# MDE-DR-4.net
KiCad netlist of a schematic drawn in EAGLE
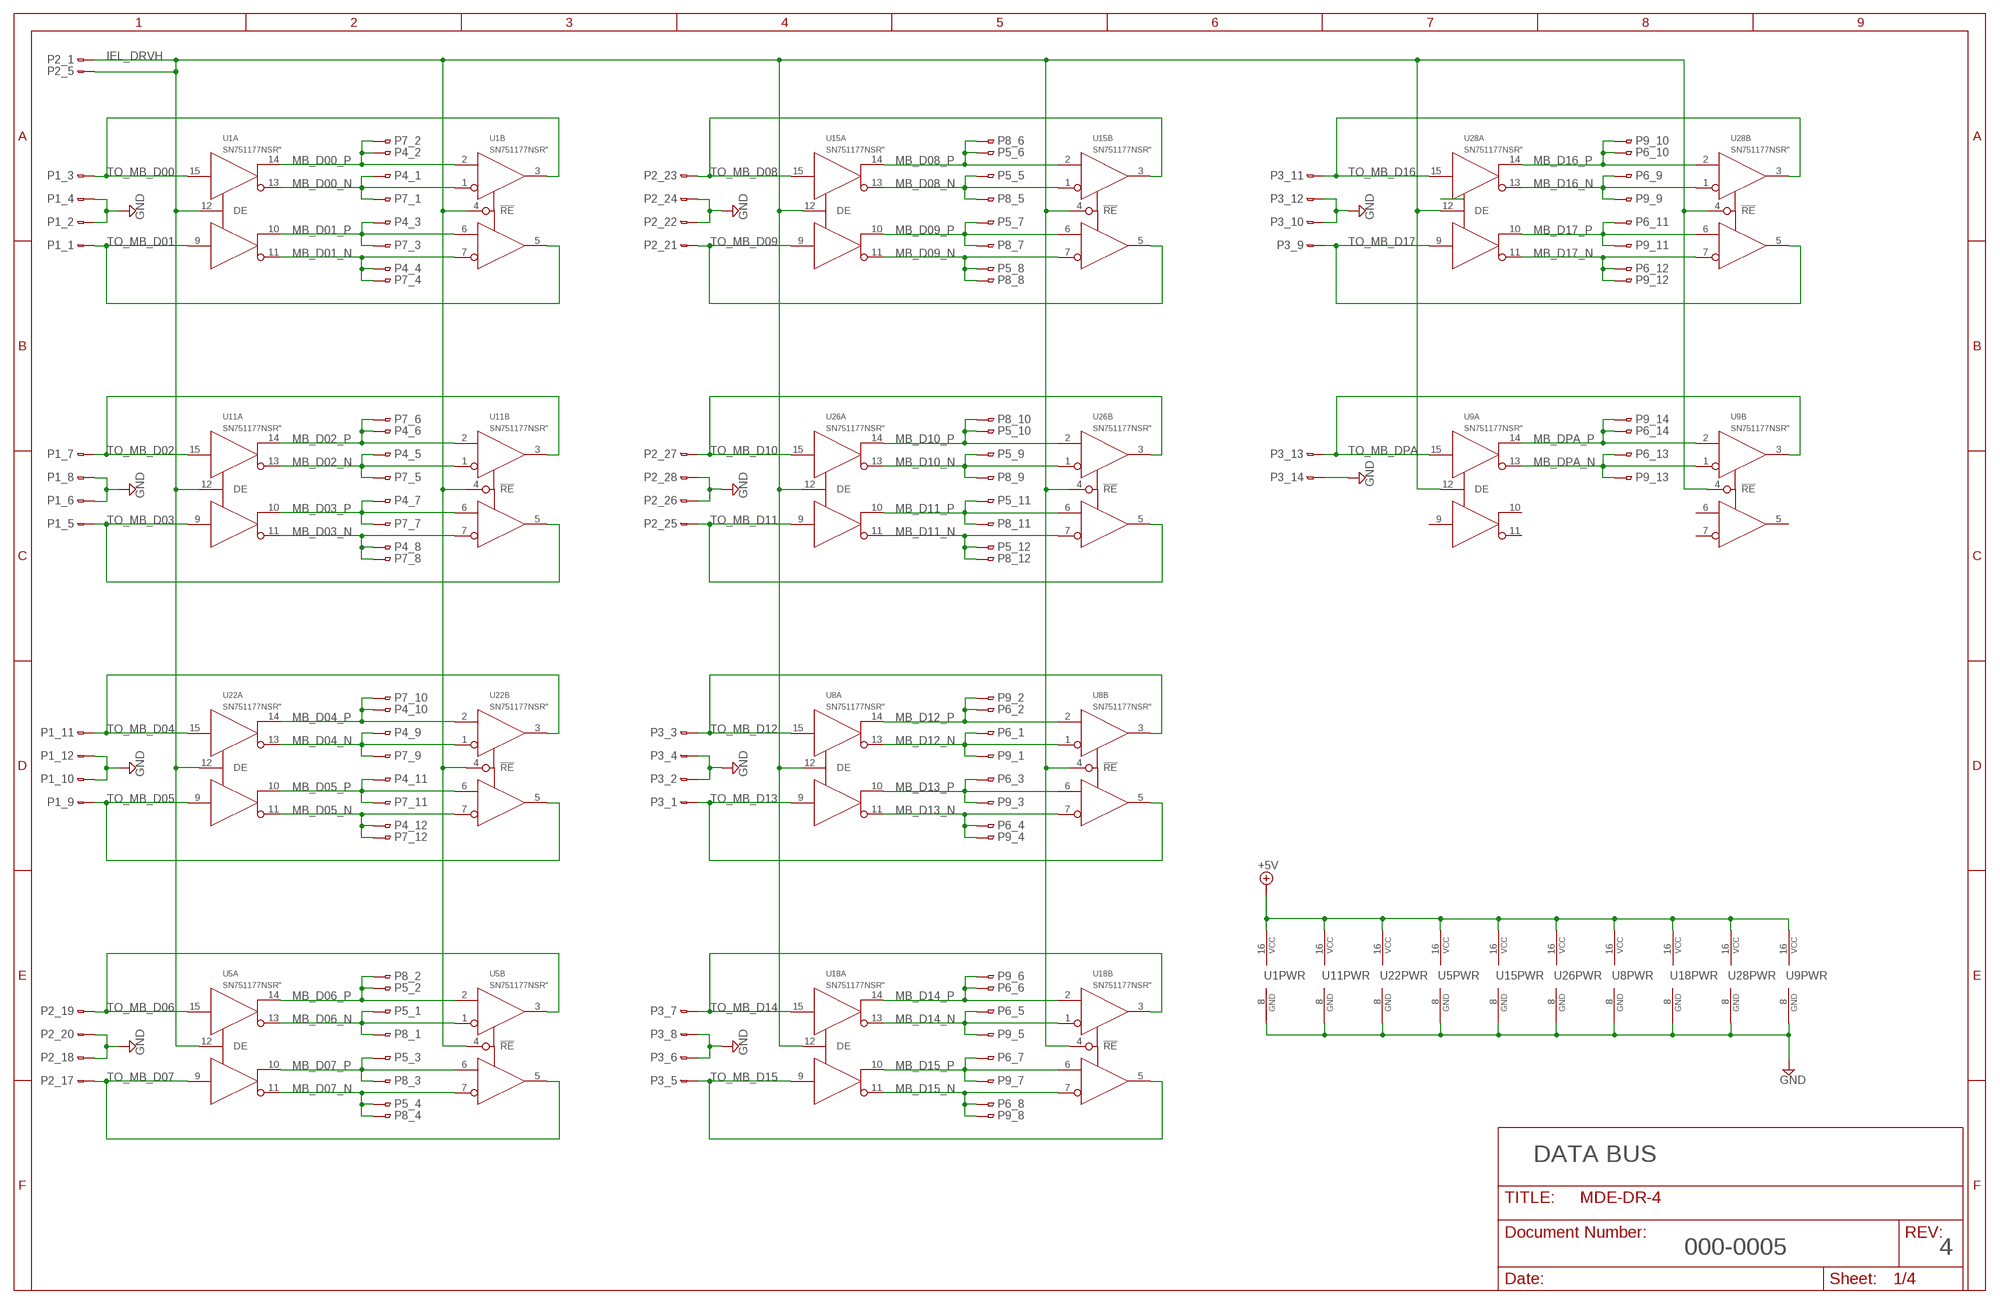
[diagram p0: schematic, sheet 1]
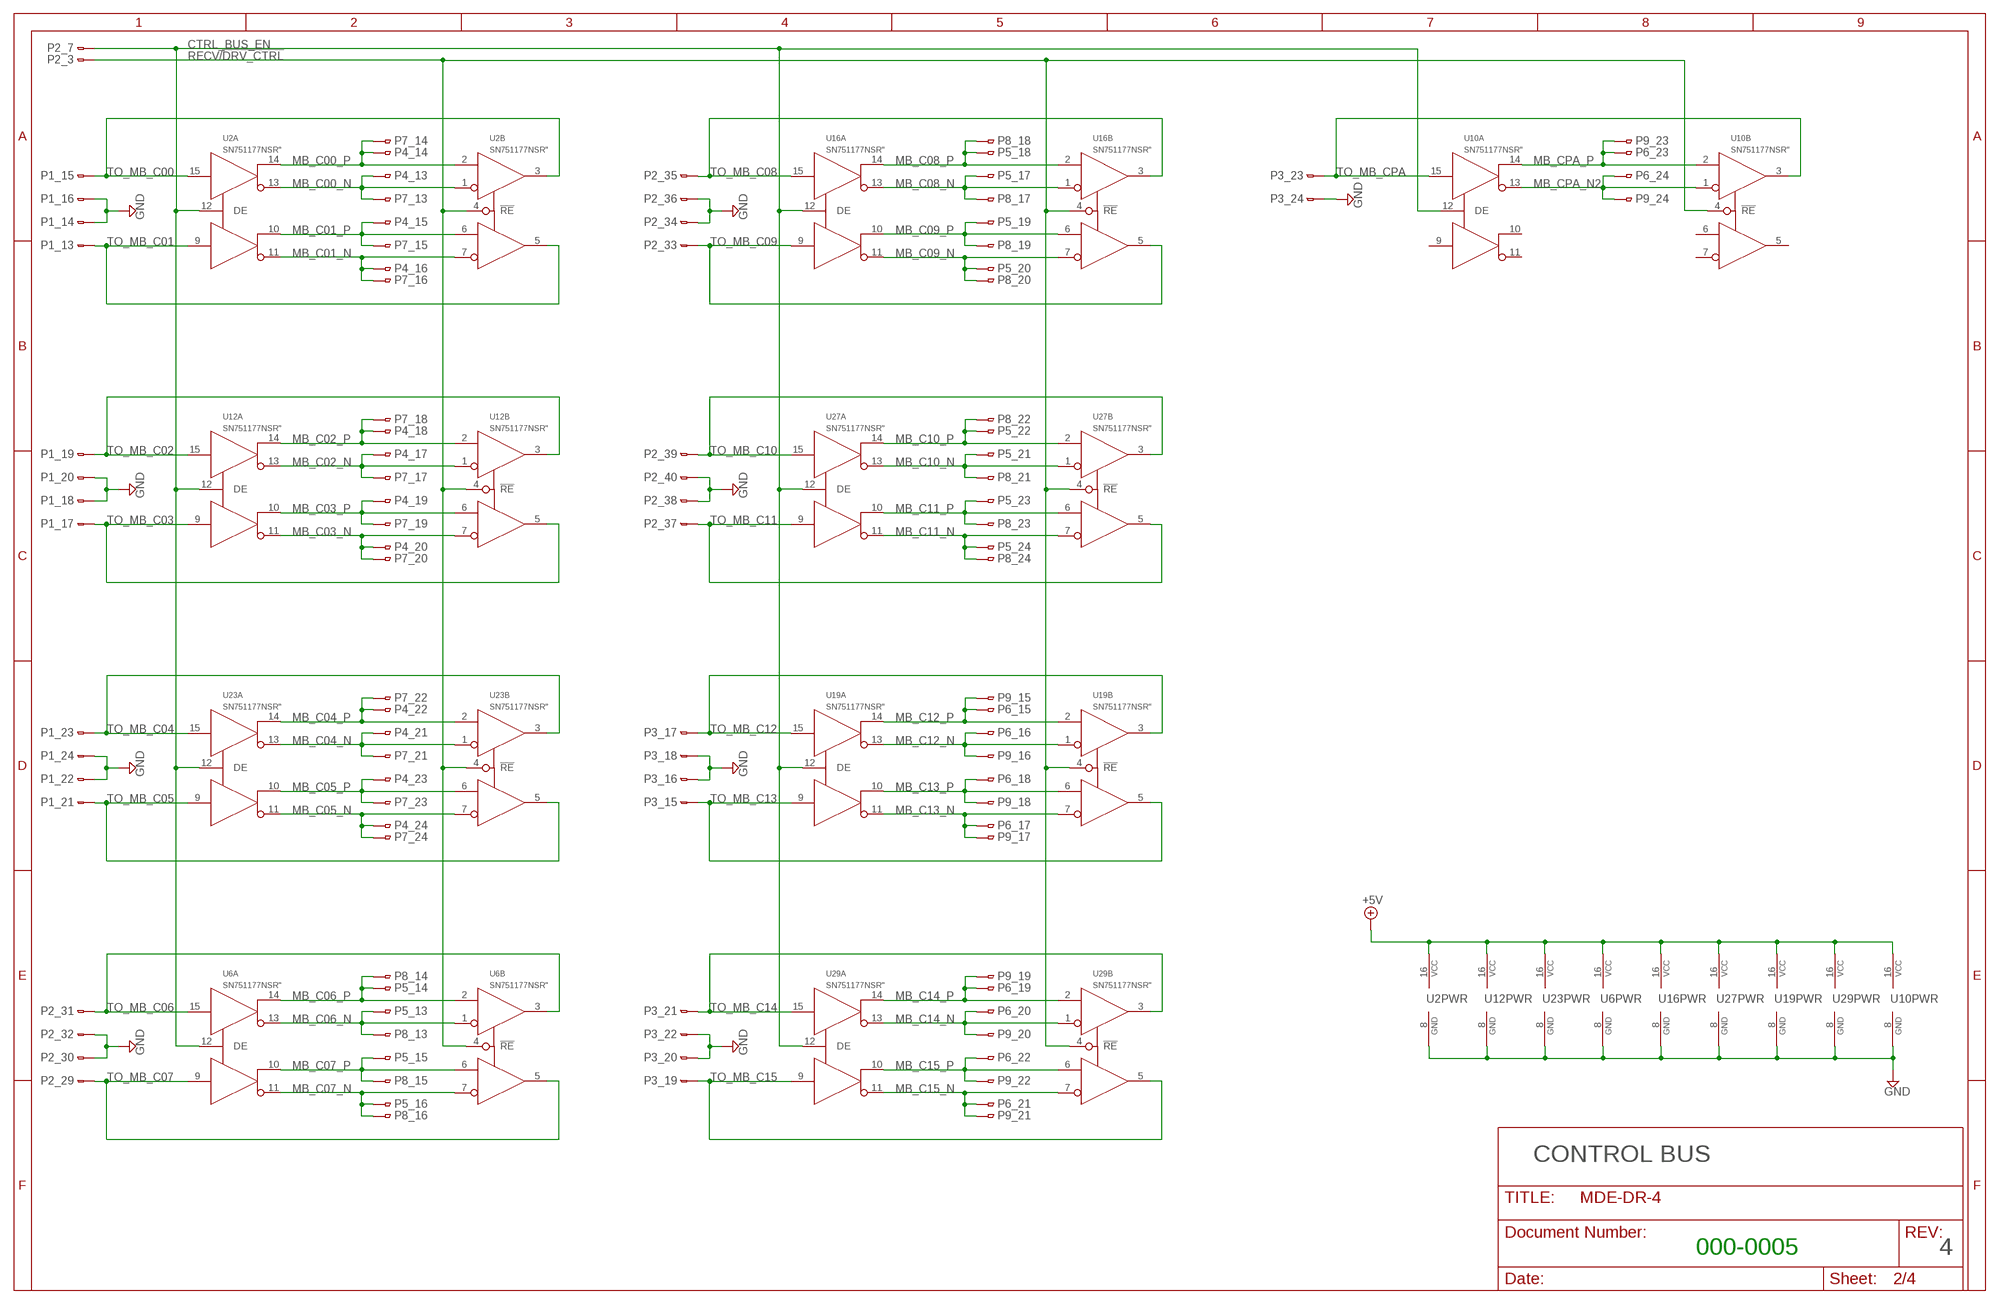
[diagram p1: schematic, sheet 2]
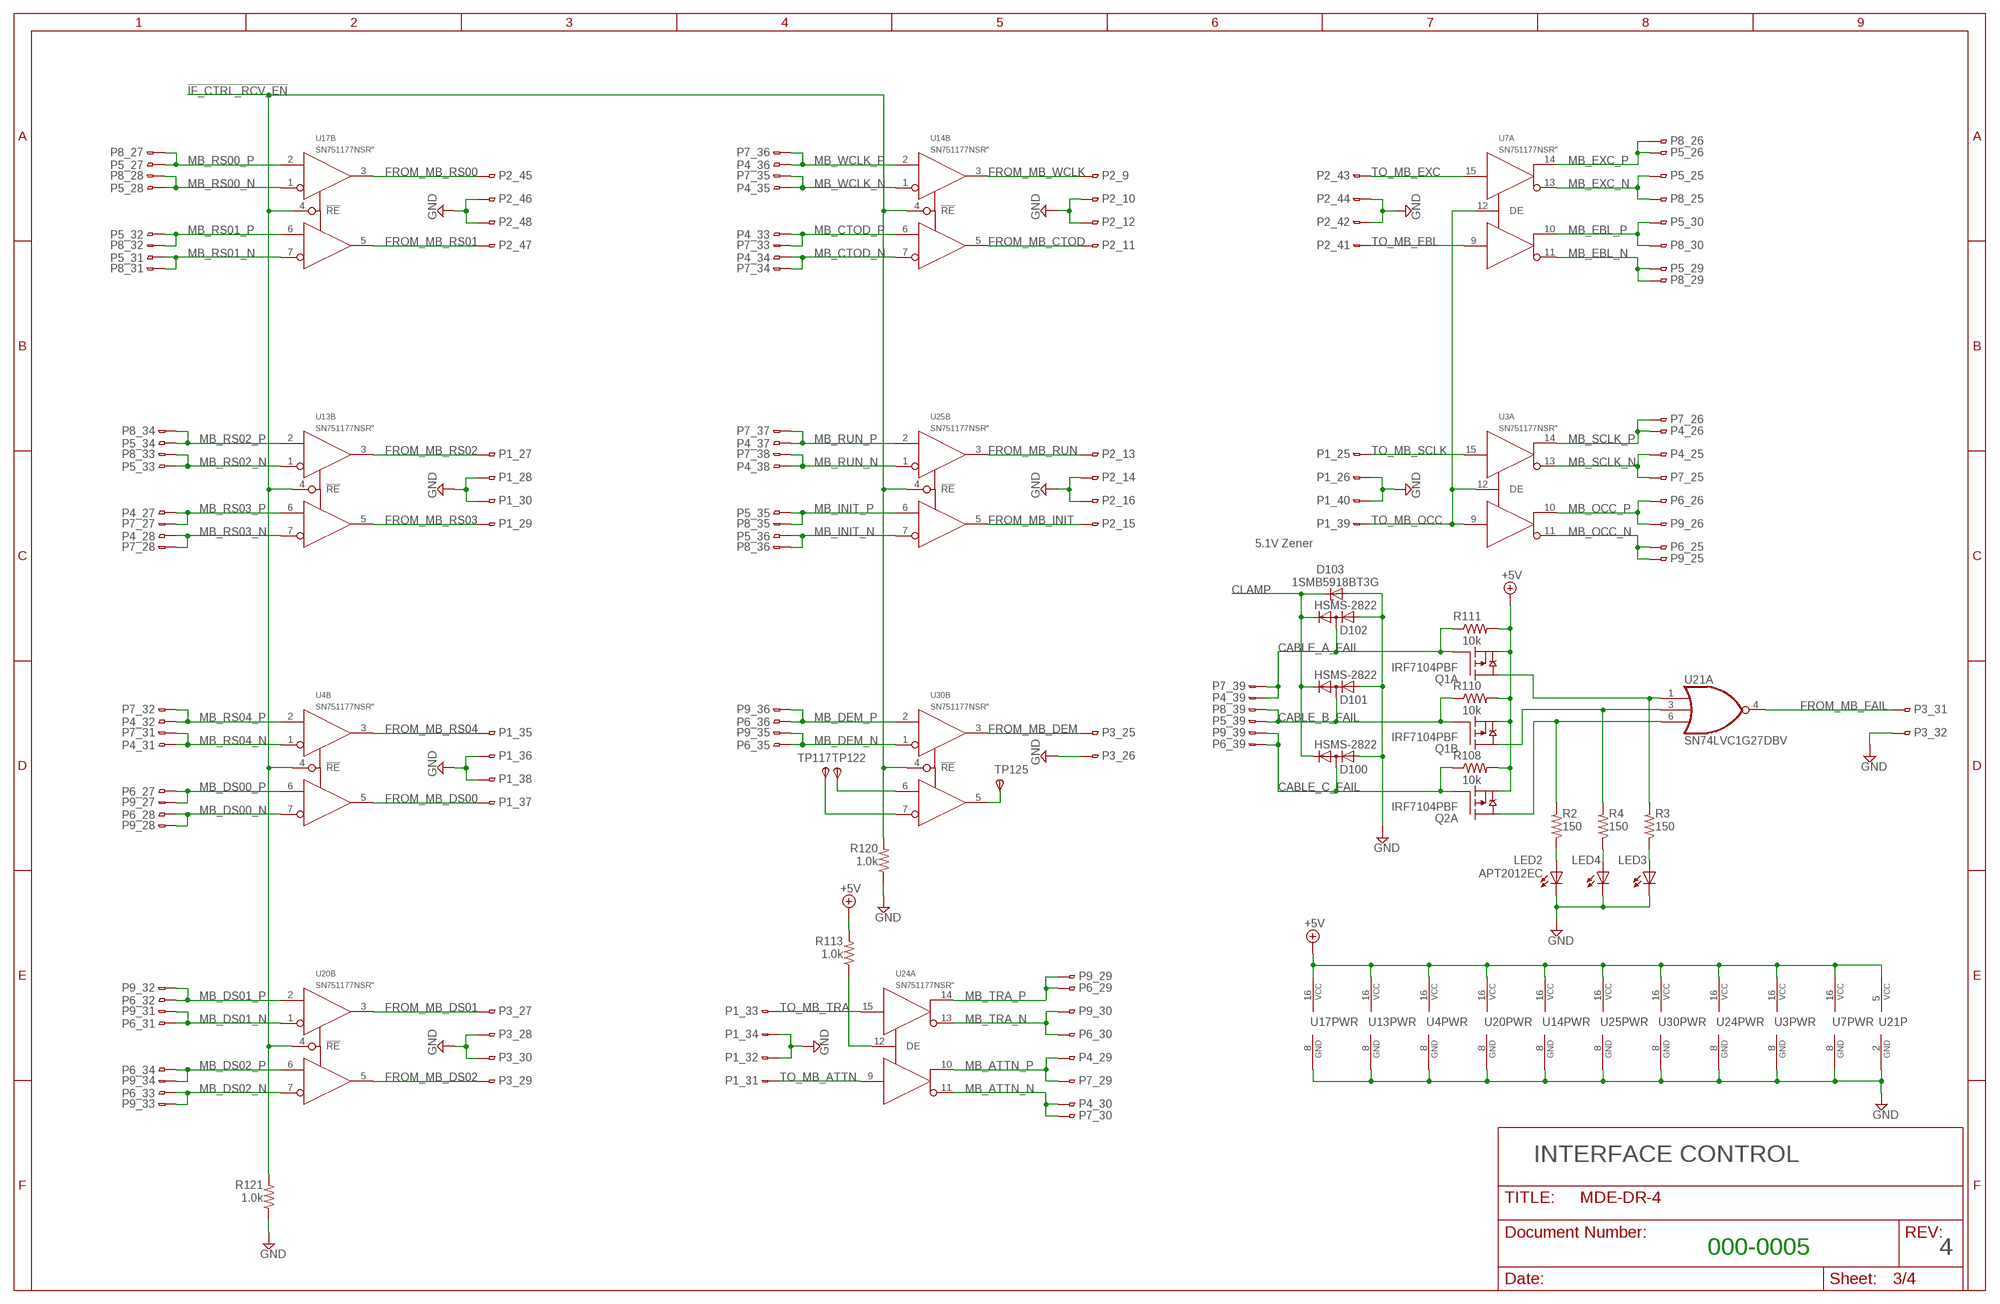
[diagram p2: schematic, sheet 3]
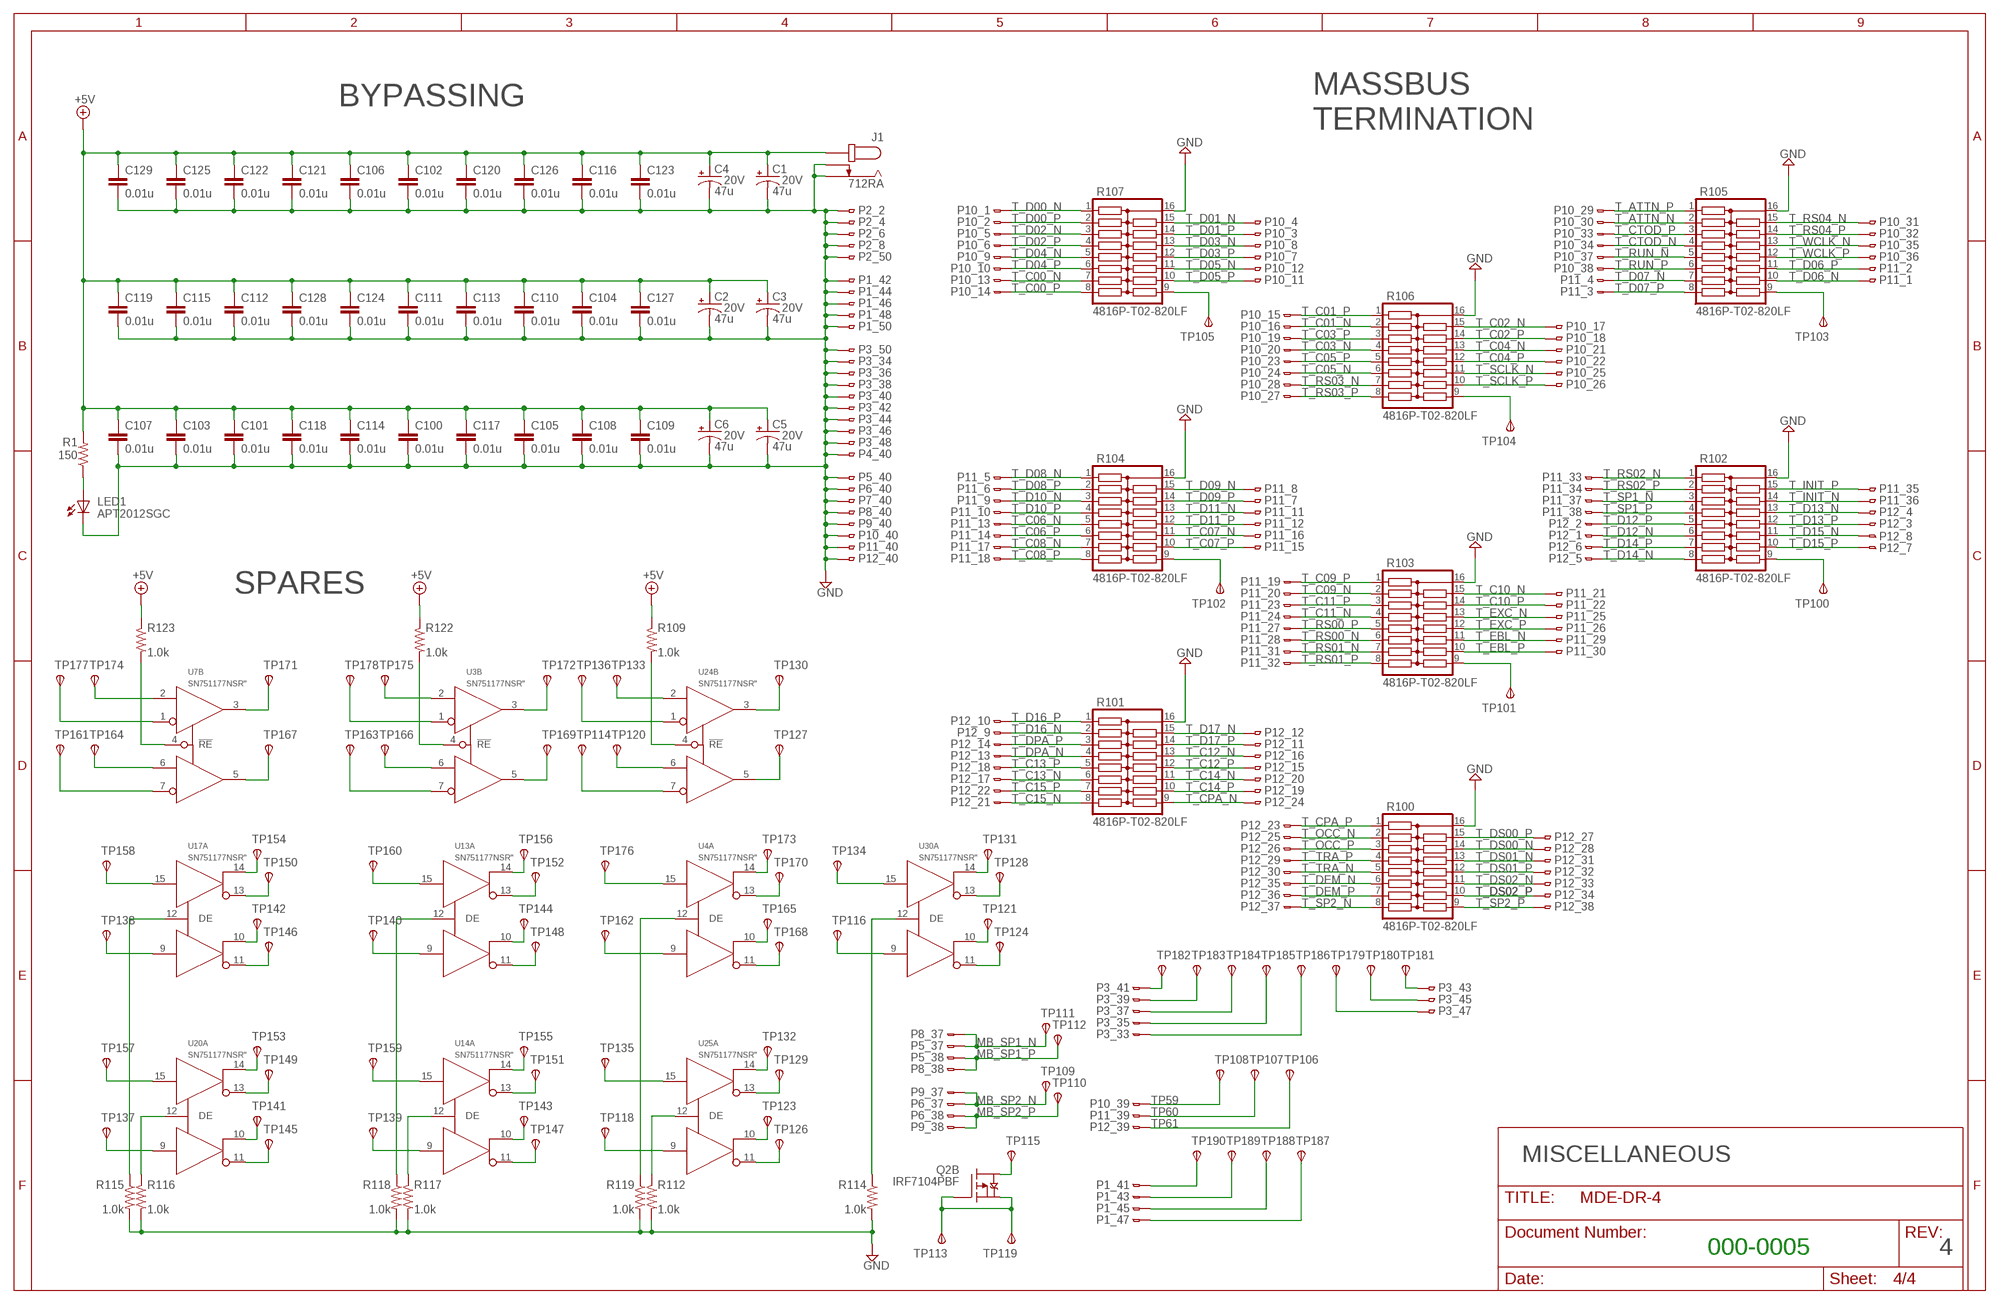
[diagram p3: schematic, sheet 4]

(export (version "E")
  (design (tool "Eeschema 10.0.6"))
  (components
    (comp (ref "D100")
      (value "HSMS-2822")
      (footprint "eagle-import:SOT23")
      (libsource (lib "eagle-import") (part "DIODE_2CACA-SOT23"))
    )
    (comp (ref "D101")
      (value "HSMS-2822")
      (footprint "eagle-import:SOT23")
      (libsource (lib "eagle-import") (part "DIODE_2CACA-SOT23"))
    )
    (comp (ref "D102")
      (value "HSMS-2822")
      (footprint "eagle-import:SOT23")
      (libsource (lib "eagle-import") (part "DIODE_2CACA-SOT23"))
    )
    (comp (ref "D103")
      (value "1SMB5918BT3G")
      (footprint "eagle-import:SMB")
      (libsource (lib "eagle-import") (part "ZENER-DIODESMB"))
    )
    (comp (ref "LED2")
      (value "APT2012EC")
      (footprint "eagle-import:SML0805")
      (libsource (lib "eagle-import") (part "LEDSML0805"))
    )
    (comp (ref "LED3")
      (value "APT2012EC")
      (footprint "eagle-import:SML0805")
      (libsource (lib "eagle-import") (part "LEDSML0805"))
    )
    (comp (ref "LED4")
      (value "APT2012EC")
      (footprint "eagle-import:SML0805")
      (libsource (lib "eagle-import") (part "LEDSML0805"))
    )
    (comp (ref "P1")
      (value "CON50L")
      (footprint "eagle-import:CON50L")
      (libsource (lib "eagle-import") (part "CON50L"))
    )
    (comp (ref "P2")
      (value "CON50L")
      (footprint "eagle-import:CON50L")
      (libsource (lib "eagle-import") (part "CON50L"))
    )
    (comp (ref "P3")
      (value "CON50L")
      (footprint "eagle-import:CON50L")
      (libsource (lib "eagle-import") (part "CON50L"))
    )
    (comp (ref "P4")
      (value "CON40L")
      (footprint "eagle-import:CON40L")
      (libsource (lib "eagle-import") (part "CON40L"))
    )
    (comp (ref "P5")
      (value "CON40L")
      (footprint "eagle-import:CON40L")
      (libsource (lib "eagle-import") (part "CON40L"))
    )
    (comp (ref "P6")
      (value "CON40L")
      (footprint "eagle-import:CON40L")
      (libsource (lib "eagle-import") (part "CON40L"))
    )
    (comp (ref "P7")
      (value "CON40L")
      (footprint "eagle-import:CON40L")
      (libsource (lib "eagle-import") (part "CON40L"))
    )
    (comp (ref "P8")
      (value "CON40L")
      (footprint "eagle-import:CON40L")
      (libsource (lib "eagle-import") (part "CON40L"))
    )
    (comp (ref "P9")
      (value "CON40L")
      (footprint "eagle-import:CON40L")
      (libsource (lib "eagle-import") (part "CON40L"))
    )
    (comp (ref "Q1")
      (value "IRF7104PBF")
      (footprint "eagle-import:SO-08")
      (libsource (lib "eagle-import") (part "IRF7104PBF"))
    )
    (comp (ref "Q2")
      (value "IRF7104PBF")
      (footprint "eagle-import:SO-08")
      (libsource (lib "eagle-import") (part "IRF7104PBF"))
    )
    (comp (ref "R2")
      (value "150")
      (footprint "eagle-import:R0805")
      (libsource (lib "eagle-import") (part "R-US_R0805"))
    )
    (comp (ref "R3")
      (value "150")
      (footprint "eagle-import:R0805")
      (libsource (lib "eagle-import") (part "R-US_R0805"))
    )
    (comp (ref "R4")
      (value "150")
      (footprint "eagle-import:R0805")
      (libsource (lib "eagle-import") (part "R-US_R0805"))
    )
    (comp (ref "R108")
      (value "10k")
      (footprint "eagle-import:R0805")
      (libsource (lib "eagle-import") (part "R-US_R0805"))
    )
    (comp (ref "R110")
      (value "10k")
      (footprint "eagle-import:R0805")
      (libsource (lib "eagle-import") (part "R-US_R0805"))
    )
    (comp (ref "R111")
      (value "10k")
      (footprint "eagle-import:R0805")
      (libsource (lib "eagle-import") (part "R-US_R0805"))
    )
    (comp (ref "R113")
      (value "1.0k")
      (footprint "eagle-import:R0805")
      (libsource (lib "eagle-import") (part "R-US_R0805"))
    )
    (comp (ref "R120")
      (value "1.0k")
      (footprint "eagle-import:R0805")
      (libsource (lib "eagle-import") (part "R-US_R0805"))
    )
    (comp (ref "R121")
      (value "1.0k")
      (footprint "eagle-import:R0805")
      (libsource (lib "eagle-import") (part "R-US_R0805"))
    )
    (comp (ref "TP117")
      (value "TPSTP12R")
      (footprint "eagle-import:TP12R")
      (libsource (lib "eagle-import") (part "TPSTP12R"))
    )
    (comp (ref "TP122")
      (value "TPSTP12R")
      (footprint "eagle-import:TP12R")
      (libsource (lib "eagle-import") (part "TPSTP12R"))
    )
    (comp (ref "TP125")
      (value "TPSTP12R")
      (footprint "eagle-import:TP12R")
      (libsource (lib "eagle-import") (part "TPSTP12R"))
    )
    (comp (ref "U3")
      (value "SN751177NSR\"")
      (footprint "eagle-import:SO16NS")
      (libsource (lib "eagle-import") (part "SN751177NSR{dblquote}"))
    )
    (comp (ref "U4")
      (value "SN751177NSR\"")
      (footprint "eagle-import:SO16NS")
      (libsource (lib "eagle-import") (part "SN751177NSR{dblquote}"))
    )
    (comp (ref "U7")
      (value "SN751177NSR\"")
      (footprint "eagle-import:SO16NS")
      (libsource (lib "eagle-import") (part "SN751177NSR{dblquote}"))
    )
    (comp (ref "U13")
      (value "SN751177NSR\"")
      (footprint "eagle-import:SO16NS")
      (libsource (lib "eagle-import") (part "SN751177NSR{dblquote}"))
    )
    (comp (ref "U14")
      (value "SN751177NSR\"")
      (footprint "eagle-import:SO16NS")
      (libsource (lib "eagle-import") (part "SN751177NSR{dblquote}"))
    )
    (comp (ref "U17")
      (value "SN751177NSR\"")
      (footprint "eagle-import:SO16NS")
      (libsource (lib "eagle-import") (part "SN751177NSR{dblquote}"))
    )
    (comp (ref "U20")
      (value "SN751177NSR\"")
      (footprint "eagle-import:SO16NS")
      (libsource (lib "eagle-import") (part "SN751177NSR{dblquote}"))
    )
    (comp (ref "U21")
      (value "SN74LVC1G27DBV")
      (footprint "eagle-import:DBV_R-PDSO-G6")
      (libsource (lib "eagle-import") (part "SN74LVC1G27DBV"))
    )
    (comp (ref "U24")
      (value "SN751177NSR\"")
      (footprint "eagle-import:SO16NS")
      (libsource (lib "eagle-import") (part "SN751177NSR{dblquote}"))
    )
    (comp (ref "U25")
      (value "SN751177NSR\"")
      (footprint "eagle-import:SO16NS")
      (libsource (lib "eagle-import") (part "SN751177NSR{dblquote}"))
    )
    (comp (ref "U30")
      (value "SN751177NSR\"")
      (footprint "eagle-import:SO16NS")
      (libsource (lib "eagle-import") (part "SN751177NSR{dblquote}"))
    )
    (comp (ref "C1")
      (value "47u")
      (footprint "eagle-import:C_6032-28R")
      (fields (field (name "VOLTAGE") "20V"))
      (libsource (lib "eagle-import") (part "CPOL-USC/6032-28R"))
    )
    (comp (ref "C2")
      (value "47u")
      (footprint "eagle-import:C_6032-28R")
      (fields (field (name "VOLTAGE") "20V"))
      (libsource (lib "eagle-import") (part "CPOL-USC/6032-28R"))
    )
    (comp (ref "C3")
      (value "47u")
      (footprint "eagle-import:C_6032-28R")
      (fields (field (name "VOLTAGE") "20V"))
      (libsource (lib "eagle-import") (part "CPOL-USC/6032-28R"))
    )
    (comp (ref "C4")
      (value "47u")
      (footprint "eagle-import:C_6032-28R")
      (fields (field (name "VOLTAGE") "20V"))
      (libsource (lib "eagle-import") (part "CPOL-USC/6032-28R"))
    )
    (comp (ref "C5")
      (value "47u")
      (footprint "eagle-import:C_6032-28R")
      (fields (field (name "VOLTAGE") "20V"))
      (libsource (lib "eagle-import") (part "CPOL-USC/6032-28R"))
    )
    (comp (ref "C6")
      (value "47u")
      (footprint "eagle-import:C_6032-28R")
      (fields (field (name "VOLTAGE") "20V"))
      (libsource (lib "eagle-import") (part "CPOL-USC/6032-28R"))
    )
    (comp (ref "C100")
      (value "0.01u")
      (footprint "eagle-import:C0805K")
      (libsource (lib "eagle-import") (part "C-EUC0805K"))
    )
    (comp (ref "C101")
      (value "0.01u")
      (footprint "eagle-import:C0805K")
      (libsource (lib "eagle-import") (part "C-EUC0805K"))
    )
    (comp (ref "C102")
      (value "0.01u")
      (footprint "eagle-import:C0805K")
      (libsource (lib "eagle-import") (part "C-EUC0805K"))
    )
    (comp (ref "C103")
      (value "0.01u")
      (footprint "eagle-import:C0805K")
      (libsource (lib "eagle-import") (part "C-EUC0805K"))
    )
    (comp (ref "C104")
      (value "0.01u")
      (footprint "eagle-import:C0805K")
      (libsource (lib "eagle-import") (part "C-EUC0805K"))
    )
    (comp (ref "C105")
      (value "0.01u")
      (footprint "eagle-import:C0805K")
      (libsource (lib "eagle-import") (part "C-EUC0805K"))
    )
    (comp (ref "C106")
      (value "0.01u")
      (footprint "eagle-import:C0805K")
      (libsource (lib "eagle-import") (part "C-EUC0805K"))
    )
    (comp (ref "C107")
      (value "0.01u")
      (footprint "eagle-import:C0805K")
      (libsource (lib "eagle-import") (part "C-EUC0805K"))
    )
    (comp (ref "C108")
      (value "0.01u")
      (footprint "eagle-import:C0805K")
      (libsource (lib "eagle-import") (part "C-EUC0805K"))
    )
    (comp (ref "C109")
      (value "0.01u")
      (footprint "eagle-import:C0805K")
      (libsource (lib "eagle-import") (part "C-EUC0805K"))
    )
    (comp (ref "C110")
      (value "0.01u")
      (footprint "eagle-import:C0805K")
      (libsource (lib "eagle-import") (part "C-EUC0805K"))
    )
    (comp (ref "C111")
      (value "0.01u")
      (footprint "eagle-import:C0805K")
      (libsource (lib "eagle-import") (part "C-EUC0805K"))
    )
    (comp (ref "C112")
      (value "0.01u")
      (footprint "eagle-import:C0805K")
      (libsource (lib "eagle-import") (part "C-EUC0805K"))
    )
    (comp (ref "C113")
      (value "0.01u")
      (footprint "eagle-import:C0805K")
      (libsource (lib "eagle-import") (part "C-EUC0805K"))
    )
    (comp (ref "C114")
      (value "0.01u")
      (footprint "eagle-import:C0805K")
      (libsource (lib "eagle-import") (part "C-EUC0805K"))
    )
    (comp (ref "C115")
      (value "0.01u")
      (footprint "eagle-import:C0805K")
      (libsource (lib "eagle-import") (part "C-EUC0805K"))
    )
    (comp (ref "C116")
      (value "0.01u")
      (footprint "eagle-import:C0805K")
      (libsource (lib "eagle-import") (part "C-EUC0805K"))
    )
    (comp (ref "C117")
      (value "0.01u")
      (footprint "eagle-import:C0805K")
      (libsource (lib "eagle-import") (part "C-EUC0805K"))
    )
    (comp (ref "C118")
      (value "0.01u")
      (footprint "eagle-import:C0805K")
      (libsource (lib "eagle-import") (part "C-EUC0805K"))
    )
    (comp (ref "C119")
      (value "0.01u")
      (footprint "eagle-import:C0805K")
      (libsource (lib "eagle-import") (part "C-EUC0805K"))
    )
    (comp (ref "C120")
      (value "0.01u")
      (footprint "eagle-import:C0805K")
      (libsource (lib "eagle-import") (part "C-EUC0805K"))
    )
    (comp (ref "C121")
      (value "0.01u")
      (footprint "eagle-import:C0805K")
      (libsource (lib "eagle-import") (part "C-EUC0805K"))
    )
    (comp (ref "C122")
      (value "0.01u")
      (footprint "eagle-import:C0805K")
      (libsource (lib "eagle-import") (part "C-EUC0805K"))
    )
    (comp (ref "C123")
      (value "0.01u")
      (footprint "eagle-import:C0805K")
      (libsource (lib "eagle-import") (part "C-EUC0805K"))
    )
    (comp (ref "C124")
      (value "0.01u")
      (footprint "eagle-import:C0805K")
      (libsource (lib "eagle-import") (part "C-EUC0805K"))
    )
    (comp (ref "C125")
      (value "0.01u")
      (footprint "eagle-import:C0805K")
      (libsource (lib "eagle-import") (part "C-EUC0805K"))
    )
    (comp (ref "C126")
      (value "0.01u")
      (footprint "eagle-import:C0805K")
      (libsource (lib "eagle-import") (part "C-EUC0805K"))
    )
    (comp (ref "C127")
      (value "0.01u")
      (footprint "eagle-import:C0805K")
      (libsource (lib "eagle-import") (part "C-EUC0805K"))
    )
    (comp (ref "C128")
      (value "0.01u")
      (footprint "eagle-import:C0805K")
      (libsource (lib "eagle-import") (part "C-EUC0805K"))
    )
    (comp (ref "C129")
      (value "0.01u")
      (footprint "eagle-import:C0805K")
      (libsource (lib "eagle-import") (part "C-EUC0805K"))
    )
    (comp (ref "J1")
      (value "712RA")
      (footprint "eagle-import:712RA")
      (libsource (lib "eagle-import") (part "JACK-PLUG1"))
    )
    (comp (ref "LED1")
      (value "APT2012SGC")
      (footprint "eagle-import:SML0805")
      (libsource (lib "eagle-import") (part "LEDSML0805"))
    )
    (comp (ref "P10")
      (value "CON40L")
      (footprint "eagle-import:CON40L")
      (libsource (lib "eagle-import") (part "CON40L"))
    )
    (comp (ref "P11")
      (value "CON40L")
      (footprint "eagle-import:CON40L")
      (libsource (lib "eagle-import") (part "CON40L"))
    )
    (comp (ref "P12")
      (value "CON40L")
      (footprint "eagle-import:CON40L")
      (libsource (lib "eagle-import") (part "CON40L"))
    )
    (comp (ref "R1")
      (value "150")
      (footprint "eagle-import:R0805")
      (libsource (lib "eagle-import") (part "R-US_R0805"))
    )
    (comp (ref "R100")
      (value "4816P-T02-820LF")
      (footprint "eagle-import:4816P")
      (fields (field (name "MF") "BOURNS, INC.") (field (name "MPN") "4816P-T02-824LF"))
      (libsource (lib "eagle-import") (part "4816P-T02"))
    )
    (comp (ref "R101")
      (value "4816P-T02-820LF")
      (footprint "eagle-import:4816P")
      (fields (field (name "MF") "BOURNS, INC.") (field (name "MPN") "4816P-T02-824LF"))
      (libsource (lib "eagle-import") (part "4816P-T02"))
    )
    (comp (ref "R102")
      (value "4816P-T02-820LF")
      (footprint "eagle-import:4816P")
      (fields (field (name "MF") "BOURNS, INC.") (field (name "MPN") "4816P-T02-824LF"))
      (libsource (lib "eagle-import") (part "4816P-T02"))
    )
    (comp (ref "R103")
      (value "4816P-T02-820LF")
      (footprint "eagle-import:4816P")
      (fields (field (name "MF") "BOURNS, INC.") (field (name "MPN") "4816P-T02-824LF"))
      (libsource (lib "eagle-import") (part "4816P-T02"))
    )
    (comp (ref "R104")
      (value "4816P-T02-820LF")
      (footprint "eagle-import:4816P")
      (fields (field (name "MF") "BOURNS, INC.") (field (name "MPN") "4816P-T02-824LF"))
      (libsource (lib "eagle-import") (part "4816P-T02"))
    )
    (comp (ref "R105")
      (value "4816P-T02-820LF")
      (footprint "eagle-import:4816P")
      (fields (field (name "MF") "BOURNS, INC.") (field (name "MPN") "4816P-T02-824LF"))
      (libsource (lib "eagle-import") (part "4816P-T02"))
    )
    (comp (ref "R106")
      (value "4816P-T02-820LF")
      (footprint "eagle-import:4816P")
      (fields (field (name "MF") "BOURNS, INC.") (field (name "MPN") "4816P-T02-824LF"))
      (libsource (lib "eagle-import") (part "4816P-T02"))
    )
    (comp (ref "R107")
      (value "4816P-T02-820LF")
      (footprint "eagle-import:4816P")
      (fields (field (name "MF") "BOURNS, INC.") (field (name "MPN") "4816P-T02-824LF"))
      (libsource (lib "eagle-import") (part "4816P-T02"))
    )
    (comp (ref "R109")
      (value "1.0k")
      (footprint "eagle-import:R0805")
      (libsource (lib "eagle-import") (part "R-US_R0805"))
    )
    (comp (ref "R112")
      (value "1.0k")
      (footprint "eagle-import:R0805")
      (libsource (lib "eagle-import") (part "R-US_R0805"))
    )
    (comp (ref "R114")
      (value "1.0k")
      (footprint "eagle-import:R0805")
      (libsource (lib "eagle-import") (part "R-US_R0805"))
    )
    (comp (ref "R115")
      (value "1.0k")
      (footprint "eagle-import:R0805")
      (libsource (lib "eagle-import") (part "R-US_R0805"))
    )
    (comp (ref "R116")
      (value "1.0k")
      (footprint "eagle-import:R0805")
      (libsource (lib "eagle-import") (part "R-US_R0805"))
    )
    (comp (ref "R117")
      (value "1.0k")
      (footprint "eagle-import:R0805")
      (libsource (lib "eagle-import") (part "R-US_R0805"))
    )
    (comp (ref "R118")
      (value "1.0k")
      (footprint "eagle-import:R0805")
      (libsource (lib "eagle-import") (part "R-US_R0805"))
    )
    (comp (ref "R119")
      (value "1.0k")
      (footprint "eagle-import:R0805")
      (libsource (lib "eagle-import") (part "R-US_R0805"))
    )
    (comp (ref "R122")
      (value "1.0k")
      (footprint "eagle-import:R0805")
      (libsource (lib "eagle-import") (part "R-US_R0805"))
    )
    (comp (ref "R123")
      (value "1.0k")
      (footprint "eagle-import:R0805")
      (libsource (lib "eagle-import") (part "R-US_R0805"))
    )
    (comp (ref "TP100")
      (value "TPSTP12R")
      (footprint "eagle-import:TP12R")
      (libsource (lib "eagle-import") (part "TPSTP12R"))
    )
    (comp (ref "TP101")
      (value "TPSTP12R")
      (footprint "eagle-import:TP12R")
      (libsource (lib "eagle-import") (part "TPSTP12R"))
    )
    (comp (ref "TP102")
      (value "TPSTP12R")
      (footprint "eagle-import:TP12R")
      (libsource (lib "eagle-import") (part "TPSTP12R"))
    )
    (comp (ref "TP103")
      (value "TPSTP12R")
      (footprint "eagle-import:TP12R")
      (libsource (lib "eagle-import") (part "TPSTP12R"))
    )
    (comp (ref "TP104")
      (value "TPSTP12R")
      (footprint "eagle-import:TP12R")
      (libsource (lib "eagle-import") (part "TPSTP12R"))
    )
    (comp (ref "TP105")
      (value "TPSTP12R")
      (footprint "eagle-import:TP12R")
      (libsource (lib "eagle-import") (part "TPSTP12R"))
    )
    (comp (ref "TP106")
      (value "TPSTP12R")
      (footprint "eagle-import:TP12R")
      (libsource (lib "eagle-import") (part "TPSTP12R"))
    )
    (comp (ref "TP107")
      (value "TPSTP12R")
      (footprint "eagle-import:TP12R")
      (libsource (lib "eagle-import") (part "TPSTP12R"))
    )
    (comp (ref "TP108")
      (value "TPSTP12R")
      (footprint "eagle-import:TP12R")
      (libsource (lib "eagle-import") (part "TPSTP12R"))
    )
    (comp (ref "TP109")
      (value "TPSTP12R")
      (footprint "eagle-import:TP12R")
      (libsource (lib "eagle-import") (part "TPSTP12R"))
    )
    (comp (ref "TP110")
      (value "TPSTP12R")
      (footprint "eagle-import:TP12R")
      (libsource (lib "eagle-import") (part "TPSTP12R"))
    )
    (comp (ref "TP111")
      (value "TPSTP12R")
      (footprint "eagle-import:TP12R")
      (libsource (lib "eagle-import") (part "TPSTP12R"))
    )
    (comp (ref "TP112")
      (value "TPSTP12R")
      (footprint "eagle-import:TP12R")
      (libsource (lib "eagle-import") (part "TPSTP12R"))
    )
    (comp (ref "TP113")
      (value "TPSTP12R")
      (footprint "eagle-import:TP12R")
      (libsource (lib "eagle-import") (part "TPSTP12R"))
    )
    (comp (ref "TP114")
      (value "TPSTP12R")
      (footprint "eagle-import:TP12R")
      (libsource (lib "eagle-import") (part "TPSTP12R"))
    )
    (comp (ref "TP115")
      (value "TPSTP12R")
      (footprint "eagle-import:TP12R")
      (libsource (lib "eagle-import") (part "TPSTP12R"))
    )
    (comp (ref "TP116")
      (value "TPSTP12R")
      (footprint "eagle-import:TP12R")
      (libsource (lib "eagle-import") (part "TPSTP12R"))
    )
    (comp (ref "TP118")
      (value "TPSTP12R")
      (footprint "eagle-import:TP12R")
      (libsource (lib "eagle-import") (part "TPSTP12R"))
    )
    (comp (ref "TP119")
      (value "TPSTP12R")
      (footprint "eagle-import:TP12R")
      (libsource (lib "eagle-import") (part "TPSTP12R"))
    )
    (comp (ref "TP120")
      (value "TPSTP12R")
      (footprint "eagle-import:TP12R")
      (libsource (lib "eagle-import") (part "TPSTP12R"))
    )
    (comp (ref "TP121")
      (value "TPSTP12R")
      (footprint "eagle-import:TP12R")
      (libsource (lib "eagle-import") (part "TPSTP12R"))
    )
    (comp (ref "TP123")
      (value "TPSTP12R")
      (footprint "eagle-import:TP12R")
      (libsource (lib "eagle-import") (part "TPSTP12R"))
    )
    (comp (ref "TP124")
      (value "TPSTP12R")
      (footprint "eagle-import:TP12R")
      (libsource (lib "eagle-import") (part "TPSTP12R"))
    )
    (comp (ref "TP126")
      (value "TPSTP12R")
      (footprint "eagle-import:TP12R")
      (libsource (lib "eagle-import") (part "TPSTP12R"))
    )
    (comp (ref "TP127")
      (value "TPSTP12R")
      (footprint "eagle-import:TP12R")
      (libsource (lib "eagle-import") (part "TPSTP12R"))
    )
    (comp (ref "TP128")
      (value "TPSTP12R")
      (footprint "eagle-import:TP12R")
      (libsource (lib "eagle-import") (part "TPSTP12R"))
    )
    (comp (ref "TP129")
      (value "TPSTP12R")
      (footprint "eagle-import:TP12R")
      (libsource (lib "eagle-import") (part "TPSTP12R"))
    )
    (comp (ref "TP130")
      (value "TPSTP12R")
      (footprint "eagle-import:TP12R")
      (libsource (lib "eagle-import") (part "TPSTP12R"))
    )
    (comp (ref "TP131")
      (value "TPSTP12R")
      (footprint "eagle-import:TP12R")
      (libsource (lib "eagle-import") (part "TPSTP12R"))
    )
    (comp (ref "TP132")
      (value "TPSTP12R")
      (footprint "eagle-import:TP12R")
      (libsource (lib "eagle-import") (part "TPSTP12R"))
    )
    (comp (ref "TP133")
      (value "TPSTP12R")
      (footprint "eagle-import:TP12R")
      (libsource (lib "eagle-import") (part "TPSTP12R"))
    )
    (comp (ref "TP134")
      (value "TPSTP12R")
      (footprint "eagle-import:TP12R")
      (libsource (lib "eagle-import") (part "TPSTP12R"))
    )
    (comp (ref "TP135")
      (value "TPSTP12R")
      (footprint "eagle-import:TP12R")
      (libsource (lib "eagle-import") (part "TPSTP12R"))
    )
    (comp (ref "TP136")
      (value "TPSTP12R")
      (footprint "eagle-import:TP12R")
      (libsource (lib "eagle-import") (part "TPSTP12R"))
    )
    (comp (ref "TP137")
      (value "TPSTP12R")
      (footprint "eagle-import:TP12R")
      (libsource (lib "eagle-import") (part "TPSTP12R"))
    )
    (comp (ref "TP138")
      (value "TPSTP12R")
      (footprint "eagle-import:TP12R")
      (libsource (lib "eagle-import") (part "TPSTP12R"))
    )
    (comp (ref "TP139")
      (value "TPSTP12R")
      (footprint "eagle-import:TP12R")
      (libsource (lib "eagle-import") (part "TPSTP12R"))
    )
    (comp (ref "TP140")
      (value "TPSTP12R")
      (footprint "eagle-import:TP12R")
      (libsource (lib "eagle-import") (part "TPSTP12R"))
    )
    (comp (ref "TP141")
      (value "TPSTP12R")
      (footprint "eagle-import:TP12R")
      (libsource (lib "eagle-import") (part "TPSTP12R"))
    )
    (comp (ref "TP142")
      (value "TPSTP12R")
      (footprint "eagle-import:TP12R")
      (libsource (lib "eagle-import") (part "TPSTP12R"))
    )
    (comp (ref "TP143")
      (value "TPSTP12R")
      (footprint "eagle-import:TP12R")
      (libsource (lib "eagle-import") (part "TPSTP12R"))
    )
    (comp (ref "TP144")
      (value "TPSTP12R")
      (footprint "eagle-import:TP12R")
      (libsource (lib "eagle-import") (part "TPSTP12R"))
    )
    (comp (ref "TP145")
      (value "TPSTP12R")
      (footprint "eagle-import:TP12R")
      (libsource (lib "eagle-import") (part "TPSTP12R"))
    )
    (comp (ref "TP146")
      (value "TPSTP12R")
      (footprint "eagle-import:TP12R")
      (libsource (lib "eagle-import") (part "TPSTP12R"))
    )
    (comp (ref "TP147")
      (value "TPSTP12R")
      (footprint "eagle-import:TP12R")
      (libsource (lib "eagle-import") (part "TPSTP12R"))
    )
    (comp (ref "TP148")
      (value "TPSTP12R")
      (footprint "eagle-import:TP12R")
      (libsource (lib "eagle-import") (part "TPSTP12R"))
    )
    (comp (ref "TP149")
      (value "TPSTP12R")
      (footprint "eagle-import:TP12R")
      (libsource (lib "eagle-import") (part "TPSTP12R"))
    )
    (comp (ref "TP150")
      (value "TPSTP12R")
      (footprint "eagle-import:TP12R")
      (libsource (lib "eagle-import") (part "TPSTP12R"))
    )
    (comp (ref "TP151")
      (value "TPSTP12R")
      (footprint "eagle-import:TP12R")
      (libsource (lib "eagle-import") (part "TPSTP12R"))
    )
    (comp (ref "TP152")
      (value "TPSTP12R")
      (footprint "eagle-import:TP12R")
      (libsource (lib "eagle-import") (part "TPSTP12R"))
    )
    (comp (ref "TP153")
      (value "TPSTP12R")
      (footprint "eagle-import:TP12R")
      (libsource (lib "eagle-import") (part "TPSTP12R"))
    )
    (comp (ref "TP154")
      (value "TPSTP12R")
      (footprint "eagle-import:TP12R")
      (libsource (lib "eagle-import") (part "TPSTP12R"))
    )
    (comp (ref "TP155")
      (value "TPSTP12R")
      (footprint "eagle-import:TP12R")
      (libsource (lib "eagle-import") (part "TPSTP12R"))
    )
    (comp (ref "TP156")
      (value "TPSTP12R")
      (footprint "eagle-import:TP12R")
      (libsource (lib "eagle-import") (part "TPSTP12R"))
    )
    (comp (ref "TP157")
      (value "TPSTP12R")
      (footprint "eagle-import:TP12R")
      (libsource (lib "eagle-import") (part "TPSTP12R"))
    )
    (comp (ref "TP158")
      (value "TPSTP12R")
      (footprint "eagle-import:TP12R")
      (libsource (lib "eagle-import") (part "TPSTP12R"))
    )
    (comp (ref "TP159")
      (value "TPSTP12R")
      (footprint "eagle-import:TP12R")
      (libsource (lib "eagle-import") (part "TPSTP12R"))
    )
    (comp (ref "TP160")
      (value "TPSTP12R")
      (footprint "eagle-import:TP12R")
      (libsource (lib "eagle-import") (part "TPSTP12R"))
    )
    (comp (ref "TP161")
      (value "TPSTP12R")
      (footprint "eagle-import:TP12R")
      (libsource (lib "eagle-import") (part "TPSTP12R"))
    )
    (comp (ref "TP162")
      (value "TPSTP12R")
      (footprint "eagle-import:TP12R")
      (libsource (lib "eagle-import") (part "TPSTP12R"))
    )
    (comp (ref "TP163")
      (value "TPSTP12R")
      (footprint "eagle-import:TP12R")
      (libsource (lib "eagle-import") (part "TPSTP12R"))
    )
    (comp (ref "TP164")
      (value "TPSTP12R")
      (footprint "eagle-import:TP12R")
      (libsource (lib "eagle-import") (part "TPSTP12R"))
    )
    (comp (ref "TP165")
      (value "TPSTP12R")
      (footprint "eagle-import:TP12R")
      (libsource (lib "eagle-import") (part "TPSTP12R"))
    )
    (comp (ref "TP166")
      (value "TPSTP12R")
      (footprint "eagle-import:TP12R")
      (libsource (lib "eagle-import") (part "TPSTP12R"))
    )
    (comp (ref "TP167")
      (value "TPSTP12R")
      (footprint "eagle-import:TP12R")
      (libsource (lib "eagle-import") (part "TPSTP12R"))
    )
    (comp (ref "TP168")
      (value "TPSTP12R")
      (footprint "eagle-import:TP12R")
      (libsource (lib "eagle-import") (part "TPSTP12R"))
    )
    (comp (ref "TP169")
      (value "TPSTP12R")
      (footprint "eagle-import:TP12R")
      (libsource (lib "eagle-import") (part "TPSTP12R"))
    )
    (comp (ref "TP170")
      (value "TPSTP12R")
      (footprint "eagle-import:TP12R")
      (libsource (lib "eagle-import") (part "TPSTP12R"))
    )
    (comp (ref "TP171")
      (value "TPSTP12R")
      (footprint "eagle-import:TP12R")
      (libsource (lib "eagle-import") (part "TPSTP12R"))
    )
    (comp (ref "TP172")
      (value "TPSTP12R")
      (footprint "eagle-import:TP12R")
      (libsource (lib "eagle-import") (part "TPSTP12R"))
    )
    (comp (ref "TP173")
      (value "TPSTP12R")
      (footprint "eagle-import:TP12R")
      (libsource (lib "eagle-import") (part "TPSTP12R"))
    )
    (comp (ref "TP174")
      (value "TPSTP12R")
      (footprint "eagle-import:TP12R")
      (libsource (lib "eagle-import") (part "TPSTP12R"))
    )
    (comp (ref "TP175")
      (value "TPSTP12R")
      (footprint "eagle-import:TP12R")
      (libsource (lib "eagle-import") (part "TPSTP12R"))
    )
    (comp (ref "TP176")
      (value "TPSTP12R")
      (footprint "eagle-import:TP12R")
      (libsource (lib "eagle-import") (part "TPSTP12R"))
    )
    (comp (ref "TP177")
      (value "TPSTP12R")
      (footprint "eagle-import:TP12R")
      (libsource (lib "eagle-import") (part "TPSTP12R"))
    )
    (comp (ref "TP178")
      (value "TPSTP12R")
      (footprint "eagle-import:TP12R")
      (libsource (lib "eagle-import") (part "TPSTP12R"))
    )
    (comp (ref "TP179")
      (value "TPSTP12R")
      (footprint "eagle-import:TP12R")
      (libsource (lib "eagle-import") (part "TPSTP12R"))
    )
    (comp (ref "TP180")
      (value "TPSTP12R")
      (footprint "eagle-import:TP12R")
      (libsource (lib "eagle-import") (part "TPSTP12R"))
    )
    (comp (ref "TP181")
      (value "TPSTP12R")
      (footprint "eagle-import:TP12R")
      (libsource (lib "eagle-import") (part "TPSTP12R"))
    )
    (comp (ref "TP182")
      (value "TPSTP12R")
      (footprint "eagle-import:TP12R")
      (libsource (lib "eagle-import") (part "TPSTP12R"))
    )
    (comp (ref "TP183")
      (value "TPSTP12R")
      (footprint "eagle-import:TP12R")
      (libsource (lib "eagle-import") (part "TPSTP12R"))
    )
    (comp (ref "TP184")
      (value "TPSTP12R")
      (footprint "eagle-import:TP12R")
      (libsource (lib "eagle-import") (part "TPSTP12R"))
    )
    (comp (ref "TP185")
      (value "TPSTP12R")
      (footprint "eagle-import:TP12R")
      (libsource (lib "eagle-import") (part "TPSTP12R"))
    )
    (comp (ref "TP186")
      (value "TPSTP12R")
      (footprint "eagle-import:TP12R")
      (libsource (lib "eagle-import") (part "TPSTP12R"))
    )
    (comp (ref "TP187")
      (value "TPSTP12R")
      (footprint "eagle-import:TP12R")
      (libsource (lib "eagle-import") (part "TPSTP12R"))
    )
    (comp (ref "TP188")
      (value "TPSTP12R")
      (footprint "eagle-import:TP12R")
      (libsource (lib "eagle-import") (part "TPSTP12R"))
    )
    (comp (ref "TP189")
      (value "TPSTP12R")
      (footprint "eagle-import:TP12R")
      (libsource (lib "eagle-import") (part "TPSTP12R"))
    )
    (comp (ref "TP190")
      (value "TPSTP12R")
      (footprint "eagle-import:TP12R")
      (libsource (lib "eagle-import") (part "TPSTP12R"))
    )
    (comp (ref "U1")
      (value "SN751177NSR\"")
      (footprint "eagle-import:SO16NS")
      (libsource (lib "eagle-import") (part "SN751177NSR{dblquote}"))
    )
    (comp (ref "U5")
      (value "SN751177NSR\"")
      (footprint "eagle-import:SO16NS")
      (libsource (lib "eagle-import") (part "SN751177NSR{dblquote}"))
    )
    (comp (ref "U8")
      (value "SN751177NSR\"")
      (footprint "eagle-import:SO16NS")
      (libsource (lib "eagle-import") (part "SN751177NSR{dblquote}"))
    )
    (comp (ref "U9")
      (value "SN751177NSR\"")
      (footprint "eagle-import:SO16NS")
      (libsource (lib "eagle-import") (part "SN751177NSR{dblquote}"))
    )
    (comp (ref "U11")
      (value "SN751177NSR\"")
      (footprint "eagle-import:SO16NS")
      (libsource (lib "eagle-import") (part "SN751177NSR{dblquote}"))
    )
    (comp (ref "U15")
      (value "SN751177NSR\"")
      (footprint "eagle-import:SO16NS")
      (libsource (lib "eagle-import") (part "SN751177NSR{dblquote}"))
    )
    (comp (ref "U18")
      (value "SN751177NSR\"")
      (footprint "eagle-import:SO16NS")
      (libsource (lib "eagle-import") (part "SN751177NSR{dblquote}"))
    )
    (comp (ref "U22")
      (value "SN751177NSR\"")
      (footprint "eagle-import:SO16NS")
      (libsource (lib "eagle-import") (part "SN751177NSR{dblquote}"))
    )
    (comp (ref "U26")
      (value "SN751177NSR\"")
      (footprint "eagle-import:SO16NS")
      (libsource (lib "eagle-import") (part "SN751177NSR{dblquote}"))
    )
    (comp (ref "U28")
      (value "SN751177NSR\"")
      (footprint "eagle-import:SO16NS")
      (libsource (lib "eagle-import") (part "SN751177NSR{dblquote}"))
    )
    (comp (ref "U2")
      (value "SN751177NSR\"")
      (footprint "eagle-import:SO16NS")
      (libsource (lib "eagle-import") (part "SN751177NSR{dblquote}"))
    )
    (comp (ref "U6")
      (value "SN751177NSR\"")
      (footprint "eagle-import:SO16NS")
      (libsource (lib "eagle-import") (part "SN751177NSR{dblquote}"))
    )
    (comp (ref "U10")
      (value "SN751177NSR\"")
      (footprint "eagle-import:SO16NS")
      (libsource (lib "eagle-import") (part "SN751177NSR{dblquote}"))
    )
    (comp (ref "U12")
      (value "SN751177NSR\"")
      (footprint "eagle-import:SO16NS")
      (libsource (lib "eagle-import") (part "SN751177NSR{dblquote}"))
    )
    (comp (ref "U16")
      (value "SN751177NSR\"")
      (footprint "eagle-import:SO16NS")
      (libsource (lib "eagle-import") (part "SN751177NSR{dblquote}"))
    )
    (comp (ref "U19")
      (value "SN751177NSR\"")
      (footprint "eagle-import:SO16NS")
      (libsource (lib "eagle-import") (part "SN751177NSR{dblquote}"))
    )
    (comp (ref "U23")
      (value "SN751177NSR\"")
      (footprint "eagle-import:SO16NS")
      (libsource (lib "eagle-import") (part "SN751177NSR{dblquote}"))
    )
    (comp (ref "U27")
      (value "SN751177NSR\"")
      (footprint "eagle-import:SO16NS")
      (libsource (lib "eagle-import") (part "SN751177NSR{dblquote}"))
    )
    (comp (ref "U29")
      (value "SN751177NSR\"")
      (footprint "eagle-import:SO16NS")
      (libsource (lib "eagle-import") (part "SN751177NSR{dblquote}"))
    )
  )
  (nets
    (net (code "1") (name "+5V") (class "Default")
      (node (ref "C1") (pin "+") (pinfunction "+_+") (pintype "passive"))
      (node (ref "C100") (pin "1") (pinfunction "1_1") (pintype "passive"))
      (node (ref "C101") (pin "1") (pinfunction "1_1") (pintype "passive"))
      (node (ref "C102") (pin "1") (pinfunction "1_1") (pintype "passive"))
      (node (ref "C103") (pin "1") (pinfunction "1_1") (pintype "passive"))
      (node (ref "C104") (pin "1") (pinfunction "1_1") (pintype "passive"))
      (node (ref "C105") (pin "1") (pinfunction "1_1") (pintype "passive"))
      (node (ref "C106") (pin "1") (pinfunction "1_1") (pintype "passive"))
      (node (ref "C107") (pin "1") (pinfunction "1_1") (pintype "passive"))
      (node (ref "C108") (pin "1") (pinfunction "1_1") (pintype "passive"))
      (node (ref "C109") (pin "1") (pinfunction "1_1") (pintype "passive"))
      (node (ref "C110") (pin "1") (pinfunction "1_1") (pintype "passive"))
      (node (ref "C111") (pin "1") (pinfunction "1_1") (pintype "passive"))
      (node (ref "C112") (pin "1") (pinfunction "1_1") (pintype "passive"))
      (node (ref "C113") (pin "1") (pinfunction "1_1") (pintype "passive"))
      (node (ref "C114") (pin "1") (pinfunction "1_1") (pintype "passive"))
      (node (ref "C115") (pin "1") (pinfunction "1_1") (pintype "passive"))
      (node (ref "C116") (pin "1") (pinfunction "1_1") (pintype "passive"))
      (node (ref "C117") (pin "1") (pinfunction "1_1") (pintype "passive"))
      (node (ref "C118") (pin "1") (pinfunction "1_1") (pintype "passive"))
      (node (ref "C119") (pin "1") (pinfunction "1_1") (pintype "passive"))
      (node (ref "C120") (pin "1") (pinfunction "1_1") (pintype "passive"))
      (node (ref "C121") (pin "1") (pinfunction "1_1") (pintype "passive"))
      (node (ref "C122") (pin "1") (pinfunction "1_1") (pintype "passive"))
      (node (ref "C123") (pin "1") (pinfunction "1_1") (pintype "passive"))
      (node (ref "C124") (pin "1") (pinfunction "1_1") (pintype "passive"))
      (node (ref "C125") (pin "1") (pinfunction "1_1") (pintype "passive"))
      (node (ref "C126") (pin "1") (pinfunction "1_1") (pintype "passive"))
      (node (ref "C127") (pin "1") (pinfunction "1_1") (pintype "passive"))
      (node (ref "C128") (pin "1") (pinfunction "1_1") (pintype "passive"))
      (node (ref "C129") (pin "1") (pinfunction "1_1") (pintype "passive"))
      (node (ref "C2") (pin "+") (pinfunction "+_+") (pintype "passive"))
      (node (ref "C3") (pin "+") (pinfunction "+_+") (pintype "passive"))
      (node (ref "C4") (pin "+") (pinfunction "+_+") (pintype "passive"))
      (node (ref "C5") (pin "+") (pinfunction "+_+") (pintype "passive"))
      (node (ref "C6") (pin "+") (pinfunction "+_+") (pintype "passive"))
      (node (ref "J1") (pin "PIN") (pinfunction "PIN_PIN") (pintype "passive"))
      (node (ref "Q1") (pin "1") (pinfunction "S_1") (pintype "passive"))
      (node (ref "Q1") (pin "3") (pinfunction "S_3") (pintype "passive"))
      (node (ref "Q2") (pin "1") (pinfunction "S_1") (pintype "passive"))
      (node (ref "R1") (pin "2") (pinfunction "2_2") (pintype "passive"))
      (node (ref "R108") (pin "2") (pinfunction "2_2") (pintype "passive"))
      (node (ref "R109") (pin "1") (pinfunction "1_1") (pintype "passive"))
      (node (ref "R110") (pin "2") (pinfunction "2_2") (pintype "passive"))
      (node (ref "R111") (pin "2") (pinfunction "2_2") (pintype "passive"))
      (node (ref "R113") (pin "2") (pinfunction "2_2") (pintype "passive"))
      (node (ref "R122") (pin "1") (pinfunction "1_1") (pintype "passive"))
      (node (ref "R123") (pin "1") (pinfunction "1_1") (pintype "passive"))
      (node (ref "U1") (pin "16") (pinfunction "VCC_16") (pintype "power_in"))
      (node (ref "U10") (pin "16") (pinfunction "VCC_16") (pintype "power_in"))
      (node (ref "U11") (pin "16") (pinfunction "VCC_16") (pintype "power_in"))
      (node (ref "U12") (pin "16") (pinfunction "VCC_16") (pintype "power_in"))
      (node (ref "U13") (pin "16") (pinfunction "VCC_16") (pintype "power_in"))
      (node (ref "U14") (pin "16") (pinfunction "VCC_16") (pintype "power_in"))
      (node (ref "U15") (pin "16") (pinfunction "VCC_16") (pintype "power_in"))
      (node (ref "U16") (pin "16") (pinfunction "VCC_16") (pintype "power_in"))
      (node (ref "U17") (pin "16") (pinfunction "VCC_16") (pintype "power_in"))
      (node (ref "U18") (pin "16") (pinfunction "VCC_16") (pintype "power_in"))
      (node (ref "U19") (pin "16") (pinfunction "VCC_16") (pintype "power_in"))
      (node (ref "U2") (pin "16") (pinfunction "VCC_16") (pintype "power_in"))
      (node (ref "U20") (pin "16") (pinfunction "VCC_16") (pintype "power_in"))
      (node (ref "U21") (pin "5") (pinfunction "VCC_5") (pintype "power_in"))
      (node (ref "U22") (pin "16") (pinfunction "VCC_16") (pintype "power_in"))
      (node (ref "U23") (pin "16") (pinfunction "VCC_16") (pintype "power_in"))
      (node (ref "U24") (pin "16") (pinfunction "VCC_16") (pintype "power_in"))
      (node (ref "U25") (pin "16") (pinfunction "VCC_16") (pintype "power_in"))
      (node (ref "U26") (pin "16") (pinfunction "VCC_16") (pintype "power_in"))
      (node (ref "U27") (pin "16") (pinfunction "VCC_16") (pintype "power_in"))
      (node (ref "U28") (pin "16") (pinfunction "VCC_16") (pintype "power_in"))
      (node (ref "U29") (pin "16") (pinfunction "VCC_16") (pintype "power_in"))
      (node (ref "U3") (pin "16") (pinfunction "VCC_16") (pintype "power_in"))
      (node (ref "U30") (pin "16") (pinfunction "VCC_16") (pintype "power_in"))
      (node (ref "U4") (pin "16") (pinfunction "VCC_16") (pintype "power_in"))
      (node (ref "U5") (pin "16") (pinfunction "VCC_16") (pintype "power_in"))
      (node (ref "U6") (pin "16") (pinfunction "VCC_16") (pintype "power_in"))
      (node (ref "U7") (pin "16") (pinfunction "VCC_16") (pintype "power_in"))
      (node (ref "U8") (pin "16") (pinfunction "VCC_16") (pintype "power_in"))
      (node (ref "U9") (pin "16") (pinfunction "VCC_16") (pintype "power_in"))
    )
    (net (code "2") (name "CABLE_A_FAIL") (class "Default")
      (node (ref "D102") (pin "3") (pinfunction "AC_3") (pintype "passive"))
      (node (ref "P4") (pin "39") (pinfunction "1_39") (pintype "passive"))
      (node (ref "P7") (pin "39") (pinfunction "1_39") (pintype "passive"))
      (node (ref "Q1") (pin "2") (pinfunction "G_2") (pintype "passive"))
      (node (ref "R111") (pin "1") (pinfunction "1_1") (pintype "passive"))
    )
    (net (code "3") (name "CABLE_B_FAIL") (class "Default")
      (node (ref "D101") (pin "3") (pinfunction "AC_3") (pintype "passive"))
      (node (ref "P5") (pin "39") (pinfunction "1_39") (pintype "passive"))
      (node (ref "P8") (pin "39") (pinfunction "1_39") (pintype "passive"))
      (node (ref "Q1") (pin "4") (pinfunction "G_4") (pintype "passive"))
      (node (ref "R110") (pin "1") (pinfunction "1_1") (pintype "passive"))
    )
    (net (code "4") (name "CABLE_C_FAIL") (class "Default")
      (node (ref "D100") (pin "3") (pinfunction "AC_3") (pintype "passive"))
      (node (ref "P6") (pin "39") (pinfunction "1_39") (pintype "passive"))
      (node (ref "P9") (pin "39") (pinfunction "1_39") (pintype "passive"))
      (node (ref "Q2") (pin "2") (pinfunction "G_2") (pintype "passive"))
      (node (ref "R108") (pin "1") (pinfunction "1_1") (pintype "passive"))
    )
    (net (code "5") (name "CLAMP") (class "Default")
      (node (ref "D100") (pin "2") (pinfunction "C_2") (pintype "passive"))
      (node (ref "D101") (pin "2") (pinfunction "C_2") (pintype "passive"))
      (node (ref "D102") (pin "2") (pinfunction "C_2") (pintype "passive"))
      (node (ref "D103") (pin "C") (pinfunction "C_C") (pintype "passive"))
    )
    (net (code "6") (name "CTRL_BUS_EN") (class "Default")
      (node (ref "P2") (pin "7") (pinfunction "1_7") (pintype "passive"))
      (node (ref "U10") (pin "12") (pinfunction "DE_12") (pintype "bidirectional"))
      (node (ref "U12") (pin "12") (pinfunction "DE_12") (pintype "bidirectional"))
      (node (ref "U16") (pin "12") (pinfunction "DE_12") (pintype "bidirectional"))
      (node (ref "U19") (pin "12") (pinfunction "DE_12") (pintype "bidirectional"))
      (node (ref "U2") (pin "12") (pinfunction "DE_12") (pintype "bidirectional"))
      (node (ref "U23") (pin "12") (pinfunction "DE_12") (pintype "bidirectional"))
      (node (ref "U27") (pin "12") (pinfunction "DE_12") (pintype "bidirectional"))
      (node (ref "U29") (pin "12") (pinfunction "DE_12") (pintype "bidirectional"))
      (node (ref "U6") (pin "12") (pinfunction "DE_12") (pintype "bidirectional"))
    )
    (net (code "7") (name "FROM_MB_CTOD") (class "Default")
      (node (ref "P2") (pin "11") (pinfunction "1_11") (pintype "passive"))
      (node (ref "U14") (pin "5") (pinfunction "2R_5") (pintype "bidirectional"))
    )
    (net (code "8") (name "FROM_MB_DEM") (class "Default")
      (node (ref "P3") (pin "25") (pinfunction "1_25") (pintype "passive"))
      (node (ref "U30") (pin "3") (pinfunction "1R_3") (pintype "bidirectional"))
    )
    (net (code "9") (name "FROM_MB_DS00") (class "Default")
      (node (ref "P1") (pin "37") (pinfunction "1_37") (pintype "passive"))
      (node (ref "U4") (pin "5") (pinfunction "2R_5") (pintype "bidirectional"))
    )
    (net (code "10") (name "FROM_MB_DS01") (class "Default")
      (node (ref "P3") (pin "27") (pinfunction "1_27") (pintype "passive"))
      (node (ref "U20") (pin "3") (pinfunction "1R_3") (pintype "bidirectional"))
    )
    (net (code "11") (name "FROM_MB_DS02") (class "Default")
      (node (ref "P3") (pin "29") (pinfunction "1_29") (pintype "passive"))
      (node (ref "U20") (pin "5") (pinfunction "2R_5") (pintype "bidirectional"))
    )
    (net (code "12") (name "FROM_MB_FAIL") (class "Default")
      (node (ref "P3") (pin "31") (pinfunction "1_31") (pintype "passive"))
      (node (ref "U21") (pin "4") (pinfunction "Y_4") (pintype "output"))
    )
    (net (code "13") (name "FROM_MB_INIT") (class "Default")
      (node (ref "P2") (pin "15") (pinfunction "1_15") (pintype "passive"))
      (node (ref "U25") (pin "5") (pinfunction "2R_5") (pintype "bidirectional"))
    )
    (net (code "14") (name "FROM_MB_RS00") (class "Default")
      (node (ref "P2") (pin "45") (pinfunction "1_45") (pintype "passive"))
      (node (ref "U17") (pin "3") (pinfunction "1R_3") (pintype "bidirectional"))
    )
    (net (code "15") (name "FROM_MB_RS01") (class "Default")
      (node (ref "P2") (pin "47") (pinfunction "1_47") (pintype "passive"))
      (node (ref "U17") (pin "5") (pinfunction "2R_5") (pintype "bidirectional"))
    )
    (net (code "16") (name "FROM_MB_RS02") (class "Default")
      (node (ref "P1") (pin "27") (pinfunction "1_27") (pintype "passive"))
      (node (ref "U13") (pin "3") (pinfunction "1R_3") (pintype "bidirectional"))
    )
    (net (code "17") (name "FROM_MB_RS03") (class "Default")
      (node (ref "P1") (pin "29") (pinfunction "1_29") (pintype "passive"))
      (node (ref "U13") (pin "5") (pinfunction "2R_5") (pintype "bidirectional"))
    )
    (net (code "18") (name "FROM_MB_RS04") (class "Default")
      (node (ref "P1") (pin "35") (pinfunction "1_35") (pintype "passive"))
      (node (ref "U4") (pin "3") (pinfunction "1R_3") (pintype "bidirectional"))
    )
    (net (code "19") (name "FROM_MB_RUN") (class "Default")
      (node (ref "P2") (pin "13") (pinfunction "1_13") (pintype "passive"))
      (node (ref "U25") (pin "3") (pinfunction "1R_3") (pintype "bidirectional"))
    )
    (net (code "20") (name "FROM_MB_WCLK") (class "Default")
      (node (ref "P2") (pin "9") (pinfunction "1_9") (pintype "passive"))
      (node (ref "U14") (pin "3") (pinfunction "1R_3") (pintype "bidirectional"))
    )
    (net (code "21") (name "GND") (class "Default")
      (node (ref "C1") (pin "-") (pinfunction "-_-") (pintype "passive"))
      (node (ref "C100") (pin "2") (pinfunction "2_2") (pintype "passive"))
      (node (ref "C101") (pin "2") (pinfunction "2_2") (pintype "passive"))
      (node (ref "C102") (pin "2") (pinfunction "2_2") (pintype "passive"))
      (node (ref "C103") (pin "2") (pinfunction "2_2") (pintype "passive"))
      (node (ref "C104") (pin "2") (pinfunction "2_2") (pintype "passive"))
      (node (ref "C105") (pin "2") (pinfunction "2_2") (pintype "passive"))
      (node (ref "C106") (pin "2") (pinfunction "2_2") (pintype "passive"))
      (node (ref "C107") (pin "2") (pinfunction "2_2") (pintype "passive"))
      (node (ref "C108") (pin "2") (pinfunction "2_2") (pintype "passive"))
      (node (ref "C109") (pin "2") (pinfunction "2_2") (pintype "passive"))
      (node (ref "C110") (pin "2") (pinfunction "2_2") (pintype "passive"))
      (node (ref "C111") (pin "2") (pinfunction "2_2") (pintype "passive"))
      (node (ref "C112") (pin "2") (pinfunction "2_2") (pintype "passive"))
      (node (ref "C113") (pin "2") (pinfunction "2_2") (pintype "passive"))
      (node (ref "C114") (pin "2") (pinfunction "2_2") (pintype "passive"))
      (node (ref "C115") (pin "2") (pinfunction "2_2") (pintype "passive"))
      (node (ref "C116") (pin "2") (pinfunction "2_2") (pintype "passive"))
      (node (ref "C117") (pin "2") (pinfunction "2_2") (pintype "passive"))
      (node (ref "C118") (pin "2") (pinfunction "2_2") (pintype "passive"))
      (node (ref "C119") (pin "2") (pinfunction "2_2") (pintype "passive"))
      (node (ref "C120") (pin "2") (pinfunction "2_2") (pintype "passive"))
      (node (ref "C121") (pin "2") (pinfunction "2_2") (pintype "passive"))
      (node (ref "C122") (pin "2") (pinfunction "2_2") (pintype "passive"))
      (node (ref "C123") (pin "2") (pinfunction "2_2") (pintype "passive"))
      (node (ref "C124") (pin "2") (pinfunction "2_2") (pintype "passive"))
      (node (ref "C125") (pin "2") (pinfunction "2_2") (pintype "passive"))
      (node (ref "C126") (pin "2") (pinfunction "2_2") (pintype "passive"))
      (node (ref "C127") (pin "2") (pinfunction "2_2") (pintype "passive"))
      (node (ref "C128") (pin "2") (pinfunction "2_2") (pintype "passive"))
      (node (ref "C129") (pin "2") (pinfunction "2_2") (pintype "passive"))
      (node (ref "C2") (pin "-") (pinfunction "-_-") (pintype "passive"))
      (node (ref "C3") (pin "-") (pinfunction "-_-") (pintype "passive"))
      (node (ref "C4") (pin "-") (pinfunction "-_-") (pintype "passive"))
      (node (ref "C5") (pin "-") (pinfunction "-_-") (pintype "passive"))
      (node (ref "C6") (pin "-") (pinfunction "-_-") (pintype "passive"))
      (node (ref "D100") (pin "1") (pinfunction "A_1") (pintype "passive"))
      (node (ref "D101") (pin "1") (pinfunction "A_1") (pintype "passive"))
      (node (ref "D102") (pin "1") (pinfunction "A_1") (pintype "passive"))
      (node (ref "D103") (pin "A") (pinfunction "A_A") (pintype "passive"))
      (node (ref "J1") (pin "SLEEVE") (pinfunction "SLEEVE_SLEEVE") (pintype "passive"))
      (node (ref "J1") (pin "SLEEVE_SHUNT") (pinfunction "SLEEVE_SHUNT_SLEEVE_SHUNT") (pintype "passive"))
      (node (ref "LED1") (pin "C") (pinfunction "C_C") (pintype "passive"))
      (node (ref "LED2") (pin "C") (pinfunction "C_C") (pintype "passive"))
      (node (ref "LED3") (pin "C") (pinfunction "C_C") (pintype "passive"))
      (node (ref "LED4") (pin "C") (pinfunction "C_C") (pintype "passive"))
      (node (ref "P1") (pin "10") (pinfunction "1_10") (pintype "passive"))
      (node (ref "P1") (pin "12") (pinfunction "1_12") (pintype "passive"))
      (node (ref "P1") (pin "14") (pinfunction "1_14") (pintype "passive"))
      (node (ref "P1") (pin "16") (pinfunction "1_16") (pintype "passive"))
      (node (ref "P1") (pin "18") (pinfunction "1_18") (pintype "passive"))
      (node (ref "P1") (pin "2") (pinfunction "1_2") (pintype "passive"))
      (node (ref "P1") (pin "20") (pinfunction "1_20") (pintype "passive"))
      (node (ref "P1") (pin "22") (pinfunction "1_22") (pintype "passive"))
      (node (ref "P1") (pin "24") (pinfunction "1_24") (pintype "passive"))
      (node (ref "P1") (pin "26") (pinfunction "1_26") (pintype "passive"))
      (node (ref "P1") (pin "28") (pinfunction "1_28") (pintype "passive"))
      (node (ref "P1") (pin "30") (pinfunction "1_30") (pintype "passive"))
      (node (ref "P1") (pin "32") (pinfunction "1_32") (pintype "passive"))
      (node (ref "P1") (pin "34") (pinfunction "1_34") (pintype "passive"))
      (node (ref "P1") (pin "36") (pinfunction "1_36") (pintype "passive"))
      (node (ref "P1") (pin "38") (pinfunction "1_38") (pintype "passive"))
      (node (ref "P1") (pin "4") (pinfunction "1_4") (pintype "passive"))
      (node (ref "P1") (pin "40") (pinfunction "1_40") (pintype "passive"))
      (node (ref "P1") (pin "42") (pinfunction "1_42") (pintype "passive"))
      (node (ref "P1") (pin "44") (pinfunction "1_44") (pintype "passive"))
      (node (ref "P1") (pin "46") (pinfunction "1_46") (pintype "passive"))
      (node (ref "P1") (pin "48") (pinfunction "1_48") (pintype "passive"))
      (node (ref "P1") (pin "50") (pinfunction "1_50") (pintype "passive"))
      (node (ref "P1") (pin "6") (pinfunction "1_6") (pintype "passive"))
      (node (ref "P1") (pin "8") (pinfunction "1_8") (pintype "passive"))
      (node (ref "P10") (pin "40") (pinfunction "1_40") (pintype "passive"))
      (node (ref "P11") (pin "40") (pinfunction "1_40") (pintype "passive"))
      (node (ref "P12") (pin "40") (pinfunction "1_40") (pintype "passive"))
      (node (ref "P2") (pin "10") (pinfunction "1_10") (pintype "passive"))
      (node (ref "P2") (pin "12") (pinfunction "1_12") (pintype "passive"))
      (node (ref "P2") (pin "14") (pinfunction "1_14") (pintype "passive"))
      (node (ref "P2") (pin "16") (pinfunction "1_16") (pintype "passive"))
      (node (ref "P2") (pin "18") (pinfunction "1_18") (pintype "passive"))
      (node (ref "P2") (pin "2") (pinfunction "1_2") (pintype "passive"))
      (node (ref "P2") (pin "20") (pinfunction "1_20") (pintype "passive"))
      (node (ref "P2") (pin "22") (pinfunction "1_22") (pintype "passive"))
      (node (ref "P2") (pin "24") (pinfunction "1_24") (pintype "passive"))
      (node (ref "P2") (pin "26") (pinfunction "1_26") (pintype "passive"))
      (node (ref "P2") (pin "28") (pinfunction "1_28") (pintype "passive"))
      (node (ref "P2") (pin "30") (pinfunction "1_30") (pintype "passive"))
      (node (ref "P2") (pin "32") (pinfunction "1_32") (pintype "passive"))
      (node (ref "P2") (pin "34") (pinfunction "1_34") (pintype "passive"))
      (node (ref "P2") (pin "36") (pinfunction "1_36") (pintype "passive"))
      (node (ref "P2") (pin "38") (pinfunction "1_38") (pintype "passive"))
      (node (ref "P2") (pin "4") (pinfunction "1_4") (pintype "passive"))
      (node (ref "P2") (pin "40") (pinfunction "1_40") (pintype "passive"))
      (node (ref "P2") (pin "42") (pinfunction "1_42") (pintype "passive"))
      (node (ref "P2") (pin "44") (pinfunction "1_44") (pintype "passive"))
      (node (ref "P2") (pin "46") (pinfunction "1_46") (pintype "passive"))
      (node (ref "P2") (pin "48") (pinfunction "1_48") (pintype "passive"))
      (node (ref "P2") (pin "50") (pinfunction "1_50") (pintype "passive"))
      (node (ref "P2") (pin "6") (pinfunction "1_6") (pintype "passive"))
      (node (ref "P2") (pin "8") (pinfunction "1_8") (pintype "passive"))
      (node (ref "P3") (pin "10") (pinfunction "1_10") (pintype "passive"))
      (node (ref "P3") (pin "12") (pinfunction "1_12") (pintype "passive"))
      (node (ref "P3") (pin "14") (pinfunction "1_14") (pintype "passive"))
      (node (ref "P3") (pin "16") (pinfunction "1_16") (pintype "passive"))
      (node (ref "P3") (pin "18") (pinfunction "1_18") (pintype "passive"))
      (node (ref "P3") (pin "2") (pinfunction "1_2") (pintype "passive"))
      (node (ref "P3") (pin "20") (pinfunction "1_20") (pintype "passive"))
      (node (ref "P3") (pin "22") (pinfunction "1_22") (pintype "passive"))
      (node (ref "P3") (pin "24") (pinfunction "1_24") (pintype "passive"))
      (node (ref "P3") (pin "26") (pinfunction "1_26") (pintype "passive"))
      (node (ref "P3") (pin "28") (pinfunction "1_28") (pintype "passive"))
      (node (ref "P3") (pin "30") (pinfunction "1_30") (pintype "passive"))
      (node (ref "P3") (pin "32") (pinfunction "1_32") (pintype "passive"))
      (node (ref "P3") (pin "34") (pinfunction "1_34") (pintype "passive"))
      (node (ref "P3") (pin "36") (pinfunction "1_36") (pintype "passive"))
      (node (ref "P3") (pin "38") (pinfunction "1_38") (pintype "passive"))
      (node (ref "P3") (pin "4") (pinfunction "1_4") (pintype "passive"))
      (node (ref "P3") (pin "40") (pinfunction "1_40") (pintype "passive"))
      (node (ref "P3") (pin "42") (pinfunction "1_42") (pintype "passive"))
      (node (ref "P3") (pin "44") (pinfunction "1_44") (pintype "passive"))
      (node (ref "P3") (pin "46") (pinfunction "1_46") (pintype "passive"))
      (node (ref "P3") (pin "48") (pinfunction "1_48") (pintype "passive"))
      (node (ref "P3") (pin "50") (pinfunction "1_50") (pintype "passive"))
      (node (ref "P3") (pin "6") (pinfunction "1_6") (pintype "passive"))
      (node (ref "P3") (pin "8") (pinfunction "1_8") (pintype "passive"))
      (node (ref "P4") (pin "40") (pinfunction "1_40") (pintype "passive"))
      (node (ref "P5") (pin "40") (pinfunction "1_40") (pintype "passive"))
      (node (ref "P6") (pin "40") (pinfunction "1_40") (pintype "passive"))
      (node (ref "P7") (pin "40") (pinfunction "1_40") (pintype "passive"))
      (node (ref "P8") (pin "40") (pinfunction "1_40") (pintype "passive"))
      (node (ref "P9") (pin "40") (pinfunction "1_40") (pintype "passive"))
      (node (ref "R100") (pin "16") (pinfunction "16_16") (pintype "passive"))
      (node (ref "R101") (pin "16") (pinfunction "16_16") (pintype "passive"))
      (node (ref "R102") (pin "16") (pinfunction "16_16") (pintype "passive"))
      (node (ref "R103") (pin "16") (pinfunction "16_16") (pintype "passive"))
      (node (ref "R104") (pin "16") (pinfunction "16_16") (pintype "passive"))
      (node (ref "R105") (pin "16") (pinfunction "16_16") (pintype "passive"))
      (node (ref "R106") (pin "16") (pinfunction "16_16") (pintype "passive"))
      (node (ref "R107") (pin "16") (pinfunction "16_16") (pintype "passive"))
      (node (ref "R112") (pin "2") (pinfunction "2_2") (pintype "passive"))
      (node (ref "R114") (pin "2") (pinfunction "2_2") (pintype "passive"))
      (node (ref "R115") (pin "2") (pinfunction "2_2") (pintype "passive"))
      (node (ref "R116") (pin "2") (pinfunction "2_2") (pintype "passive"))
      (node (ref "R117") (pin "2") (pinfunction "2_2") (pintype "passive"))
      (node (ref "R118") (pin "2") (pinfunction "2_2") (pintype "passive"))
      (node (ref "R119") (pin "2") (pinfunction "2_2") (pintype "passive"))
      (node (ref "R120") (pin "1") (pinfunction "1_1") (pintype "passive"))
      (node (ref "R121") (pin "1") (pinfunction "1_1") (pintype "passive"))
      (node (ref "U1") (pin "8") (pinfunction "GND_8") (pintype "power_in"))
      (node (ref "U10") (pin "8") (pinfunction "GND_8") (pintype "power_in"))
      (node (ref "U11") (pin "8") (pinfunction "GND_8") (pintype "power_in"))
      (node (ref "U12") (pin "8") (pinfunction "GND_8") (pintype "power_in"))
      (node (ref "U13") (pin "8") (pinfunction "GND_8") (pintype "power_in"))
      (node (ref "U14") (pin "8") (pinfunction "GND_8") (pintype "power_in"))
      (node (ref "U15") (pin "8") (pinfunction "GND_8") (pintype "power_in"))
      (node (ref "U16") (pin "8") (pinfunction "GND_8") (pintype "power_in"))
      (node (ref "U17") (pin "8") (pinfunction "GND_8") (pintype "power_in"))
      (node (ref "U18") (pin "8") (pinfunction "GND_8") (pintype "power_in"))
      (node (ref "U19") (pin "8") (pinfunction "GND_8") (pintype "power_in"))
      (node (ref "U2") (pin "8") (pinfunction "GND_8") (pintype "power_in"))
      (node (ref "U20") (pin "8") (pinfunction "GND_8") (pintype "power_in"))
      (node (ref "U21") (pin "2") (pinfunction "GND_2") (pintype "power_in"))
      (node (ref "U22") (pin "8") (pinfunction "GND_8") (pintype "power_in"))
      (node (ref "U23") (pin "8") (pinfunction "GND_8") (pintype "power_in"))
      (node (ref "U24") (pin "8") (pinfunction "GND_8") (pintype "power_in"))
      (node (ref "U25") (pin "8") (pinfunction "GND_8") (pintype "power_in"))
      (node (ref "U26") (pin "8") (pinfunction "GND_8") (pintype "power_in"))
      (node (ref "U27") (pin "8") (pinfunction "GND_8") (pintype "power_in"))
      (node (ref "U28") (pin "8") (pinfunction "GND_8") (pintype "power_in"))
      (node (ref "U29") (pin "8") (pinfunction "GND_8") (pintype "power_in"))
      (node (ref "U3") (pin "8") (pinfunction "GND_8") (pintype "power_in"))
      (node (ref "U30") (pin "8") (pinfunction "GND_8") (pintype "power_in"))
      (node (ref "U4") (pin "8") (pinfunction "GND_8") (pintype "power_in"))
      (node (ref "U5") (pin "8") (pinfunction "GND_8") (pintype "power_in"))
      (node (ref "U6") (pin "8") (pinfunction "GND_8") (pintype "power_in"))
      (node (ref "U7") (pin "8") (pinfunction "GND_8") (pintype "power_in"))
      (node (ref "U8") (pin "8") (pinfunction "GND_8") (pintype "power_in"))
      (node (ref "U9") (pin "8") (pinfunction "GND_8") (pintype "power_in"))
    )
    (net (code "22") (name "IEL_DRVH") (class "Default")
      (node (ref "P2") (pin "1") (pinfunction "1_1") (pintype "passive"))
      (node (ref "P2") (pin "5") (pinfunction "1_5") (pintype "passive"))
      (node (ref "U1") (pin "12") (pinfunction "DE_12") (pintype "bidirectional"))
      (node (ref "U1") (pin "4") (pinfunction "~{RE}_4") (pintype "bidirectional"))
      (node (ref "U11") (pin "12") (pinfunction "DE_12") (pintype "bidirectional"))
      (node (ref "U11") (pin "4") (pinfunction "~{RE}_4") (pintype "bidirectional"))
      (node (ref "U15") (pin "12") (pinfunction "DE_12") (pintype "bidirectional"))
      (node (ref "U15") (pin "4") (pinfunction "~{RE}_4") (pintype "bidirectional"))
      (node (ref "U18") (pin "12") (pinfunction "DE_12") (pintype "bidirectional"))
      (node (ref "U18") (pin "4") (pinfunction "~{RE}_4") (pintype "bidirectional"))
      (node (ref "U22") (pin "12") (pinfunction "DE_12") (pintype "bidirectional"))
      (node (ref "U22") (pin "4") (pinfunction "~{RE}_4") (pintype "bidirectional"))
      (node (ref "U26") (pin "12") (pinfunction "DE_12") (pintype "bidirectional"))
      (node (ref "U26") (pin "4") (pinfunction "~{RE}_4") (pintype "bidirectional"))
      (node (ref "U28") (pin "12") (pinfunction "DE_12") (pintype "bidirectional"))
      (node (ref "U28") (pin "4") (pinfunction "~{RE}_4") (pintype "bidirectional"))
      (node (ref "U5") (pin "12") (pinfunction "DE_12") (pintype "bidirectional"))
      (node (ref "U5") (pin "4") (pinfunction "~{RE}_4") (pintype "bidirectional"))
      (node (ref "U8") (pin "12") (pinfunction "DE_12") (pintype "bidirectional"))
      (node (ref "U8") (pin "4") (pinfunction "~{RE}_4") (pintype "bidirectional"))
      (node (ref "U9") (pin "12") (pinfunction "DE_12") (pintype "bidirectional"))
      (node (ref "U9") (pin "4") (pinfunction "~{RE}_4") (pintype "bidirectional"))
    )
    (net (code "23") (name "MB_ATTN_N") (class "Default")
      (node (ref "P4") (pin "30") (pinfunction "1_30") (pintype "passive"))
      (node (ref "P7") (pin "30") (pinfunction "1_30") (pintype "passive"))
      (node (ref "U24") (pin "11") (pinfunction "~{2Z}_11") (pintype "bidirectional"))
    )
    (net (code "24") (name "MB_ATTN_P") (class "Default")
      (node (ref "P4") (pin "29") (pinfunction "1_29") (pintype "passive"))
      (node (ref "P7") (pin "29") (pinfunction "1_29") (pintype "passive"))
      (node (ref "U24") (pin "10") (pinfunction "2Y_10") (pintype "bidirectional"))
    )
    (net (code "25") (name "MB_C00_N") (class "Default")
      (node (ref "P4") (pin "13") (pinfunction "1_13") (pintype "passive"))
      (node (ref "P7") (pin "13") (pinfunction "1_13") (pintype "passive"))
      (node (ref "U2") (pin "1") (pinfunction "~{1B}_1") (pintype "bidirectional"))
      (node (ref "U2") (pin "13") (pinfunction "~{1Z}_13") (pintype "bidirectional"))
    )
    (net (code "26") (name "MB_C00_P") (class "Default")
      (node (ref "P4") (pin "14") (pinfunction "1_14") (pintype "passive"))
      (node (ref "P7") (pin "14") (pinfunction "1_14") (pintype "passive"))
      (node (ref "U2") (pin "14") (pinfunction "1Y_14") (pintype "bidirectional"))
      (node (ref "U2") (pin "2") (pinfunction "1A_2") (pintype "bidirectional"))
    )
    (net (code "27") (name "MB_C01_N") (class "Default")
      (node (ref "P4") (pin "16") (pinfunction "1_16") (pintype "passive"))
      (node (ref "P7") (pin "16") (pinfunction "1_16") (pintype "passive"))
      (node (ref "U2") (pin "11") (pinfunction "~{2Z}_11") (pintype "bidirectional"))
      (node (ref "U2") (pin "7") (pinfunction "~{2B}_7") (pintype "bidirectional"))
    )
    (net (code "28") (name "MB_C01_P") (class "Default")
      (node (ref "P4") (pin "15") (pinfunction "1_15") (pintype "passive"))
      (node (ref "P7") (pin "15") (pinfunction "1_15") (pintype "passive"))
      (node (ref "U2") (pin "10") (pinfunction "2Y_10") (pintype "bidirectional"))
      (node (ref "U2") (pin "6") (pinfunction "2A_6") (pintype "bidirectional"))
    )
    (net (code "29") (name "MB_C02_N") (class "Default")
      (node (ref "P4") (pin "17") (pinfunction "1_17") (pintype "passive"))
      (node (ref "P7") (pin "17") (pinfunction "1_17") (pintype "passive"))
      (node (ref "U12") (pin "1") (pinfunction "~{1B}_1") (pintype "bidirectional"))
      (node (ref "U12") (pin "13") (pinfunction "~{1Z}_13") (pintype "bidirectional"))
    )
    (net (code "30") (name "MB_C02_P") (class "Default")
      (node (ref "P4") (pin "18") (pinfunction "1_18") (pintype "passive"))
      (node (ref "P7") (pin "18") (pinfunction "1_18") (pintype "passive"))
      (node (ref "U12") (pin "14") (pinfunction "1Y_14") (pintype "bidirectional"))
      (node (ref "U12") (pin "2") (pinfunction "1A_2") (pintype "bidirectional"))
    )
    (net (code "31") (name "MB_C03_N") (class "Default")
      (node (ref "P4") (pin "20") (pinfunction "1_20") (pintype "passive"))
      (node (ref "P7") (pin "20") (pinfunction "1_20") (pintype "passive"))
      (node (ref "U12") (pin "11") (pinfunction "~{2Z}_11") (pintype "bidirectional"))
      (node (ref "U12") (pin "7") (pinfunction "~{2B}_7") (pintype "bidirectional"))
    )
    (net (code "32") (name "MB_C03_P") (class "Default")
      (node (ref "P4") (pin "19") (pinfunction "1_19") (pintype "passive"))
      (node (ref "P7") (pin "19") (pinfunction "1_19") (pintype "passive"))
      (node (ref "U12") (pin "10") (pinfunction "2Y_10") (pintype "bidirectional"))
      (node (ref "U12") (pin "6") (pinfunction "2A_6") (pintype "bidirectional"))
    )
    (net (code "33") (name "MB_C04_N") (class "Default")
      (node (ref "P4") (pin "21") (pinfunction "1_21") (pintype "passive"))
      (node (ref "P7") (pin "21") (pinfunction "1_21") (pintype "passive"))
      (node (ref "U23") (pin "1") (pinfunction "~{1B}_1") (pintype "bidirectional"))
      (node (ref "U23") (pin "13") (pinfunction "~{1Z}_13") (pintype "bidirectional"))
    )
    (net (code "34") (name "MB_C04_P") (class "Default")
      (node (ref "P4") (pin "22") (pinfunction "1_22") (pintype "passive"))
      (node (ref "P7") (pin "22") (pinfunction "1_22") (pintype "passive"))
      (node (ref "U23") (pin "14") (pinfunction "1Y_14") (pintype "bidirectional"))
      (node (ref "U23") (pin "2") (pinfunction "1A_2") (pintype "bidirectional"))
    )
    (net (code "35") (name "MB_C05_N") (class "Default")
      (node (ref "P4") (pin "24") (pinfunction "1_24") (pintype "passive"))
      (node (ref "P7") (pin "24") (pinfunction "1_24") (pintype "passive"))
      (node (ref "U23") (pin "11") (pinfunction "~{2Z}_11") (pintype "bidirectional"))
      (node (ref "U23") (pin "7") (pinfunction "~{2B}_7") (pintype "bidirectional"))
    )
    (net (code "36") (name "MB_C05_P") (class "Default")
      (node (ref "P4") (pin "23") (pinfunction "1_23") (pintype "passive"))
      (node (ref "P7") (pin "23") (pinfunction "1_23") (pintype "passive"))
      (node (ref "U23") (pin "10") (pinfunction "2Y_10") (pintype "bidirectional"))
      (node (ref "U23") (pin "6") (pinfunction "2A_6") (pintype "bidirectional"))
    )
    (net (code "37") (name "MB_C06_N") (class "Default")
      (node (ref "P5") (pin "13") (pinfunction "1_13") (pintype "passive"))
      (node (ref "P8") (pin "13") (pinfunction "1_13") (pintype "passive"))
      (node (ref "U6") (pin "1") (pinfunction "~{1B}_1") (pintype "bidirectional"))
      (node (ref "U6") (pin "13") (pinfunction "~{1Z}_13") (pintype "bidirectional"))
    )
    (net (code "38") (name "MB_C06_P") (class "Default")
      (node (ref "P5") (pin "14") (pinfunction "1_14") (pintype "passive"))
      (node (ref "P8") (pin "14") (pinfunction "1_14") (pintype "passive"))
      (node (ref "U6") (pin "14") (pinfunction "1Y_14") (pintype "bidirectional"))
      (node (ref "U6") (pin "2") (pinfunction "1A_2") (pintype "bidirectional"))
    )
    (net (code "39") (name "MB_C07_N") (class "Default")
      (node (ref "P5") (pin "16") (pinfunction "1_16") (pintype "passive"))
      (node (ref "P8") (pin "16") (pinfunction "1_16") (pintype "passive"))
      (node (ref "U6") (pin "11") (pinfunction "~{2Z}_11") (pintype "bidirectional"))
      (node (ref "U6") (pin "7") (pinfunction "~{2B}_7") (pintype "bidirectional"))
    )
    (net (code "40") (name "MB_C07_P") (class "Default")
      (node (ref "P5") (pin "15") (pinfunction "1_15") (pintype "passive"))
      (node (ref "P8") (pin "15") (pinfunction "1_15") (pintype "passive"))
      (node (ref "U6") (pin "10") (pinfunction "2Y_10") (pintype "bidirectional"))
      (node (ref "U6") (pin "6") (pinfunction "2A_6") (pintype "bidirectional"))
    )
    (net (code "41") (name "MB_C08_N") (class "Default")
      (node (ref "P5") (pin "17") (pinfunction "1_17") (pintype "passive"))
      (node (ref "P8") (pin "17") (pinfunction "1_17") (pintype "passive"))
      (node (ref "U16") (pin "1") (pinfunction "~{1B}_1") (pintype "bidirectional"))
      (node (ref "U16") (pin "13") (pinfunction "~{1Z}_13") (pintype "bidirectional"))
    )
    (net (code "42") (name "MB_C08_P") (class "Default")
      (node (ref "P5") (pin "18") (pinfunction "1_18") (pintype "passive"))
      (node (ref "P8") (pin "18") (pinfunction "1_18") (pintype "passive"))
      (node (ref "U16") (pin "14") (pinfunction "1Y_14") (pintype "bidirectional"))
      (node (ref "U16") (pin "2") (pinfunction "1A_2") (pintype "bidirectional"))
    )
    (net (code "43") (name "MB_C09_N") (class "Default")
      (node (ref "P5") (pin "20") (pinfunction "1_20") (pintype "passive"))
      (node (ref "P8") (pin "20") (pinfunction "1_20") (pintype "passive"))
      (node (ref "U16") (pin "11") (pinfunction "~{2Z}_11") (pintype "bidirectional"))
      (node (ref "U16") (pin "7") (pinfunction "~{2B}_7") (pintype "bidirectional"))
    )
    (net (code "44") (name "MB_C09_P") (class "Default")
      (node (ref "P5") (pin "19") (pinfunction "1_19") (pintype "passive"))
      (node (ref "P8") (pin "19") (pinfunction "1_19") (pintype "passive"))
      (node (ref "U16") (pin "10") (pinfunction "2Y_10") (pintype "bidirectional"))
      (node (ref "U16") (pin "6") (pinfunction "2A_6") (pintype "bidirectional"))
    )
    (net (code "45") (name "MB_C10_N") (class "Default")
      (node (ref "P5") (pin "21") (pinfunction "1_21") (pintype "passive"))
      (node (ref "P8") (pin "21") (pinfunction "1_21") (pintype "passive"))
      (node (ref "U27") (pin "1") (pinfunction "~{1B}_1") (pintype "bidirectional"))
      (node (ref "U27") (pin "13") (pinfunction "~{1Z}_13") (pintype "bidirectional"))
    )
    (net (code "46") (name "MB_C10_P") (class "Default")
      (node (ref "P5") (pin "22") (pinfunction "1_22") (pintype "passive"))
      (node (ref "P8") (pin "22") (pinfunction "1_22") (pintype "passive"))
      (node (ref "U27") (pin "14") (pinfunction "1Y_14") (pintype "bidirectional"))
      (node (ref "U27") (pin "2") (pinfunction "1A_2") (pintype "bidirectional"))
    )
    (net (code "47") (name "MB_C11_N") (class "Default")
      (node (ref "P5") (pin "24") (pinfunction "1_24") (pintype "passive"))
      (node (ref "P8") (pin "24") (pinfunction "1_24") (pintype "passive"))
      (node (ref "U27") (pin "11") (pinfunction "~{2Z}_11") (pintype "bidirectional"))
      (node (ref "U27") (pin "7") (pinfunction "~{2B}_7") (pintype "bidirectional"))
    )
    (net (code "48") (name "MB_C11_P") (class "Default")
      (node (ref "P5") (pin "23") (pinfunction "1_23") (pintype "passive"))
      (node (ref "P8") (pin "23") (pinfunction "1_23") (pintype "passive"))
      (node (ref "U27") (pin "10") (pinfunction "2Y_10") (pintype "bidirectional"))
      (node (ref "U27") (pin "6") (pinfunction "2A_6") (pintype "bidirectional"))
    )
    (net (code "49") (name "MB_C12_N") (class "Default")
      (node (ref "P6") (pin "16") (pinfunction "1_16") (pintype "passive"))
      (node (ref "P9") (pin "16") (pinfunction "1_16") (pintype "passive"))
      (node (ref "U19") (pin "1") (pinfunction "~{1B}_1") (pintype "bidirectional"))
      (node (ref "U19") (pin "13") (pinfunction "~{1Z}_13") (pintype "bidirectional"))
    )
    (net (code "50") (name "MB_C12_P") (class "Default")
      (node (ref "P6") (pin "15") (pinfunction "1_15") (pintype "passive"))
      (node (ref "P9") (pin "15") (pinfunction "1_15") (pintype "passive"))
      (node (ref "U19") (pin "14") (pinfunction "1Y_14") (pintype "bidirectional"))
      (node (ref "U19") (pin "2") (pinfunction "1A_2") (pintype "bidirectional"))
    )
    (net (code "51") (name "MB_C13_N") (class "Default")
      (node (ref "P6") (pin "17") (pinfunction "1_17") (pintype "passive"))
      (node (ref "P9") (pin "17") (pinfunction "1_17") (pintype "passive"))
      (node (ref "U19") (pin "11") (pinfunction "~{2Z}_11") (pintype "bidirectional"))
      (node (ref "U19") (pin "7") (pinfunction "~{2B}_7") (pintype "bidirectional"))
    )
    (net (code "52") (name "MB_C13_P") (class "Default")
      (node (ref "P6") (pin "18") (pinfunction "1_18") (pintype "passive"))
      (node (ref "P9") (pin "18") (pinfunction "1_18") (pintype "passive"))
      (node (ref "U19") (pin "10") (pinfunction "2Y_10") (pintype "bidirectional"))
      (node (ref "U19") (pin "6") (pinfunction "2A_6") (pintype "bidirectional"))
    )
    (net (code "53") (name "MB_C14_N") (class "Default")
      (node (ref "P6") (pin "20") (pinfunction "1_20") (pintype "passive"))
      (node (ref "P9") (pin "20") (pinfunction "1_20") (pintype "passive"))
      (node (ref "U29") (pin "1") (pinfunction "~{1B}_1") (pintype "bidirectional"))
      (node (ref "U29") (pin "13") (pinfunction "~{1Z}_13") (pintype "bidirectional"))
    )
    (net (code "54") (name "MB_C14_P") (class "Default")
      (node (ref "P6") (pin "19") (pinfunction "1_19") (pintype "passive"))
      (node (ref "P9") (pin "19") (pinfunction "1_19") (pintype "passive"))
      (node (ref "U29") (pin "14") (pinfunction "1Y_14") (pintype "bidirectional"))
      (node (ref "U29") (pin "2") (pinfunction "1A_2") (pintype "bidirectional"))
    )
    (net (code "55") (name "MB_C15_N") (class "Default")
      (node (ref "P6") (pin "21") (pinfunction "1_21") (pintype "passive"))
      (node (ref "P9") (pin "21") (pinfunction "1_21") (pintype "passive"))
      (node (ref "U29") (pin "11") (pinfunction "~{2Z}_11") (pintype "bidirectional"))
      (node (ref "U29") (pin "7") (pinfunction "~{2B}_7") (pintype "bidirectional"))
    )
    (net (code "56") (name "MB_C15_P") (class "Default")
      (node (ref "P6") (pin "22") (pinfunction "1_22") (pintype "passive"))
      (node (ref "P9") (pin "22") (pinfunction "1_22") (pintype "passive"))
      (node (ref "U29") (pin "10") (pinfunction "2Y_10") (pintype "bidirectional"))
      (node (ref "U29") (pin "6") (pinfunction "2A_6") (pintype "bidirectional"))
    )
    (net (code "57") (name "MB_CPA_N2") (class "Default")
      (node (ref "P6") (pin "24") (pinfunction "1_24") (pintype "passive"))
      (node (ref "P9") (pin "24") (pinfunction "1_24") (pintype "passive"))
      (node (ref "U10") (pin "1") (pinfunction "~{1B}_1") (pintype "bidirectional"))
      (node (ref "U10") (pin "13") (pinfunction "~{1Z}_13") (pintype "bidirectional"))
    )
    (net (code "58") (name "MB_CPA_P") (class "Default")
      (node (ref "P6") (pin "23") (pinfunction "1_23") (pintype "passive"))
      (node (ref "P9") (pin "23") (pinfunction "1_23") (pintype "passive"))
      (node (ref "U10") (pin "14") (pinfunction "1Y_14") (pintype "bidirectional"))
      (node (ref "U10") (pin "2") (pinfunction "1A_2") (pintype "bidirectional"))
    )
    (net (code "59") (name "MB_CTOD_N") (class "Default")
      (node (ref "P4") (pin "34") (pinfunction "1_34") (pintype "passive"))
      (node (ref "P7") (pin "34") (pinfunction "1_34") (pintype "passive"))
      (node (ref "U14") (pin "7") (pinfunction "~{2B}_7") (pintype "bidirectional"))
    )
    (net (code "60") (name "MB_CTOD_P") (class "Default")
      (node (ref "P4") (pin "33") (pinfunction "1_33") (pintype "passive"))
      (node (ref "P7") (pin "33") (pinfunction "1_33") (pintype "passive"))
      (node (ref "U14") (pin "6") (pinfunction "2A_6") (pintype "bidirectional"))
    )
    (net (code "61") (name "MB_D00_N") (class "Default")
      (node (ref "P4") (pin "1") (pinfunction "1_1") (pintype "passive"))
      (node (ref "P7") (pin "1") (pinfunction "1_1") (pintype "passive"))
      (node (ref "U1") (pin "1") (pinfunction "~{1B}_1") (pintype "bidirectional"))
      (node (ref "U1") (pin "13") (pinfunction "~{1Z}_13") (pintype "bidirectional"))
    )
    (net (code "62") (name "MB_D00_P") (class "Default")
      (node (ref "P4") (pin "2") (pinfunction "1_2") (pintype "passive"))
      (node (ref "P7") (pin "2") (pinfunction "1_2") (pintype "passive"))
      (node (ref "U1") (pin "14") (pinfunction "1Y_14") (pintype "bidirectional"))
      (node (ref "U1") (pin "2") (pinfunction "1A_2") (pintype "bidirectional"))
    )
    (net (code "63") (name "MB_D01_N") (class "Default")
      (node (ref "P4") (pin "4") (pinfunction "1_4") (pintype "passive"))
      (node (ref "P7") (pin "4") (pinfunction "1_4") (pintype "passive"))
      (node (ref "U1") (pin "11") (pinfunction "~{2Z}_11") (pintype "bidirectional"))
      (node (ref "U1") (pin "7") (pinfunction "~{2B}_7") (pintype "bidirectional"))
    )
    (net (code "64") (name "MB_D01_P") (class "Default")
      (node (ref "P4") (pin "3") (pinfunction "1_3") (pintype "passive"))
      (node (ref "P7") (pin "3") (pinfunction "1_3") (pintype "passive"))
      (node (ref "U1") (pin "10") (pinfunction "2Y_10") (pintype "bidirectional"))
      (node (ref "U1") (pin "6") (pinfunction "2A_6") (pintype "bidirectional"))
    )
    (net (code "65") (name "MB_D02_N") (class "Default")
      (node (ref "P4") (pin "5") (pinfunction "1_5") (pintype "passive"))
      (node (ref "P7") (pin "5") (pinfunction "1_5") (pintype "passive"))
      (node (ref "U11") (pin "1") (pinfunction "~{1B}_1") (pintype "bidirectional"))
      (node (ref "U11") (pin "13") (pinfunction "~{1Z}_13") (pintype "bidirectional"))
    )
    (net (code "66") (name "MB_D02_P") (class "Default")
      (node (ref "P4") (pin "6") (pinfunction "1_6") (pintype "passive"))
      (node (ref "P7") (pin "6") (pinfunction "1_6") (pintype "passive"))
      (node (ref "U11") (pin "14") (pinfunction "1Y_14") (pintype "bidirectional"))
      (node (ref "U11") (pin "2") (pinfunction "1A_2") (pintype "bidirectional"))
    )
    (net (code "67") (name "MB_D03_N") (class "Default")
      (node (ref "P4") (pin "8") (pinfunction "1_8") (pintype "passive"))
      (node (ref "P7") (pin "8") (pinfunction "1_8") (pintype "passive"))
      (node (ref "U11") (pin "11") (pinfunction "~{2Z}_11") (pintype "bidirectional"))
      (node (ref "U11") (pin "7") (pinfunction "~{2B}_7") (pintype "bidirectional"))
    )
    (net (code "68") (name "MB_D03_P") (class "Default")
      (node (ref "P4") (pin "7") (pinfunction "1_7") (pintype "passive"))
      (node (ref "P7") (pin "7") (pinfunction "1_7") (pintype "passive"))
      (node (ref "U11") (pin "10") (pinfunction "2Y_10") (pintype "bidirectional"))
      (node (ref "U11") (pin "6") (pinfunction "2A_6") (pintype "bidirectional"))
    )
    (net (code "69") (name "MB_D04_N") (class "Default")
      (node (ref "P4") (pin "9") (pinfunction "1_9") (pintype "passive"))
      (node (ref "P7") (pin "9") (pinfunction "1_9") (pintype "passive"))
      (node (ref "U22") (pin "1") (pinfunction "~{1B}_1") (pintype "bidirectional"))
      (node (ref "U22") (pin "13") (pinfunction "~{1Z}_13") (pintype "bidirectional"))
    )
    (net (code "70") (name "MB_D04_P") (class "Default")
      (node (ref "P4") (pin "10") (pinfunction "1_10") (pintype "passive"))
      (node (ref "P7") (pin "10") (pinfunction "1_10") (pintype "passive"))
      (node (ref "U22") (pin "14") (pinfunction "1Y_14") (pintype "bidirectional"))
      (node (ref "U22") (pin "2") (pinfunction "1A_2") (pintype "bidirectional"))
    )
    (net (code "71") (name "MB_D05_N") (class "Default")
      (node (ref "P4") (pin "12") (pinfunction "1_12") (pintype "passive"))
      (node (ref "P7") (pin "12") (pinfunction "1_12") (pintype "passive"))
      (node (ref "U22") (pin "11") (pinfunction "~{2Z}_11") (pintype "bidirectional"))
      (node (ref "U22") (pin "7") (pinfunction "~{2B}_7") (pintype "bidirectional"))
    )
    (net (code "72") (name "MB_D05_P") (class "Default")
      (node (ref "P4") (pin "11") (pinfunction "1_11") (pintype "passive"))
      (node (ref "P7") (pin "11") (pinfunction "1_11") (pintype "passive"))
      (node (ref "U22") (pin "10") (pinfunction "2Y_10") (pintype "bidirectional"))
      (node (ref "U22") (pin "6") (pinfunction "2A_6") (pintype "bidirectional"))
    )
    (net (code "73") (name "MB_D06_N") (class "Default")
      (node (ref "P5") (pin "1") (pinfunction "1_1") (pintype "passive"))
      (node (ref "P8") (pin "1") (pinfunction "1_1") (pintype "passive"))
      (node (ref "U5") (pin "1") (pinfunction "~{1B}_1") (pintype "bidirectional"))
      (node (ref "U5") (pin "13") (pinfunction "~{1Z}_13") (pintype "bidirectional"))
    )
    (net (code "74") (name "MB_D06_P") (class "Default")
      (node (ref "P5") (pin "2") (pinfunction "1_2") (pintype "passive"))
      (node (ref "P8") (pin "2") (pinfunction "1_2") (pintype "passive"))
      (node (ref "U5") (pin "14") (pinfunction "1Y_14") (pintype "bidirectional"))
      (node (ref "U5") (pin "2") (pinfunction "1A_2") (pintype "bidirectional"))
    )
    (net (code "75") (name "MB_D07_N") (class "Default")
      (node (ref "P5") (pin "4") (pinfunction "1_4") (pintype "passive"))
      (node (ref "P8") (pin "4") (pinfunction "1_4") (pintype "passive"))
      (node (ref "U5") (pin "11") (pinfunction "~{2Z}_11") (pintype "bidirectional"))
      (node (ref "U5") (pin "7") (pinfunction "~{2B}_7") (pintype "bidirectional"))
    )
    (net (code "76") (name "MB_D07_P") (class "Default")
      (node (ref "P5") (pin "3") (pinfunction "1_3") (pintype "passive"))
      (node (ref "P8") (pin "3") (pinfunction "1_3") (pintype "passive"))
      (node (ref "U5") (pin "10") (pinfunction "2Y_10") (pintype "bidirectional"))
      (node (ref "U5") (pin "6") (pinfunction "2A_6") (pintype "bidirectional"))
    )
    (net (code "77") (name "MB_D08_N") (class "Default")
      (node (ref "P5") (pin "5") (pinfunction "1_5") (pintype "passive"))
      (node (ref "P8") (pin "5") (pinfunction "1_5") (pintype "passive"))
      (node (ref "U15") (pin "1") (pinfunction "~{1B}_1") (pintype "bidirectional"))
      (node (ref "U15") (pin "13") (pinfunction "~{1Z}_13") (pintype "bidirectional"))
    )
    (net (code "78") (name "MB_D08_P") (class "Default")
      (node (ref "P5") (pin "6") (pinfunction "1_6") (pintype "passive"))
      (node (ref "P8") (pin "6") (pinfunction "1_6") (pintype "passive"))
      (node (ref "U15") (pin "14") (pinfunction "1Y_14") (pintype "bidirectional"))
      (node (ref "U15") (pin "2") (pinfunction "1A_2") (pintype "bidirectional"))
    )
    (net (code "79") (name "MB_D09_N") (class "Default")
      (node (ref "P5") (pin "8") (pinfunction "1_8") (pintype "passive"))
      (node (ref "P8") (pin "8") (pinfunction "1_8") (pintype "passive"))
      (node (ref "U15") (pin "11") (pinfunction "~{2Z}_11") (pintype "bidirectional"))
      (node (ref "U15") (pin "7") (pinfunction "~{2B}_7") (pintype "bidirectional"))
    )
    (net (code "80") (name "MB_D09_P") (class "Default")
      (node (ref "P5") (pin "7") (pinfunction "1_7") (pintype "passive"))
      (node (ref "P8") (pin "7") (pinfunction "1_7") (pintype "passive"))
      (node (ref "U15") (pin "10") (pinfunction "2Y_10") (pintype "bidirectional"))
      (node (ref "U15") (pin "6") (pinfunction "2A_6") (pintype "bidirectional"))
    )
    (net (code "81") (name "MB_D10_N") (class "Default")
      (node (ref "P5") (pin "9") (pinfunction "1_9") (pintype "passive"))
      (node (ref "P8") (pin "9") (pinfunction "1_9") (pintype "passive"))
      (node (ref "U26") (pin "1") (pinfunction "~{1B}_1") (pintype "bidirectional"))
      (node (ref "U26") (pin "13") (pinfunction "~{1Z}_13") (pintype "bidirectional"))
    )
    (net (code "82") (name "MB_D10_P") (class "Default")
      (node (ref "P5") (pin "10") (pinfunction "1_10") (pintype "passive"))
      (node (ref "P8") (pin "10") (pinfunction "1_10") (pintype "passive"))
      (node (ref "U26") (pin "14") (pinfunction "1Y_14") (pintype "bidirectional"))
      (node (ref "U26") (pin "2") (pinfunction "1A_2") (pintype "bidirectional"))
    )
    (net (code "83") (name "MB_D11_N") (class "Default")
      (node (ref "P5") (pin "12") (pinfunction "1_12") (pintype "passive"))
      (node (ref "P8") (pin "12") (pinfunction "1_12") (pintype "passive"))
      (node (ref "U26") (pin "11") (pinfunction "~{2Z}_11") (pintype "bidirectional"))
      (node (ref "U26") (pin "7") (pinfunction "~{2B}_7") (pintype "bidirectional"))
    )
    (net (code "84") (name "MB_D11_P") (class "Default")
      (node (ref "P5") (pin "11") (pinfunction "1_11") (pintype "passive"))
      (node (ref "P8") (pin "11") (pinfunction "1_11") (pintype "passive"))
      (node (ref "U26") (pin "10") (pinfunction "2Y_10") (pintype "bidirectional"))
      (node (ref "U26") (pin "6") (pinfunction "2A_6") (pintype "bidirectional"))
    )
    (net (code "85") (name "MB_D12_N") (class "Default")
      (node (ref "P6") (pin "1") (pinfunction "1_1") (pintype "passive"))
      (node (ref "P9") (pin "1") (pinfunction "1_1") (pintype "passive"))
      (node (ref "U8") (pin "1") (pinfunction "~{1B}_1") (pintype "bidirectional"))
      (node (ref "U8") (pin "13") (pinfunction "~{1Z}_13") (pintype "bidirectional"))
    )
    (net (code "86") (name "MB_D12_P") (class "Default")
      (node (ref "P6") (pin "2") (pinfunction "1_2") (pintype "passive"))
      (node (ref "P9") (pin "2") (pinfunction "1_2") (pintype "passive"))
      (node (ref "U8") (pin "14") (pinfunction "1Y_14") (pintype "bidirectional"))
      (node (ref "U8") (pin "2") (pinfunction "1A_2") (pintype "bidirectional"))
    )
    (net (code "87") (name "MB_D13_N") (class "Default")
      (node (ref "P6") (pin "4") (pinfunction "1_4") (pintype "passive"))
      (node (ref "P9") (pin "4") (pinfunction "1_4") (pintype "passive"))
      (node (ref "U8") (pin "11") (pinfunction "~{2Z}_11") (pintype "bidirectional"))
      (node (ref "U8") (pin "7") (pinfunction "~{2B}_7") (pintype "bidirectional"))
    )
    (net (code "88") (name "MB_D13_P") (class "Default")
      (node (ref "P6") (pin "3") (pinfunction "1_3") (pintype "passive"))
      (node (ref "P9") (pin "3") (pinfunction "1_3") (pintype "passive"))
      (node (ref "U8") (pin "10") (pinfunction "2Y_10") (pintype "bidirectional"))
      (node (ref "U8") (pin "6") (pinfunction "2A_6") (pintype "bidirectional"))
    )
    (net (code "89") (name "MB_D14_N") (class "Default")
      (node (ref "P6") (pin "5") (pinfunction "1_5") (pintype "passive"))
      (node (ref "P9") (pin "5") (pinfunction "1_5") (pintype "passive"))
      (node (ref "U18") (pin "1") (pinfunction "~{1B}_1") (pintype "bidirectional"))
      (node (ref "U18") (pin "13") (pinfunction "~{1Z}_13") (pintype "bidirectional"))
    )
    (net (code "90") (name "MB_D14_P") (class "Default")
      (node (ref "P6") (pin "6") (pinfunction "1_6") (pintype "passive"))
      (node (ref "P9") (pin "6") (pinfunction "1_6") (pintype "passive"))
      (node (ref "U18") (pin "14") (pinfunction "1Y_14") (pintype "bidirectional"))
      (node (ref "U18") (pin "2") (pinfunction "1A_2") (pintype "bidirectional"))
    )
    (net (code "91") (name "MB_D15_N") (class "Default")
      (node (ref "P6") (pin "8") (pinfunction "1_8") (pintype "passive"))
      (node (ref "P9") (pin "8") (pinfunction "1_8") (pintype "passive"))
      (node (ref "U18") (pin "11") (pinfunction "~{2Z}_11") (pintype "bidirectional"))
      (node (ref "U18") (pin "7") (pinfunction "~{2B}_7") (pintype "bidirectional"))
    )
    (net (code "92") (name "MB_D15_P") (class "Default")
      (node (ref "P6") (pin "7") (pinfunction "1_7") (pintype "passive"))
      (node (ref "P9") (pin "7") (pinfunction "1_7") (pintype "passive"))
      (node (ref "U18") (pin "10") (pinfunction "2Y_10") (pintype "bidirectional"))
      (node (ref "U18") (pin "6") (pinfunction "2A_6") (pintype "bidirectional"))
    )
    (net (code "93") (name "MB_D16_N") (class "Default")
      (node (ref "P6") (pin "9") (pinfunction "1_9") (pintype "passive"))
      (node (ref "P9") (pin "9") (pinfunction "1_9") (pintype "passive"))
      (node (ref "U28") (pin "1") (pinfunction "~{1B}_1") (pintype "bidirectional"))
      (node (ref "U28") (pin "13") (pinfunction "~{1Z}_13") (pintype "bidirectional"))
    )
    (net (code "94") (name "MB_D16_P") (class "Default")
      (node (ref "P6") (pin "10") (pinfunction "1_10") (pintype "passive"))
      (node (ref "P9") (pin "10") (pinfunction "1_10") (pintype "passive"))
      (node (ref "U28") (pin "14") (pinfunction "1Y_14") (pintype "bidirectional"))
      (node (ref "U28") (pin "2") (pinfunction "1A_2") (pintype "bidirectional"))
    )
    (net (code "95") (name "MB_D17_N") (class "Default")
      (node (ref "P6") (pin "12") (pinfunction "1_12") (pintype "passive"))
      (node (ref "P9") (pin "12") (pinfunction "1_12") (pintype "passive"))
      (node (ref "U28") (pin "11") (pinfunction "~{2Z}_11") (pintype "bidirectional"))
      (node (ref "U28") (pin "7") (pinfunction "~{2B}_7") (pintype "bidirectional"))
    )
    (net (code "96") (name "MB_D17_P") (class "Default")
      (node (ref "P6") (pin "11") (pinfunction "1_11") (pintype "passive"))
      (node (ref "P9") (pin "11") (pinfunction "1_11") (pintype "passive"))
      (node (ref "U28") (pin "10") (pinfunction "2Y_10") (pintype "bidirectional"))
      (node (ref "U28") (pin "6") (pinfunction "2A_6") (pintype "bidirectional"))
    )
    (net (code "97") (name "MB_DEM_N") (class "Default")
      (node (ref "P6") (pin "35") (pinfunction "1_35") (pintype "passive"))
      (node (ref "P9") (pin "35") (pinfunction "1_35") (pintype "passive"))
      (node (ref "U30") (pin "1") (pinfunction "~{1B}_1") (pintype "bidirectional"))
    )
    (net (code "98") (name "MB_DEM_P") (class "Default")
      (node (ref "P6") (pin "36") (pinfunction "1_36") (pintype "passive"))
      (node (ref "P9") (pin "36") (pinfunction "1_36") (pintype "passive"))
      (node (ref "U30") (pin "2") (pinfunction "1A_2") (pintype "bidirectional"))
    )
    (net (code "99") (name "MB_DPA_N") (class "Default")
      (node (ref "P6") (pin "13") (pinfunction "1_13") (pintype "passive"))
      (node (ref "P9") (pin "13") (pinfunction "1_13") (pintype "passive"))
      (node (ref "U9") (pin "1") (pinfunction "~{1B}_1") (pintype "bidirectional"))
      (node (ref "U9") (pin "13") (pinfunction "~{1Z}_13") (pintype "bidirectional"))
    )
    (net (code "100") (name "MB_DPA_P") (class "Default")
      (node (ref "P6") (pin "14") (pinfunction "1_14") (pintype "passive"))
      (node (ref "P9") (pin "14") (pinfunction "1_14") (pintype "passive"))
      (node (ref "U9") (pin "14") (pinfunction "1Y_14") (pintype "bidirectional"))
      (node (ref "U9") (pin "2") (pinfunction "1A_2") (pintype "bidirectional"))
    )
    (net (code "101") (name "MB_DS00_N") (class "Default")
      (node (ref "P6") (pin "28") (pinfunction "1_28") (pintype "passive"))
      (node (ref "P9") (pin "28") (pinfunction "1_28") (pintype "passive"))
      (node (ref "U4") (pin "7") (pinfunction "~{2B}_7") (pintype "bidirectional"))
    )
    (net (code "102") (name "MB_DS00_P") (class "Default")
      (node (ref "P6") (pin "27") (pinfunction "1_27") (pintype "passive"))
      (node (ref "P9") (pin "27") (pinfunction "1_27") (pintype "passive"))
      (node (ref "U4") (pin "6") (pinfunction "2A_6") (pintype "bidirectional"))
    )
    (net (code "103") (name "MB_DS01_N") (class "Default")
      (node (ref "P6") (pin "31") (pinfunction "1_31") (pintype "passive"))
      (node (ref "P9") (pin "31") (pinfunction "1_31") (pintype "passive"))
      (node (ref "U20") (pin "1") (pinfunction "~{1B}_1") (pintype "bidirectional"))
    )
    (net (code "104") (name "MB_DS01_P") (class "Default")
      (node (ref "P6") (pin "32") (pinfunction "1_32") (pintype "passive"))
      (node (ref "P9") (pin "32") (pinfunction "1_32") (pintype "passive"))
      (node (ref "U20") (pin "2") (pinfunction "1A_2") (pintype "bidirectional"))
    )
    (net (code "105") (name "MB_DS02_N") (class "Default")
      (node (ref "P6") (pin "33") (pinfunction "1_33") (pintype "passive"))
      (node (ref "P9") (pin "33") (pinfunction "1_33") (pintype "passive"))
      (node (ref "U20") (pin "7") (pinfunction "~{2B}_7") (pintype "bidirectional"))
    )
    (net (code "106") (name "MB_DS02_P") (class "Default")
      (node (ref "P6") (pin "34") (pinfunction "1_34") (pintype "passive"))
      (node (ref "P9") (pin "34") (pinfunction "1_34") (pintype "passive"))
      (node (ref "U20") (pin "6") (pinfunction "2A_6") (pintype "bidirectional"))
    )
    (net (code "107") (name "MB_EBL_N") (class "Default")
      (node (ref "P5") (pin "29") (pinfunction "1_29") (pintype "passive"))
      (node (ref "P8") (pin "29") (pinfunction "1_29") (pintype "passive"))
      (node (ref "U7") (pin "11") (pinfunction "~{2Z}_11") (pintype "bidirectional"))
    )
    (net (code "108") (name "MB_EBL_P") (class "Default")
      (node (ref "P5") (pin "30") (pinfunction "1_30") (pintype "passive"))
      (node (ref "P8") (pin "30") (pinfunction "1_30") (pintype "passive"))
      (node (ref "U7") (pin "10") (pinfunction "2Y_10") (pintype "bidirectional"))
    )
    (net (code "109") (name "MB_EXC_N") (class "Default")
      (node (ref "P5") (pin "25") (pinfunction "1_25") (pintype "passive"))
      (node (ref "P8") (pin "25") (pinfunction "1_25") (pintype "passive"))
      (node (ref "U7") (pin "13") (pinfunction "~{1Z}_13") (pintype "bidirectional"))
    )
    (net (code "110") (name "MB_EXC_P") (class "Default")
      (node (ref "P5") (pin "26") (pinfunction "1_26") (pintype "passive"))
      (node (ref "P8") (pin "26") (pinfunction "1_26") (pintype "passive"))
      (node (ref "U7") (pin "14") (pinfunction "1Y_14") (pintype "bidirectional"))
    )
    (net (code "111") (name "MB_INIT_N") (class "Default")
      (node (ref "P5") (pin "36") (pinfunction "1_36") (pintype "passive"))
      (node (ref "P8") (pin "36") (pinfunction "1_36") (pintype "passive"))
      (node (ref "U25") (pin "7") (pinfunction "~{2B}_7") (pintype "bidirectional"))
    )
    (net (code "112") (name "MB_INIT_P") (class "Default")
      (node (ref "P5") (pin "35") (pinfunction "1_35") (pintype "passive"))
      (node (ref "P8") (pin "35") (pinfunction "1_35") (pintype "passive"))
      (node (ref "U25") (pin "6") (pinfunction "2A_6") (pintype "bidirectional"))
    )
    (net (code "113") (name "MB_OCC_N") (class "Default")
      (node (ref "P6") (pin "25") (pinfunction "1_25") (pintype "passive"))
      (node (ref "P9") (pin "25") (pinfunction "1_25") (pintype "passive"))
      (node (ref "U3") (pin "11") (pinfunction "~{2Z}_11") (pintype "bidirectional"))
    )
    (net (code "114") (name "MB_OCC_P") (class "Default")
      (node (ref "P6") (pin "26") (pinfunction "1_26") (pintype "passive"))
      (node (ref "P9") (pin "26") (pinfunction "1_26") (pintype "passive"))
      (node (ref "U3") (pin "10") (pinfunction "2Y_10") (pintype "bidirectional"))
    )
    (net (code "115") (name "MB_RS00_N") (class "Default")
      (node (ref "P5") (pin "28") (pinfunction "1_28") (pintype "passive"))
      (node (ref "P8") (pin "28") (pinfunction "1_28") (pintype "passive"))
      (node (ref "U17") (pin "1") (pinfunction "~{1B}_1") (pintype "bidirectional"))
    )
    (net (code "116") (name "MB_RS00_P") (class "Default")
      (node (ref "P5") (pin "27") (pinfunction "1_27") (pintype "passive"))
      (node (ref "P8") (pin "27") (pinfunction "1_27") (pintype "passive"))
      (node (ref "U17") (pin "2") (pinfunction "1A_2") (pintype "bidirectional"))
    )
    (net (code "117") (name "MB_RS01_N") (class "Default")
      (node (ref "P5") (pin "31") (pinfunction "1_31") (pintype "passive"))
      (node (ref "P8") (pin "31") (pinfunction "1_31") (pintype "passive"))
      (node (ref "U17") (pin "7") (pinfunction "~{2B}_7") (pintype "bidirectional"))
    )
    (net (code "118") (name "MB_RS01_P") (class "Default")
      (node (ref "P5") (pin "32") (pinfunction "1_32") (pintype "passive"))
      (node (ref "P8") (pin "32") (pinfunction "1_32") (pintype "passive"))
      (node (ref "U17") (pin "6") (pinfunction "2A_6") (pintype "bidirectional"))
    )
    (net (code "119") (name "MB_RS02_N") (class "Default")
      (node (ref "P5") (pin "33") (pinfunction "1_33") (pintype "passive"))
      (node (ref "P8") (pin "33") (pinfunction "1_33") (pintype "passive"))
      (node (ref "U13") (pin "1") (pinfunction "~{1B}_1") (pintype "bidirectional"))
    )
    (net (code "120") (name "MB_RS02_P") (class "Default")
      (node (ref "P5") (pin "34") (pinfunction "1_34") (pintype "passive"))
      (node (ref "P8") (pin "34") (pinfunction "1_34") (pintype "passive"))
      (node (ref "U13") (pin "2") (pinfunction "1A_2") (pintype "bidirectional"))
    )
    (net (code "121") (name "MB_RS03_N") (class "Default")
      (node (ref "P4") (pin "28") (pinfunction "1_28") (pintype "passive"))
      (node (ref "P7") (pin "28") (pinfunction "1_28") (pintype "passive"))
      (node (ref "U13") (pin "7") (pinfunction "~{2B}_7") (pintype "bidirectional"))
    )
    (net (code "122") (name "MB_RS03_P") (class "Default")
      (node (ref "P4") (pin "27") (pinfunction "1_27") (pintype "passive"))
      (node (ref "P7") (pin "27") (pinfunction "1_27") (pintype "passive"))
      (node (ref "U13") (pin "6") (pinfunction "2A_6") (pintype "bidirectional"))
    )
    (net (code "123") (name "MB_RS04_N") (class "Default")
      (node (ref "P4") (pin "31") (pinfunction "1_31") (pintype "passive"))
      (node (ref "P7") (pin "31") (pinfunction "1_31") (pintype "passive"))
      (node (ref "U4") (pin "1") (pinfunction "~{1B}_1") (pintype "bidirectional"))
    )
    (net (code "124") (name "MB_RS04_P") (class "Default")
      (node (ref "P4") (pin "32") (pinfunction "1_32") (pintype "passive"))
      (node (ref "P7") (pin "32") (pinfunction "1_32") (pintype "passive"))
      (node (ref "U4") (pin "2") (pinfunction "1A_2") (pintype "bidirectional"))
    )
    (net (code "125") (name "MB_RUN_N") (class "Default")
      (node (ref "P4") (pin "38") (pinfunction "1_38") (pintype "passive"))
      (node (ref "P7") (pin "38") (pinfunction "1_38") (pintype "passive"))
      (node (ref "U25") (pin "1") (pinfunction "~{1B}_1") (pintype "bidirectional"))
    )
    (net (code "126") (name "MB_RUN_P") (class "Default")
      (node (ref "P4") (pin "37") (pinfunction "1_37") (pintype "passive"))
      (node (ref "P7") (pin "37") (pinfunction "1_37") (pintype "passive"))
      (node (ref "U25") (pin "2") (pinfunction "1A_2") (pintype "bidirectional"))
    )
    (net (code "127") (name "MB_SCLK_N") (class "Default")
      (node (ref "P4") (pin "25") (pinfunction "1_25") (pintype "passive"))
      (node (ref "P7") (pin "25") (pinfunction "1_25") (pintype "passive"))
      (node (ref "U3") (pin "13") (pinfunction "~{1Z}_13") (pintype "bidirectional"))
    )
    (net (code "128") (name "MB_SCLK_P") (class "Default")
      (node (ref "P4") (pin "26") (pinfunction "1_26") (pintype "passive"))
      (node (ref "P7") (pin "26") (pinfunction "1_26") (pintype "passive"))
      (node (ref "U3") (pin "14") (pinfunction "1Y_14") (pintype "bidirectional"))
    )
    (net (code "129") (name "MB_SP1_N") (class "Default")
      (node (ref "P5") (pin "37") (pinfunction "1_37") (pintype "passive"))
      (node (ref "P8") (pin "37") (pinfunction "1_37") (pintype "passive"))
      (node (ref "TP111") (pin "TP") (pinfunction "PP_TP") (pintype "input"))
    )
    (net (code "130") (name "MB_SP1_P") (class "Default")
      (node (ref "P5") (pin "38") (pinfunction "1_38") (pintype "passive"))
      (node (ref "P8") (pin "38") (pinfunction "1_38") (pintype "passive"))
      (node (ref "TP112") (pin "TP") (pinfunction "PP_TP") (pintype "input"))
    )
    (net (code "131") (name "MB_SP2_N") (class "Default")
      (node (ref "P6") (pin "37") (pinfunction "1_37") (pintype "passive"))
      (node (ref "P9") (pin "37") (pinfunction "1_37") (pintype "passive"))
      (node (ref "TP109") (pin "TP") (pinfunction "PP_TP") (pintype "input"))
    )
    (net (code "132") (name "MB_SP2_P") (class "Default")
      (node (ref "P6") (pin "38") (pinfunction "1_38") (pintype "passive"))
      (node (ref "P9") (pin "38") (pinfunction "1_38") (pintype "passive"))
      (node (ref "TP110") (pin "TP") (pinfunction "PP_TP") (pintype "input"))
    )
    (net (code "133") (name "MB_TRA_N") (class "Default")
      (node (ref "P6") (pin "30") (pinfunction "1_30") (pintype "passive"))
      (node (ref "P9") (pin "30") (pinfunction "1_30") (pintype "passive"))
      (node (ref "U24") (pin "13") (pinfunction "~{1Z}_13") (pintype "bidirectional"))
    )
    (net (code "134") (name "MB_TRA_P") (class "Default")
      (node (ref "P6") (pin "29") (pinfunction "1_29") (pintype "passive"))
      (node (ref "P9") (pin "29") (pinfunction "1_29") (pintype "passive"))
      (node (ref "U24") (pin "14") (pinfunction "1Y_14") (pintype "bidirectional"))
    )
    (net (code "135") (name "MB_WCLK_N") (class "Default")
      (node (ref "P4") (pin "35") (pinfunction "1_35") (pintype "passive"))
      (node (ref "P7") (pin "35") (pinfunction "1_35") (pintype "passive"))
      (node (ref "U14") (pin "1") (pinfunction "~{1B}_1") (pintype "bidirectional"))
    )
    (net (code "136") (name "MB_WCLK_P") (class "Default")
      (node (ref "P4") (pin "36") (pinfunction "1_36") (pintype "passive"))
      (node (ref "P7") (pin "36") (pinfunction "1_36") (pintype "passive"))
      (node (ref "U14") (pin "2") (pinfunction "1A_2") (pintype "bidirectional"))
    )
    (net (code "137") (name "Net-(LED1-PadA)") (class "Default")
      (node (ref "LED1") (pin "A") (pinfunction "A_A") (pintype "passive"))
      (node (ref "R1") (pin "1") (pinfunction "1_1") (pintype "passive"))
    )
    (net (code "138") (name "Net-(LED2-PadA)") (class "Default")
      (node (ref "LED2") (pin "A") (pinfunction "A_A") (pintype "passive"))
      (node (ref "R2") (pin "1") (pinfunction "1_1") (pintype "passive"))
    )
    (net (code "139") (name "Net-(LED3-PadA)") (class "Default")
      (node (ref "LED3") (pin "A") (pinfunction "A_A") (pintype "passive"))
      (node (ref "R3") (pin "1") (pinfunction "1_1") (pintype "passive"))
    )
    (net (code "140") (name "Net-(LED4-PadA)") (class "Default")
      (node (ref "LED4") (pin "A") (pinfunction "A_A") (pintype "passive"))
      (node (ref "R4") (pin "1") (pinfunction "1_1") (pintype "passive"))
    )
    (net (code "141") (name "Net-(P1AJ-1)") (class "Default")
      (node (ref "P1") (pin "41") (pinfunction "1_41") (pintype "passive"))
      (node (ref "TP190") (pin "TP") (pinfunction "PP_TP") (pintype "input"))
    )
    (net (code "142") (name "Net-(P1AL-1)") (class "Default")
      (node (ref "P1") (pin "43") (pinfunction "1_43") (pintype "passive"))
      (node (ref "TP189") (pin "TP") (pinfunction "PP_TP") (pintype "input"))
    )
    (net (code "143") (name "Net-(P1AN-1)") (class "Default")
      (node (ref "P1") (pin "45") (pinfunction "1_45") (pintype "passive"))
      (node (ref "TP188") (pin "TP") (pinfunction "PP_TP") (pintype "input"))
    )
    (net (code "144") (name "Net-(P1AP-1)") (class "Default")
      (node (ref "P1") (pin "47") (pinfunction "1_47") (pintype "passive"))
      (node (ref "TP187") (pin "TP") (pinfunction "PP_TP") (pintype "input"))
    )
    (net (code "145") (name "Net-(P3AA-1)") (class "Default")
      (node (ref "P3") (pin "33") (pinfunction "1_33") (pintype "passive"))
      (node (ref "TP186") (pin "TP") (pinfunction "PP_TP") (pintype "input"))
    )
    (net (code "146") (name "Net-(P3AC-1)") (class "Default")
      (node (ref "P3") (pin "35") (pinfunction "1_35") (pintype "passive"))
      (node (ref "TP185") (pin "TP") (pinfunction "PP_TP") (pintype "input"))
    )
    (net (code "147") (name "Net-(P3AE-1)") (class "Default")
      (node (ref "P3") (pin "37") (pinfunction "1_37") (pintype "passive"))
      (node (ref "TP184") (pin "TP") (pinfunction "PP_TP") (pintype "input"))
    )
    (net (code "148") (name "Net-(P3AG-1)") (class "Default")
      (node (ref "P3") (pin "39") (pinfunction "1_39") (pintype "passive"))
      (node (ref "TP183") (pin "TP") (pinfunction "PP_TP") (pintype "input"))
    )
    (net (code "149") (name "Net-(P3AJ-1)") (class "Default")
      (node (ref "P3") (pin "41") (pinfunction "1_41") (pintype "passive"))
      (node (ref "TP182") (pin "TP") (pinfunction "PP_TP") (pintype "input"))
    )
    (net (code "150") (name "Net-(P3AL-1)") (class "Default")
      (node (ref "P3") (pin "43") (pinfunction "1_43") (pintype "passive"))
      (node (ref "TP181") (pin "TP") (pinfunction "PP_TP") (pintype "input"))
    )
    (net (code "151") (name "Net-(P3AN-1)") (class "Default")
      (node (ref "P3") (pin "45") (pinfunction "1_45") (pintype "passive"))
      (node (ref "TP180") (pin "TP") (pinfunction "PP_TP") (pintype "input"))
    )
    (net (code "152") (name "Net-(P3AP-1)") (class "Default")
      (node (ref "P3") (pin "47") (pinfunction "1_47") (pintype "passive"))
      (node (ref "TP179") (pin "TP") (pinfunction "PP_TP") (pintype "input"))
    )
    (net (code "153") (name "Net-(Q2B-G)") (class "Default")
      (node (ref "Q2") (pin "3") (pinfunction "S_3") (pintype "passive"))
      (node (ref "Q2") (pin "4") (pinfunction "G_4") (pintype "passive"))
      (node (ref "TP113") (pin "TP") (pinfunction "PP_TP") (pintype "input"))
      (node (ref "TP119") (pin "TP") (pinfunction "PP_TP") (pintype "input"))
    )
    (net (code "154") (name "Net-(TP100-PP)") (class "Default")
      (node (ref "R102") (pin "9") (pinfunction "9_9") (pintype "passive"))
      (node (ref "TP100") (pin "TP") (pinfunction "PP_TP") (pintype "input"))
    )
    (net (code "155") (name "Net-(TP101-PP)") (class "Default")
      (node (ref "R103") (pin "9") (pinfunction "9_9") (pintype "passive"))
      (node (ref "TP101") (pin "TP") (pinfunction "PP_TP") (pintype "input"))
    )
    (net (code "156") (name "Net-(TP102-PP)") (class "Default")
      (node (ref "R104") (pin "9") (pinfunction "9_9") (pintype "passive"))
      (node (ref "TP102") (pin "TP") (pinfunction "PP_TP") (pintype "input"))
    )
    (net (code "157") (name "Net-(TP103-PP)") (class "Default")
      (node (ref "R105") (pin "9") (pinfunction "9_9") (pintype "passive"))
      (node (ref "TP103") (pin "TP") (pinfunction "PP_TP") (pintype "input"))
    )
    (net (code "158") (name "Net-(TP104-PP)") (class "Default")
      (node (ref "R106") (pin "9") (pinfunction "9_9") (pintype "passive"))
      (node (ref "TP104") (pin "TP") (pinfunction "PP_TP") (pintype "input"))
    )
    (net (code "159") (name "Net-(TP105-PP)") (class "Default")
      (node (ref "R107") (pin "9") (pinfunction "9_9") (pintype "passive"))
      (node (ref "TP105") (pin "TP") (pinfunction "PP_TP") (pintype "input"))
    )
    (net (code "160") (name "Net-(TP114-PP)") (class "Default")
      (node (ref "TP114") (pin "TP") (pinfunction "PP_TP") (pintype "input"))
      (node (ref "U24") (pin "7") (pinfunction "~{2B}_7") (pintype "bidirectional"))
    )
    (net (code "161") (name "Net-(TP115-PP)") (class "Default")
      (node (ref "Q2") (pin "5") (pinfunction "D_5") (pintype "passive"))
      (node (ref "Q2") (pin "6") (pinfunction "D_6") (pintype "passive"))
      (node (ref "TP115") (pin "TP") (pinfunction "PP_TP") (pintype "input"))
    )
    (net (code "162") (name "Net-(TP116-PP)") (class "Default")
      (node (ref "TP116") (pin "TP") (pinfunction "PP_TP") (pintype "input"))
      (node (ref "U30") (pin "9") (pinfunction "2D_9") (pintype "bidirectional"))
    )
    (net (code "163") (name "Net-(TP117-PP)") (class "Default")
      (node (ref "TP117") (pin "TP") (pinfunction "PP_TP") (pintype "input"))
      (node (ref "U30") (pin "7") (pinfunction "~{2B}_7") (pintype "bidirectional"))
    )
    (net (code "164") (name "Net-(TP118-PP)") (class "Default")
      (node (ref "TP118") (pin "TP") (pinfunction "PP_TP") (pintype "input"))
      (node (ref "U25") (pin "9") (pinfunction "2D_9") (pintype "bidirectional"))
    )
    (net (code "165") (name "Net-(TP120-PP)") (class "Default")
      (node (ref "TP120") (pin "TP") (pinfunction "PP_TP") (pintype "input"))
      (node (ref "U24") (pin "6") (pinfunction "2A_6") (pintype "bidirectional"))
    )
    (net (code "166") (name "Net-(TP121-PP)") (class "Default")
      (node (ref "TP121") (pin "TP") (pinfunction "PP_TP") (pintype "input"))
      (node (ref "U30") (pin "10") (pinfunction "2Y_10") (pintype "bidirectional"))
    )
    (net (code "167") (name "Net-(TP122-PP)") (class "Default")
      (node (ref "TP122") (pin "TP") (pinfunction "PP_TP") (pintype "input"))
      (node (ref "U30") (pin "6") (pinfunction "2A_6") (pintype "bidirectional"))
    )
    (net (code "168") (name "Net-(TP123-PP)") (class "Default")
      (node (ref "TP123") (pin "TP") (pinfunction "PP_TP") (pintype "input"))
      (node (ref "U25") (pin "10") (pinfunction "2Y_10") (pintype "bidirectional"))
    )
    (net (code "169") (name "Net-(TP124-PP)") (class "Default")
      (node (ref "TP124") (pin "TP") (pinfunction "PP_TP") (pintype "input"))
      (node (ref "U30") (pin "11") (pinfunction "~{2Z}_11") (pintype "bidirectional"))
    )
    (net (code "170") (name "Net-(TP125-PP)") (class "Default")
      (node (ref "TP125") (pin "TP") (pinfunction "PP_TP") (pintype "input"))
      (node (ref "U30") (pin "5") (pinfunction "2R_5") (pintype "bidirectional"))
    )
    (net (code "171") (name "Net-(TP126-PP)") (class "Default")
      (node (ref "TP126") (pin "TP") (pinfunction "PP_TP") (pintype "input"))
      (node (ref "U25") (pin "11") (pinfunction "~{2Z}_11") (pintype "bidirectional"))
    )
    (net (code "172") (name "Net-(TP127-PP)") (class "Default")
      (node (ref "TP127") (pin "TP") (pinfunction "PP_TP") (pintype "input"))
      (node (ref "U24") (pin "5") (pinfunction "2R_5") (pintype "bidirectional"))
    )
    (net (code "173") (name "Net-(TP128-PP)") (class "Default")
      (node (ref "TP128") (pin "TP") (pinfunction "PP_TP") (pintype "input"))
      (node (ref "U30") (pin "13") (pinfunction "~{1Z}_13") (pintype "bidirectional"))
    )
    (net (code "174") (name "Net-(TP129-PP)") (class "Default")
      (node (ref "TP129") (pin "TP") (pinfunction "PP_TP") (pintype "input"))
      (node (ref "U25") (pin "13") (pinfunction "~{1Z}_13") (pintype "bidirectional"))
    )
    (net (code "175") (name "Net-(TP130-PP)") (class "Default")
      (node (ref "TP130") (pin "TP") (pinfunction "PP_TP") (pintype "input"))
      (node (ref "U24") (pin "3") (pinfunction "1R_3") (pintype "bidirectional"))
    )
    (net (code "176") (name "Net-(TP131-PP)") (class "Default")
      (node (ref "TP131") (pin "TP") (pinfunction "PP_TP") (pintype "input"))
      (node (ref "U30") (pin "14") (pinfunction "1Y_14") (pintype "bidirectional"))
    )
    (net (code "177") (name "Net-(TP132-PP)") (class "Default")
      (node (ref "TP132") (pin "TP") (pinfunction "PP_TP") (pintype "input"))
      (node (ref "U25") (pin "14") (pinfunction "1Y_14") (pintype "bidirectional"))
    )
    (net (code "178") (name "Net-(TP133-PP)") (class "Default")
      (node (ref "TP133") (pin "TP") (pinfunction "PP_TP") (pintype "input"))
      (node (ref "U24") (pin "2") (pinfunction "1A_2") (pintype "bidirectional"))
    )
    (net (code "179") (name "Net-(TP134-PP)") (class "Default")
      (node (ref "TP134") (pin "TP") (pinfunction "PP_TP") (pintype "input"))
      (node (ref "U30") (pin "15") (pinfunction "1D_15") (pintype "bidirectional"))
    )
    (net (code "180") (name "Net-(TP135-PP)") (class "Default")
      (node (ref "TP135") (pin "TP") (pinfunction "PP_TP") (pintype "input"))
      (node (ref "U25") (pin "15") (pinfunction "1D_15") (pintype "bidirectional"))
    )
    (net (code "181") (name "Net-(TP136-PP)") (class "Default")
      (node (ref "TP136") (pin "TP") (pinfunction "PP_TP") (pintype "input"))
      (node (ref "U24") (pin "1") (pinfunction "~{1B}_1") (pintype "bidirectional"))
    )
    (net (code "182") (name "Net-(TP137-PP)") (class "Default")
      (node (ref "TP137") (pin "TP") (pinfunction "PP_TP") (pintype "input"))
      (node (ref "U20") (pin "9") (pinfunction "2D_9") (pintype "bidirectional"))
    )
    (net (code "183") (name "Net-(TP138-PP)") (class "Default")
      (node (ref "TP138") (pin "TP") (pinfunction "PP_TP") (pintype "input"))
      (node (ref "U17") (pin "9") (pinfunction "2D_9") (pintype "bidirectional"))
    )
    (net (code "184") (name "Net-(TP139-PP)") (class "Default")
      (node (ref "TP139") (pin "TP") (pinfunction "PP_TP") (pintype "input"))
      (node (ref "U14") (pin "9") (pinfunction "2D_9") (pintype "bidirectional"))
    )
    (net (code "185") (name "Net-(TP140-PP)") (class "Default")
      (node (ref "TP140") (pin "TP") (pinfunction "PP_TP") (pintype "input"))
      (node (ref "U13") (pin "9") (pinfunction "2D_9") (pintype "bidirectional"))
    )
    (net (code "186") (name "Net-(TP141-PP)") (class "Default")
      (node (ref "TP141") (pin "TP") (pinfunction "PP_TP") (pintype "input"))
      (node (ref "U20") (pin "10") (pinfunction "2Y_10") (pintype "bidirectional"))
    )
    (net (code "187") (name "Net-(TP142-PP)") (class "Default")
      (node (ref "TP142") (pin "TP") (pinfunction "PP_TP") (pintype "input"))
      (node (ref "U17") (pin "10") (pinfunction "2Y_10") (pintype "bidirectional"))
    )
    (net (code "188") (name "Net-(TP143-PP)") (class "Default")
      (node (ref "TP143") (pin "TP") (pinfunction "PP_TP") (pintype "input"))
      (node (ref "U14") (pin "10") (pinfunction "2Y_10") (pintype "bidirectional"))
    )
    (net (code "189") (name "Net-(TP144-PP)") (class "Default")
      (node (ref "TP144") (pin "TP") (pinfunction "PP_TP") (pintype "input"))
      (node (ref "U13") (pin "10") (pinfunction "2Y_10") (pintype "bidirectional"))
    )
    (net (code "190") (name "Net-(TP145-PP)") (class "Default")
      (node (ref "TP145") (pin "TP") (pinfunction "PP_TP") (pintype "input"))
      (node (ref "U20") (pin "11") (pinfunction "~{2Z}_11") (pintype "bidirectional"))
    )
    (net (code "191") (name "Net-(TP146-PP)") (class "Default")
      (node (ref "TP146") (pin "TP") (pinfunction "PP_TP") (pintype "input"))
      (node (ref "U17") (pin "11") (pinfunction "~{2Z}_11") (pintype "bidirectional"))
    )
    (net (code "192") (name "Net-(TP147-PP)") (class "Default")
      (node (ref "TP147") (pin "TP") (pinfunction "PP_TP") (pintype "input"))
      (node (ref "U14") (pin "11") (pinfunction "~{2Z}_11") (pintype "bidirectional"))
    )
    (net (code "193") (name "Net-(TP148-PP)") (class "Default")
      (node (ref "TP148") (pin "TP") (pinfunction "PP_TP") (pintype "input"))
      (node (ref "U13") (pin "11") (pinfunction "~{2Z}_11") (pintype "bidirectional"))
    )
    (net (code "194") (name "Net-(TP149-PP)") (class "Default")
      (node (ref "TP149") (pin "TP") (pinfunction "PP_TP") (pintype "input"))
      (node (ref "U20") (pin "13") (pinfunction "~{1Z}_13") (pintype "bidirectional"))
    )
    (net (code "195") (name "Net-(TP150-PP)") (class "Default")
      (node (ref "TP150") (pin "TP") (pinfunction "PP_TP") (pintype "input"))
      (node (ref "U17") (pin "13") (pinfunction "~{1Z}_13") (pintype "bidirectional"))
    )
    (net (code "196") (name "Net-(TP151-PP)") (class "Default")
      (node (ref "TP151") (pin "TP") (pinfunction "PP_TP") (pintype "input"))
      (node (ref "U14") (pin "13") (pinfunction "~{1Z}_13") (pintype "bidirectional"))
    )
    (net (code "197") (name "Net-(TP152-PP)") (class "Default")
      (node (ref "TP152") (pin "TP") (pinfunction "PP_TP") (pintype "input"))
      (node (ref "U13") (pin "13") (pinfunction "~{1Z}_13") (pintype "bidirectional"))
    )
    (net (code "198") (name "Net-(TP153-PP)") (class "Default")
      (node (ref "TP153") (pin "TP") (pinfunction "PP_TP") (pintype "input"))
      (node (ref "U20") (pin "14") (pinfunction "1Y_14") (pintype "bidirectional"))
    )
    (net (code "199") (name "Net-(TP154-PP)") (class "Default")
      (node (ref "TP154") (pin "TP") (pinfunction "PP_TP") (pintype "input"))
      (node (ref "U17") (pin "14") (pinfunction "1Y_14") (pintype "bidirectional"))
    )
    (net (code "200") (name "Net-(TP155-PP)") (class "Default")
      (node (ref "TP155") (pin "TP") (pinfunction "PP_TP") (pintype "input"))
      (node (ref "U14") (pin "14") (pinfunction "1Y_14") (pintype "bidirectional"))
    )
    (net (code "201") (name "Net-(TP156-PP)") (class "Default")
      (node (ref "TP156") (pin "TP") (pinfunction "PP_TP") (pintype "input"))
      (node (ref "U13") (pin "14") (pinfunction "1Y_14") (pintype "bidirectional"))
    )
    (net (code "202") (name "Net-(TP157-PP)") (class "Default")
      (node (ref "TP157") (pin "TP") (pinfunction "PP_TP") (pintype "input"))
      (node (ref "U20") (pin "15") (pinfunction "1D_15") (pintype "bidirectional"))
    )
    (net (code "203") (name "Net-(TP158-PP)") (class "Default")
      (node (ref "TP158") (pin "TP") (pinfunction "PP_TP") (pintype "input"))
      (node (ref "U17") (pin "15") (pinfunction "1D_15") (pintype "bidirectional"))
    )
    (net (code "204") (name "Net-(TP159-PP)") (class "Default")
      (node (ref "TP159") (pin "TP") (pinfunction "PP_TP") (pintype "input"))
      (node (ref "U14") (pin "15") (pinfunction "1D_15") (pintype "bidirectional"))
    )
    (net (code "205") (name "Net-(TP160-PP)") (class "Default")
      (node (ref "TP160") (pin "TP") (pinfunction "PP_TP") (pintype "input"))
      (node (ref "U13") (pin "15") (pinfunction "1D_15") (pintype "bidirectional"))
    )
    (net (code "206") (name "Net-(TP161-PP)") (class "Default")
      (node (ref "TP161") (pin "TP") (pinfunction "PP_TP") (pintype "input"))
      (node (ref "U7") (pin "7") (pinfunction "~{2B}_7") (pintype "bidirectional"))
    )
    (net (code "207") (name "Net-(TP162-PP)") (class "Default")
      (node (ref "TP162") (pin "TP") (pinfunction "PP_TP") (pintype "input"))
      (node (ref "U4") (pin "9") (pinfunction "2D_9") (pintype "bidirectional"))
    )
    (net (code "208") (name "Net-(TP163-PP)") (class "Default")
      (node (ref "TP163") (pin "TP") (pinfunction "PP_TP") (pintype "input"))
      (node (ref "U3") (pin "7") (pinfunction "~{2B}_7") (pintype "bidirectional"))
    )
    (net (code "209") (name "Net-(TP164-PP)") (class "Default")
      (node (ref "TP164") (pin "TP") (pinfunction "PP_TP") (pintype "input"))
      (node (ref "U7") (pin "6") (pinfunction "2A_6") (pintype "bidirectional"))
    )
    (net (code "210") (name "Net-(TP165-PP)") (class "Default")
      (node (ref "TP165") (pin "TP") (pinfunction "PP_TP") (pintype "input"))
      (node (ref "U4") (pin "10") (pinfunction "2Y_10") (pintype "bidirectional"))
    )
    (net (code "211") (name "Net-(TP166-PP)") (class "Default")
      (node (ref "TP166") (pin "TP") (pinfunction "PP_TP") (pintype "input"))
      (node (ref "U3") (pin "6") (pinfunction "2A_6") (pintype "bidirectional"))
    )
    (net (code "212") (name "Net-(TP167-PP)") (class "Default")
      (node (ref "TP167") (pin "TP") (pinfunction "PP_TP") (pintype "input"))
      (node (ref "U7") (pin "5") (pinfunction "2R_5") (pintype "bidirectional"))
    )
    (net (code "213") (name "Net-(TP168-PP)") (class "Default")
      (node (ref "TP168") (pin "TP") (pinfunction "PP_TP") (pintype "input"))
      (node (ref "U4") (pin "11") (pinfunction "~{2Z}_11") (pintype "bidirectional"))
    )
    (net (code "214") (name "Net-(TP169-PP)") (class "Default")
      (node (ref "TP169") (pin "TP") (pinfunction "PP_TP") (pintype "input"))
      (node (ref "U3") (pin "5") (pinfunction "2R_5") (pintype "bidirectional"))
    )
    (net (code "215") (name "Net-(TP170-PP)") (class "Default")
      (node (ref "TP170") (pin "TP") (pinfunction "PP_TP") (pintype "input"))
      (node (ref "U4") (pin "13") (pinfunction "~{1Z}_13") (pintype "bidirectional"))
    )
    (net (code "216") (name "Net-(TP171-PP)") (class "Default")
      (node (ref "TP171") (pin "TP") (pinfunction "PP_TP") (pintype "input"))
      (node (ref "U7") (pin "3") (pinfunction "1R_3") (pintype "bidirectional"))
    )
    (net (code "217") (name "Net-(TP172-PP)") (class "Default")
      (node (ref "TP172") (pin "TP") (pinfunction "PP_TP") (pintype "input"))
      (node (ref "U3") (pin "3") (pinfunction "1R_3") (pintype "bidirectional"))
    )
    (net (code "218") (name "Net-(TP173-PP)") (class "Default")
      (node (ref "TP173") (pin "TP") (pinfunction "PP_TP") (pintype "input"))
      (node (ref "U4") (pin "14") (pinfunction "1Y_14") (pintype "bidirectional"))
    )
    (net (code "219") (name "Net-(TP174-PP)") (class "Default")
      (node (ref "TP174") (pin "TP") (pinfunction "PP_TP") (pintype "input"))
      (node (ref "U7") (pin "2") (pinfunction "1A_2") (pintype "bidirectional"))
    )
    (net (code "220") (name "Net-(TP175-PP)") (class "Default")
      (node (ref "TP175") (pin "TP") (pinfunction "PP_TP") (pintype "input"))
      (node (ref "U3") (pin "2") (pinfunction "1A_2") (pintype "bidirectional"))
    )
    (net (code "221") (name "Net-(TP176-PP)") (class "Default")
      (node (ref "TP176") (pin "TP") (pinfunction "PP_TP") (pintype "input"))
      (node (ref "U4") (pin "15") (pinfunction "1D_15") (pintype "bidirectional"))
    )
    (net (code "222") (name "Net-(TP177-PP)") (class "Default")
      (node (ref "TP177") (pin "TP") (pinfunction "PP_TP") (pintype "input"))
      (node (ref "U7") (pin "1") (pinfunction "~{1B}_1") (pintype "bidirectional"))
    )
    (net (code "223") (name "Net-(TP178-PP)") (class "Default")
      (node (ref "TP178") (pin "TP") (pinfunction "PP_TP") (pintype "input"))
      (node (ref "U3") (pin "1") (pinfunction "~{1B}_1") (pintype "bidirectional"))
    )
    (net (code "224") (name "Net-(U3B-~{RE})") (class "Default")
      (node (ref "R122") (pin "2") (pinfunction "2_2") (pintype "passive"))
      (node (ref "U3") (pin "4") (pinfunction "~{RE}_4") (pintype "bidirectional"))
    )
    (net (code "225") (name "Net-(U4A-DE)") (class "Default")
      (node (ref "R119") (pin "1") (pinfunction "1_1") (pintype "passive"))
      (node (ref "U4") (pin "12") (pinfunction "DE_12") (pintype "bidirectional"))
    )
    (net (code "226") (name "Net-(U7B-~{RE})") (class "Default")
      (node (ref "R123") (pin "2") (pinfunction "2_2") (pintype "passive"))
      (node (ref "U7") (pin "4") (pinfunction "~{RE}_4") (pintype "bidirectional"))
    )
    (net (code "227") (name "Net-(U13A-DE)") (class "Default")
      (node (ref "R118") (pin "1") (pinfunction "1_1") (pintype "passive"))
      (node (ref "U13") (pin "12") (pinfunction "DE_12") (pintype "bidirectional"))
    )
    (net (code "228") (name "Net-(U14A-DE)") (class "Default")
      (node (ref "R117") (pin "1") (pinfunction "1_1") (pintype "passive"))
      (node (ref "U14") (pin "12") (pinfunction "DE_12") (pintype "bidirectional"))
    )
    (net (code "229") (name "Net-(U17A-DE)") (class "Default")
      (node (ref "R115") (pin "1") (pinfunction "1_1") (pintype "passive"))
      (node (ref "U17") (pin "12") (pinfunction "DE_12") (pintype "bidirectional"))
    )
    (net (code "230") (name "Net-(U20A-DE)") (class "Default")
      (node (ref "R116") (pin "1") (pinfunction "1_1") (pintype "passive"))
      (node (ref "U20") (pin "12") (pinfunction "DE_12") (pintype "bidirectional"))
    )
    (net (code "231") (name "Net-(U21A-A)") (class "Default")
      (node (ref "Q1") (pin "7") (pinfunction "D_7") (pintype "passive"))
      (node (ref "Q1") (pin "8") (pinfunction "D_8") (pintype "passive"))
      (node (ref "R3") (pin "2") (pinfunction "2_2") (pintype "passive"))
      (node (ref "U21") (pin "1") (pinfunction "A_1") (pintype "input"))
    )
    (net (code "232") (name "Net-(U21A-B)") (class "Default")
      (node (ref "Q1") (pin "5") (pinfunction "D_5") (pintype "passive"))
      (node (ref "Q1") (pin "6") (pinfunction "D_6") (pintype "passive"))
      (node (ref "R4") (pin "2") (pinfunction "2_2") (pintype "passive"))
      (node (ref "U21") (pin "3") (pinfunction "B_3") (pintype "input"))
    )
    (net (code "233") (name "Net-(U21A-C)") (class "Default")
      (node (ref "Q2") (pin "7") (pinfunction "D_7") (pintype "passive"))
      (node (ref "Q2") (pin "8") (pinfunction "D_8") (pintype "passive"))
      (node (ref "R2") (pin "2") (pinfunction "2_2") (pintype "passive"))
      (node (ref "U21") (pin "6") (pinfunction "C_6") (pintype "input"))
    )
    (net (code "234") (name "Net-(U24A-DE)") (class "Default")
      (node (ref "R113") (pin "1") (pinfunction "1_1") (pintype "passive"))
      (node (ref "U24") (pin "12") (pinfunction "DE_12") (pintype "bidirectional"))
    )
    (net (code "235") (name "Net-(U24B-~{RE})") (class "Default")
      (node (ref "R109") (pin "2") (pinfunction "2_2") (pintype "passive"))
      (node (ref "U24") (pin "4") (pinfunction "~{RE}_4") (pintype "bidirectional"))
    )
    (net (code "236") (name "Net-(U25A-DE)") (class "Default")
      (node (ref "R112") (pin "1") (pinfunction "1_1") (pintype "passive"))
      (node (ref "U25") (pin "12") (pinfunction "DE_12") (pintype "bidirectional"))
    )
    (net (code "237") (name "Net-(U30A-DE)") (class "Default")
      (node (ref "R114") (pin "1") (pinfunction "1_1") (pintype "passive"))
      (node (ref "U30") (pin "12") (pinfunction "DE_12") (pintype "bidirectional"))
    )
    (net (code "238") (name "RECV{slash}~{DRV_CTRL}") (class "Default")
      (node (ref "P2") (pin "3") (pinfunction "1_3") (pintype "passive"))
      (node (ref "U10") (pin "4") (pinfunction "~{RE}_4") (pintype "bidirectional"))
      (node (ref "U12") (pin "4") (pinfunction "~{RE}_4") (pintype "bidirectional"))
      (node (ref "U16") (pin "4") (pinfunction "~{RE}_4") (pintype "bidirectional"))
      (node (ref "U19") (pin "4") (pinfunction "~{RE}_4") (pintype "bidirectional"))
      (node (ref "U2") (pin "4") (pinfunction "~{RE}_4") (pintype "bidirectional"))
      (node (ref "U23") (pin "4") (pinfunction "~{RE}_4") (pintype "bidirectional"))
      (node (ref "U27") (pin "4") (pinfunction "~{RE}_4") (pintype "bidirectional"))
      (node (ref "U29") (pin "4") (pinfunction "~{RE}_4") (pintype "bidirectional"))
      (node (ref "U6") (pin "4") (pinfunction "~{RE}_4") (pintype "bidirectional"))
    )
    (net (code "239") (name "TO_MB_ATTN") (class "Default")
      (node (ref "P1") (pin "31") (pinfunction "1_31") (pintype "passive"))
      (node (ref "U24") (pin "9") (pinfunction "2D_9") (pintype "bidirectional"))
    )
    (net (code "240") (name "TO_MB_C00") (class "Default")
      (node (ref "P1") (pin "15") (pinfunction "1_15") (pintype "passive"))
      (node (ref "U2") (pin "15") (pinfunction "1D_15") (pintype "bidirectional"))
      (node (ref "U2") (pin "3") (pinfunction "1R_3") (pintype "bidirectional"))
    )
    (net (code "241") (name "TO_MB_C01") (class "Default")
      (node (ref "P1") (pin "13") (pinfunction "1_13") (pintype "passive"))
      (node (ref "U2") (pin "5") (pinfunction "2R_5") (pintype "bidirectional"))
      (node (ref "U2") (pin "9") (pinfunction "2D_9") (pintype "bidirectional"))
    )
    (net (code "242") (name "TO_MB_C02") (class "Default")
      (node (ref "P1") (pin "19") (pinfunction "1_19") (pintype "passive"))
      (node (ref "U12") (pin "15") (pinfunction "1D_15") (pintype "bidirectional"))
      (node (ref "U12") (pin "3") (pinfunction "1R_3") (pintype "bidirectional"))
    )
    (net (code "243") (name "TO_MB_C03") (class "Default")
      (node (ref "P1") (pin "17") (pinfunction "1_17") (pintype "passive"))
      (node (ref "U12") (pin "5") (pinfunction "2R_5") (pintype "bidirectional"))
      (node (ref "U12") (pin "9") (pinfunction "2D_9") (pintype "bidirectional"))
    )
    (net (code "244") (name "TO_MB_C04") (class "Default")
      (node (ref "P1") (pin "23") (pinfunction "1_23") (pintype "passive"))
      (node (ref "U23") (pin "15") (pinfunction "1D_15") (pintype "bidirectional"))
      (node (ref "U23") (pin "3") (pinfunction "1R_3") (pintype "bidirectional"))
    )
    (net (code "245") (name "TO_MB_C05") (class "Default")
      (node (ref "P1") (pin "21") (pinfunction "1_21") (pintype "passive"))
      (node (ref "U23") (pin "5") (pinfunction "2R_5") (pintype "bidirectional"))
      (node (ref "U23") (pin "9") (pinfunction "2D_9") (pintype "bidirectional"))
    )
    (net (code "246") (name "TO_MB_C06") (class "Default")
      (node (ref "P2") (pin "31") (pinfunction "1_31") (pintype "passive"))
      (node (ref "U6") (pin "15") (pinfunction "1D_15") (pintype "bidirectional"))
      (node (ref "U6") (pin "3") (pinfunction "1R_3") (pintype "bidirectional"))
    )
    (net (code "247") (name "TO_MB_C07") (class "Default")
      (node (ref "P2") (pin "29") (pinfunction "1_29") (pintype "passive"))
      (node (ref "U6") (pin "5") (pinfunction "2R_5") (pintype "bidirectional"))
      (node (ref "U6") (pin "9") (pinfunction "2D_9") (pintype "bidirectional"))
    )
    (net (code "248") (name "TO_MB_C08") (class "Default")
      (node (ref "P2") (pin "35") (pinfunction "1_35") (pintype "passive"))
      (node (ref "U16") (pin "15") (pinfunction "1D_15") (pintype "bidirectional"))
      (node (ref "U16") (pin "3") (pinfunction "1R_3") (pintype "bidirectional"))
    )
    (net (code "249") (name "TO_MB_C09") (class "Default")
      (node (ref "P2") (pin "33") (pinfunction "1_33") (pintype "passive"))
      (node (ref "U16") (pin "5") (pinfunction "2R_5") (pintype "bidirectional"))
      (node (ref "U16") (pin "9") (pinfunction "2D_9") (pintype "bidirectional"))
    )
    (net (code "250") (name "TO_MB_C10") (class "Default")
      (node (ref "P2") (pin "39") (pinfunction "1_39") (pintype "passive"))
      (node (ref "U27") (pin "15") (pinfunction "1D_15") (pintype "bidirectional"))
      (node (ref "U27") (pin "3") (pinfunction "1R_3") (pintype "bidirectional"))
    )
    (net (code "251") (name "TO_MB_C11") (class "Default")
      (node (ref "P2") (pin "37") (pinfunction "1_37") (pintype "passive"))
      (node (ref "U27") (pin "5") (pinfunction "2R_5") (pintype "bidirectional"))
      (node (ref "U27") (pin "9") (pinfunction "2D_9") (pintype "bidirectional"))
    )
    (net (code "252") (name "TO_MB_C12") (class "Default")
      (node (ref "P3") (pin "17") (pinfunction "1_17") (pintype "passive"))
      (node (ref "U19") (pin "15") (pinfunction "1D_15") (pintype "bidirectional"))
      (node (ref "U19") (pin "3") (pinfunction "1R_3") (pintype "bidirectional"))
    )
    (net (code "253") (name "TO_MB_C13") (class "Default")
      (node (ref "P3") (pin "15") (pinfunction "1_15") (pintype "passive"))
      (node (ref "U19") (pin "5") (pinfunction "2R_5") (pintype "bidirectional"))
      (node (ref "U19") (pin "9") (pinfunction "2D_9") (pintype "bidirectional"))
    )
    (net (code "254") (name "TO_MB_C14") (class "Default")
      (node (ref "P3") (pin "21") (pinfunction "1_21") (pintype "passive"))
      (node (ref "U29") (pin "15") (pinfunction "1D_15") (pintype "bidirectional"))
      (node (ref "U29") (pin "3") (pinfunction "1R_3") (pintype "bidirectional"))
    )
    (net (code "255") (name "TO_MB_C15") (class "Default")
      (node (ref "P3") (pin "19") (pinfunction "1_19") (pintype "passive"))
      (node (ref "U29") (pin "5") (pinfunction "2R_5") (pintype "bidirectional"))
      (node (ref "U29") (pin "9") (pinfunction "2D_9") (pintype "bidirectional"))
    )
    (net (code "256") (name "TO_MB_CPA") (class "Default")
      (node (ref "P3") (pin "23") (pinfunction "1_23") (pintype "passive"))
      (node (ref "U10") (pin "15") (pinfunction "1D_15") (pintype "bidirectional"))
      (node (ref "U10") (pin "3") (pinfunction "1R_3") (pintype "bidirectional"))
    )
    (net (code "257") (name "TO_MB_D00") (class "Default")
      (node (ref "P1") (pin "3") (pinfunction "1_3") (pintype "passive"))
      (node (ref "U1") (pin "15") (pinfunction "1D_15") (pintype "bidirectional"))
      (node (ref "U1") (pin "3") (pinfunction "1R_3") (pintype "bidirectional"))
    )
    (net (code "258") (name "TO_MB_D01") (class "Default")
      (node (ref "P1") (pin "1") (pinfunction "1_1") (pintype "passive"))
      (node (ref "U1") (pin "5") (pinfunction "2R_5") (pintype "bidirectional"))
      (node (ref "U1") (pin "9") (pinfunction "2D_9") (pintype "bidirectional"))
    )
    (net (code "259") (name "TO_MB_D02") (class "Default")
      (node (ref "P1") (pin "7") (pinfunction "1_7") (pintype "passive"))
      (node (ref "U11") (pin "15") (pinfunction "1D_15") (pintype "bidirectional"))
      (node (ref "U11") (pin "3") (pinfunction "1R_3") (pintype "bidirectional"))
    )
    (net (code "260") (name "TO_MB_D03") (class "Default")
      (node (ref "P1") (pin "5") (pinfunction "1_5") (pintype "passive"))
      (node (ref "U11") (pin "5") (pinfunction "2R_5") (pintype "bidirectional"))
      (node (ref "U11") (pin "9") (pinfunction "2D_9") (pintype "bidirectional"))
    )
    (net (code "261") (name "TO_MB_D04") (class "Default")
      (node (ref "P1") (pin "11") (pinfunction "1_11") (pintype "passive"))
      (node (ref "U22") (pin "15") (pinfunction "1D_15") (pintype "bidirectional"))
      (node (ref "U22") (pin "3") (pinfunction "1R_3") (pintype "bidirectional"))
    )
    (net (code "262") (name "TO_MB_D05") (class "Default")
      (node (ref "P1") (pin "9") (pinfunction "1_9") (pintype "passive"))
      (node (ref "U22") (pin "5") (pinfunction "2R_5") (pintype "bidirectional"))
      (node (ref "U22") (pin "9") (pinfunction "2D_9") (pintype "bidirectional"))
    )
    (net (code "263") (name "TO_MB_D06") (class "Default")
      (node (ref "P2") (pin "19") (pinfunction "1_19") (pintype "passive"))
      (node (ref "U5") (pin "15") (pinfunction "1D_15") (pintype "bidirectional"))
      (node (ref "U5") (pin "3") (pinfunction "1R_3") (pintype "bidirectional"))
    )
    (net (code "264") (name "TO_MB_D07") (class "Default")
      (node (ref "P2") (pin "17") (pinfunction "1_17") (pintype "passive"))
      (node (ref "U5") (pin "5") (pinfunction "2R_5") (pintype "bidirectional"))
      (node (ref "U5") (pin "9") (pinfunction "2D_9") (pintype "bidirectional"))
    )
    (net (code "265") (name "TO_MB_D08") (class "Default")
      (node (ref "P2") (pin "23") (pinfunction "1_23") (pintype "passive"))
      (node (ref "U15") (pin "15") (pinfunction "1D_15") (pintype "bidirectional"))
      (node (ref "U15") (pin "3") (pinfunction "1R_3") (pintype "bidirectional"))
    )
    (net (code "266") (name "TO_MB_D09") (class "Default")
      (node (ref "P2") (pin "21") (pinfunction "1_21") (pintype "passive"))
      (node (ref "U15") (pin "5") (pinfunction "2R_5") (pintype "bidirectional"))
      (node (ref "U15") (pin "9") (pinfunction "2D_9") (pintype "bidirectional"))
    )
    (net (code "267") (name "TO_MB_D10") (class "Default")
      (node (ref "P2") (pin "27") (pinfunction "1_27") (pintype "passive"))
      (node (ref "U26") (pin "15") (pinfunction "1D_15") (pintype "bidirectional"))
      (node (ref "U26") (pin "3") (pinfunction "1R_3") (pintype "bidirectional"))
    )
    (net (code "268") (name "TO_MB_D11") (class "Default")
      (node (ref "P2") (pin "25") (pinfunction "1_25") (pintype "passive"))
      (node (ref "U26") (pin "5") (pinfunction "2R_5") (pintype "bidirectional"))
      (node (ref "U26") (pin "9") (pinfunction "2D_9") (pintype "bidirectional"))
    )
    (net (code "269") (name "TO_MB_D12") (class "Default")
      (node (ref "P3") (pin "3") (pinfunction "1_3") (pintype "passive"))
      (node (ref "U8") (pin "15") (pinfunction "1D_15") (pintype "bidirectional"))
      (node (ref "U8") (pin "3") (pinfunction "1R_3") (pintype "bidirectional"))
    )
    (net (code "270") (name "TO_MB_D13") (class "Default")
      (node (ref "P3") (pin "1") (pinfunction "1_1") (pintype "passive"))
      (node (ref "U8") (pin "5") (pinfunction "2R_5") (pintype "bidirectional"))
      (node (ref "U8") (pin "9") (pinfunction "2D_9") (pintype "bidirectional"))
    )
    (net (code "271") (name "TO_MB_D14") (class "Default")
      (node (ref "P3") (pin "7") (pinfunction "1_7") (pintype "passive"))
      (node (ref "U18") (pin "15") (pinfunction "1D_15") (pintype "bidirectional"))
      (node (ref "U18") (pin "3") (pinfunction "1R_3") (pintype "bidirectional"))
    )
    (net (code "272") (name "TO_MB_D15") (class "Default")
      (node (ref "P3") (pin "5") (pinfunction "1_5") (pintype "passive"))
      (node (ref "U18") (pin "5") (pinfunction "2R_5") (pintype "bidirectional"))
      (node (ref "U18") (pin "9") (pinfunction "2D_9") (pintype "bidirectional"))
    )
    (net (code "273") (name "TO_MB_D16") (class "Default")
      (node (ref "P3") (pin "11") (pinfunction "1_11") (pintype "passive"))
      (node (ref "U28") (pin "15") (pinfunction "1D_15") (pintype "bidirectional"))
      (node (ref "U28") (pin "3") (pinfunction "1R_3") (pintype "bidirectional"))
    )
    (net (code "274") (name "TO_MB_D17") (class "Default")
      (node (ref "P3") (pin "9") (pinfunction "1_9") (pintype "passive"))
      (node (ref "U28") (pin "5") (pinfunction "2R_5") (pintype "bidirectional"))
      (node (ref "U28") (pin "9") (pinfunction "2D_9") (pintype "bidirectional"))
    )
    (net (code "275") (name "TO_MB_DPA") (class "Default")
      (node (ref "P3") (pin "13") (pinfunction "1_13") (pintype "passive"))
      (node (ref "U9") (pin "15") (pinfunction "1D_15") (pintype "bidirectional"))
      (node (ref "U9") (pin "3") (pinfunction "1R_3") (pintype "bidirectional"))
    )
    (net (code "276") (name "TO_MB_EBL") (class "Default")
      (node (ref "P2") (pin "41") (pinfunction "1_41") (pintype "passive"))
      (node (ref "U7") (pin "9") (pinfunction "2D_9") (pintype "bidirectional"))
    )
    (net (code "277") (name "TO_MB_EXC") (class "Default")
      (node (ref "P2") (pin "43") (pinfunction "1_43") (pintype "passive"))
      (node (ref "U7") (pin "15") (pinfunction "1D_15") (pintype "bidirectional"))
    )
    (net (code "278") (name "TO_MB_OCC") (class "Default")
      (node (ref "P1") (pin "39") (pinfunction "1_39") (pintype "passive"))
      (node (ref "U3") (pin "12") (pinfunction "DE_12") (pintype "bidirectional"))
      (node (ref "U3") (pin "9") (pinfunction "2D_9") (pintype "bidirectional"))
      (node (ref "U7") (pin "12") (pinfunction "DE_12") (pintype "bidirectional"))
    )
    (net (code "279") (name "TO_MB_SCLK") (class "Default")
      (node (ref "P1") (pin "25") (pinfunction "1_25") (pintype "passive"))
      (node (ref "U3") (pin "15") (pinfunction "1D_15") (pintype "bidirectional"))
    )
    (net (code "280") (name "TO_MB_TRA") (class "Default")
      (node (ref "P1") (pin "33") (pinfunction "1_33") (pintype "passive"))
      (node (ref "U24") (pin "15") (pinfunction "1D_15") (pintype "bidirectional"))
    )
    (net (code "281") (name "TP59") (class "Default")
      (node (ref "P10") (pin "39") (pinfunction "1_39") (pintype "passive"))
      (node (ref "TP108") (pin "TP") (pinfunction "PP_TP") (pintype "input"))
    )
    (net (code "282") (name "TP60") (class "Default")
      (node (ref "P11") (pin "39") (pinfunction "1_39") (pintype "passive"))
      (node (ref "TP107") (pin "TP") (pinfunction "PP_TP") (pintype "input"))
    )
    (net (code "283") (name "TP61") (class "Default")
      (node (ref "P12") (pin "39") (pinfunction "1_39") (pintype "passive"))
      (node (ref "TP106") (pin "TP") (pinfunction "PP_TP") (pintype "input"))
    )
    (net (code "284") (name "T_ATTN_N") (class "Default")
      (node (ref "P10") (pin "30") (pinfunction "1_30") (pintype "passive"))
      (node (ref "R105") (pin "2") (pinfunction "2_2") (pintype "passive"))
    )
    (net (code "285") (name "T_ATTN_P") (class "Default")
      (node (ref "P10") (pin "29") (pinfunction "1_29") (pintype "passive"))
      (node (ref "R105") (pin "1") (pinfunction "1_1") (pintype "passive"))
    )
    (net (code "286") (name "T_C00_N") (class "Default")
      (node (ref "P10") (pin "13") (pinfunction "1_13") (pintype "passive"))
      (node (ref "R107") (pin "7") (pinfunction "7_7") (pintype "passive"))
    )
    (net (code "287") (name "T_C00_P") (class "Default")
      (node (ref "P10") (pin "14") (pinfunction "1_14") (pintype "passive"))
      (node (ref "R107") (pin "8") (pinfunction "8_8") (pintype "passive"))
    )
    (net (code "288") (name "T_C01_N") (class "Default")
      (node (ref "P10") (pin "16") (pinfunction "1_16") (pintype "passive"))
      (node (ref "R106") (pin "2") (pinfunction "2_2") (pintype "passive"))
    )
    (net (code "289") (name "T_C01_P") (class "Default")
      (node (ref "P10") (pin "15") (pinfunction "1_15") (pintype "passive"))
      (node (ref "R106") (pin "1") (pinfunction "1_1") (pintype "passive"))
    )
    (net (code "290") (name "T_C02_N") (class "Default")
      (node (ref "P10") (pin "17") (pinfunction "1_17") (pintype "passive"))
      (node (ref "R106") (pin "15") (pinfunction "15_15") (pintype "passive"))
    )
    (net (code "291") (name "T_C02_P") (class "Default")
      (node (ref "P10") (pin "18") (pinfunction "1_18") (pintype "passive"))
      (node (ref "R106") (pin "14") (pinfunction "14_14") (pintype "passive"))
    )
    (net (code "292") (name "T_C03_N") (class "Default")
      (node (ref "P10") (pin "20") (pinfunction "1_20") (pintype "passive"))
      (node (ref "R106") (pin "4") (pinfunction "4_4") (pintype "passive"))
    )
    (net (code "293") (name "T_C03_P") (class "Default")
      (node (ref "P10") (pin "19") (pinfunction "1_19") (pintype "passive"))
      (node (ref "R106") (pin "3") (pinfunction "3_3") (pintype "passive"))
    )
    (net (code "294") (name "T_C04_N") (class "Default")
      (node (ref "P10") (pin "21") (pinfunction "1_21") (pintype "passive"))
      (node (ref "R106") (pin "13") (pinfunction "13_13") (pintype "passive"))
    )
    (net (code "295") (name "T_C04_P") (class "Default")
      (node (ref "P10") (pin "22") (pinfunction "1_22") (pintype "passive"))
      (node (ref "R106") (pin "12") (pinfunction "12_12") (pintype "passive"))
    )
    (net (code "296") (name "T_C05_N") (class "Default")
      (node (ref "P10") (pin "24") (pinfunction "1_24") (pintype "passive"))
      (node (ref "R106") (pin "6") (pinfunction "6_6") (pintype "passive"))
    )
    (net (code "297") (name "T_C05_P") (class "Default")
      (node (ref "P10") (pin "23") (pinfunction "1_23") (pintype "passive"))
      (node (ref "R106") (pin "5") (pinfunction "5_5") (pintype "passive"))
    )
    (net (code "298") (name "T_C06_N") (class "Default")
      (node (ref "P11") (pin "13") (pinfunction "1_13") (pintype "passive"))
      (node (ref "R104") (pin "5") (pinfunction "5_5") (pintype "passive"))
    )
    (net (code "299") (name "T_C06_P") (class "Default")
      (node (ref "P11") (pin "14") (pinfunction "1_14") (pintype "passive"))
      (node (ref "R104") (pin "6") (pinfunction "6_6") (pintype "passive"))
    )
    (net (code "300") (name "T_C07_N") (class "Default")
      (node (ref "P11") (pin "16") (pinfunction "1_16") (pintype "passive"))
      (node (ref "R104") (pin "11") (pinfunction "11_11") (pintype "passive"))
    )
    (net (code "301") (name "T_C07_P") (class "Default")
      (node (ref "P11") (pin "15") (pinfunction "1_15") (pintype "passive"))
      (node (ref "R104") (pin "10") (pinfunction "10_10") (pintype "passive"))
    )
    (net (code "302") (name "T_C08_N") (class "Default")
      (node (ref "P11") (pin "17") (pinfunction "1_17") (pintype "passive"))
      (node (ref "R104") (pin "7") (pinfunction "7_7") (pintype "passive"))
    )
    (net (code "303") (name "T_C08_P") (class "Default")
      (node (ref "P11") (pin "18") (pinfunction "1_18") (pintype "passive"))
      (node (ref "R104") (pin "8") (pinfunction "8_8") (pintype "passive"))
    )
    (net (code "304") (name "T_C09_N") (class "Default")
      (node (ref "P11") (pin "20") (pinfunction "1_20") (pintype "passive"))
      (node (ref "R103") (pin "2") (pinfunction "2_2") (pintype "passive"))
    )
    (net (code "305") (name "T_C09_P") (class "Default")
      (node (ref "P11") (pin "19") (pinfunction "1_19") (pintype "passive"))
      (node (ref "R103") (pin "1") (pinfunction "1_1") (pintype "passive"))
    )
    (net (code "306") (name "T_C10_N") (class "Default")
      (node (ref "P11") (pin "21") (pinfunction "1_21") (pintype "passive"))
      (node (ref "R103") (pin "15") (pinfunction "15_15") (pintype "passive"))
    )
    (net (code "307") (name "T_C10_P") (class "Default")
      (node (ref "P11") (pin "22") (pinfunction "1_22") (pintype "passive"))
      (node (ref "R103") (pin "14") (pinfunction "14_14") (pintype "passive"))
    )
    (net (code "308") (name "T_C11_N") (class "Default")
      (node (ref "P11") (pin "24") (pinfunction "1_24") (pintype "passive"))
      (node (ref "R103") (pin "4") (pinfunction "4_4") (pintype "passive"))
    )
    (net (code "309") (name "T_C11_P") (class "Default")
      (node (ref "P11") (pin "23") (pinfunction "1_23") (pintype "passive"))
      (node (ref "R103") (pin "3") (pinfunction "3_3") (pintype "passive"))
    )
    (net (code "310") (name "T_C12_N") (class "Default")
      (node (ref "P12") (pin "16") (pinfunction "1_16") (pintype "passive"))
      (node (ref "R101") (pin "13") (pinfunction "13_13") (pintype "passive"))
    )
    (net (code "311") (name "T_C12_P") (class "Default")
      (node (ref "P12") (pin "15") (pinfunction "1_15") (pintype "passive"))
      (node (ref "R101") (pin "12") (pinfunction "12_12") (pintype "passive"))
    )
    (net (code "312") (name "T_C13_N") (class "Default")
      (node (ref "P12") (pin "17") (pinfunction "1_17") (pintype "passive"))
      (node (ref "R101") (pin "6") (pinfunction "6_6") (pintype "passive"))
    )
    (net (code "313") (name "T_C13_P") (class "Default")
      (node (ref "P12") (pin "18") (pinfunction "1_18") (pintype "passive"))
      (node (ref "R101") (pin "5") (pinfunction "5_5") (pintype "passive"))
    )
    (net (code "314") (name "T_C14_N") (class "Default")
      (node (ref "P12") (pin "20") (pinfunction "1_20") (pintype "passive"))
      (node (ref "R101") (pin "11") (pinfunction "11_11") (pintype "passive"))
    )
    (net (code "315") (name "T_C14_P") (class "Default")
      (node (ref "P12") (pin "19") (pinfunction "1_19") (pintype "passive"))
      (node (ref "R101") (pin "10") (pinfunction "10_10") (pintype "passive"))
    )
    (net (code "316") (name "T_C15_N") (class "Default")
      (node (ref "P12") (pin "21") (pinfunction "1_21") (pintype "passive"))
      (node (ref "R101") (pin "8") (pinfunction "8_8") (pintype "passive"))
    )
    (net (code "317") (name "T_C15_P") (class "Default")
      (node (ref "P12") (pin "22") (pinfunction "1_22") (pintype "passive"))
      (node (ref "R101") (pin "7") (pinfunction "7_7") (pintype "passive"))
    )
    (net (code "318") (name "T_CPA_N") (class "Default")
      (node (ref "P12") (pin "24") (pinfunction "1_24") (pintype "passive"))
      (node (ref "R101") (pin "9") (pinfunction "9_9") (pintype "passive"))
    )
    (net (code "319") (name "T_CPA_P") (class "Default")
      (node (ref "P12") (pin "23") (pinfunction "1_23") (pintype "passive"))
      (node (ref "R100") (pin "1") (pinfunction "1_1") (pintype "passive"))
    )
    (net (code "320") (name "T_CTOD_N") (class "Default")
      (node (ref "P10") (pin "34") (pinfunction "1_34") (pintype "passive"))
      (node (ref "R105") (pin "4") (pinfunction "4_4") (pintype "passive"))
    )
    (net (code "321") (name "T_CTOD_P") (class "Default")
      (node (ref "P10") (pin "33") (pinfunction "1_33") (pintype "passive"))
      (node (ref "R105") (pin "3") (pinfunction "3_3") (pintype "passive"))
    )
    (net (code "322") (name "T_D00_N") (class "Default")
      (node (ref "P10") (pin "1") (pinfunction "1_1") (pintype "passive"))
      (node (ref "R107") (pin "1") (pinfunction "1_1") (pintype "passive"))
    )
    (net (code "323") (name "T_D00_P") (class "Default")
      (node (ref "P10") (pin "2") (pinfunction "1_2") (pintype "passive"))
      (node (ref "R107") (pin "2") (pinfunction "2_2") (pintype "passive"))
    )
    (net (code "324") (name "T_D01_N") (class "Default")
      (node (ref "P10") (pin "4") (pinfunction "1_4") (pintype "passive"))
      (node (ref "R107") (pin "15") (pinfunction "15_15") (pintype "passive"))
    )
    (net (code "325") (name "T_D01_P") (class "Default")
      (node (ref "P10") (pin "3") (pinfunction "1_3") (pintype "passive"))
      (node (ref "R107") (pin "14") (pinfunction "14_14") (pintype "passive"))
    )
    (net (code "326") (name "T_D02_N") (class "Default")
      (node (ref "P10") (pin "5") (pinfunction "1_5") (pintype "passive"))
      (node (ref "R107") (pin "3") (pinfunction "3_3") (pintype "passive"))
    )
    (net (code "327") (name "T_D02_P") (class "Default")
      (node (ref "P10") (pin "6") (pinfunction "1_6") (pintype "passive"))
      (node (ref "R107") (pin "4") (pinfunction "4_4") (pintype "passive"))
    )
    (net (code "328") (name "T_D03_N") (class "Default")
      (node (ref "P10") (pin "8") (pinfunction "1_8") (pintype "passive"))
      (node (ref "R107") (pin "13") (pinfunction "13_13") (pintype "passive"))
    )
    (net (code "329") (name "T_D03_P") (class "Default")
      (node (ref "P10") (pin "7") (pinfunction "1_7") (pintype "passive"))
      (node (ref "R107") (pin "12") (pinfunction "12_12") (pintype "passive"))
    )
    (net (code "330") (name "T_D04_N") (class "Default")
      (node (ref "P10") (pin "9") (pinfunction "1_9") (pintype "passive"))
      (node (ref "R107") (pin "5") (pinfunction "5_5") (pintype "passive"))
    )
    (net (code "331") (name "T_D04_P") (class "Default")
      (node (ref "P10") (pin "10") (pinfunction "1_10") (pintype "passive"))
      (node (ref "R107") (pin "6") (pinfunction "6_6") (pintype "passive"))
    )
    (net (code "332") (name "T_D05_N") (class "Default")
      (node (ref "P10") (pin "12") (pinfunction "1_12") (pintype "passive"))
      (node (ref "R107") (pin "11") (pinfunction "11_11") (pintype "passive"))
    )
    (net (code "333") (name "T_D05_P") (class "Default")
      (node (ref "P10") (pin "11") (pinfunction "1_11") (pintype "passive"))
      (node (ref "R107") (pin "10") (pinfunction "10_10") (pintype "passive"))
    )
    (net (code "334") (name "T_D06_N") (class "Default")
      (node (ref "P11") (pin "1") (pinfunction "1_1") (pintype "passive"))
      (node (ref "R105") (pin "10") (pinfunction "10_10") (pintype "passive"))
    )
    (net (code "335") (name "T_D06_P") (class "Default")
      (node (ref "P11") (pin "2") (pinfunction "1_2") (pintype "passive"))
      (node (ref "R105") (pin "11") (pinfunction "11_11") (pintype "passive"))
    )
    (net (code "336") (name "T_D07_N") (class "Default")
      (node (ref "P11") (pin "4") (pinfunction "1_4") (pintype "passive"))
      (node (ref "R105") (pin "7") (pinfunction "7_7") (pintype "passive"))
    )
    (net (code "337") (name "T_D07_P") (class "Default")
      (node (ref "P11") (pin "3") (pinfunction "1_3") (pintype "passive"))
      (node (ref "R105") (pin "8") (pinfunction "8_8") (pintype "passive"))
    )
    (net (code "338") (name "T_D08_N") (class "Default")
      (node (ref "P11") (pin "5") (pinfunction "1_5") (pintype "passive"))
      (node (ref "R104") (pin "1") (pinfunction "1_1") (pintype "passive"))
    )
    (net (code "339") (name "T_D08_P") (class "Default")
      (node (ref "P11") (pin "6") (pinfunction "1_6") (pintype "passive"))
      (node (ref "R104") (pin "2") (pinfunction "2_2") (pintype "passive"))
    )
    (net (code "340") (name "T_D09_N") (class "Default")
      (node (ref "P11") (pin "8") (pinfunction "1_8") (pintype "passive"))
      (node (ref "R104") (pin "15") (pinfunction "15_15") (pintype "passive"))
    )
    (net (code "341") (name "T_D09_P") (class "Default")
      (node (ref "P11") (pin "7") (pinfunction "1_7") (pintype "passive"))
      (node (ref "R104") (pin "14") (pinfunction "14_14") (pintype "passive"))
    )
    (net (code "342") (name "T_D10_N") (class "Default")
      (node (ref "P11") (pin "9") (pinfunction "1_9") (pintype "passive"))
      (node (ref "R104") (pin "3") (pinfunction "3_3") (pintype "passive"))
    )
    (net (code "343") (name "T_D10_P") (class "Default")
      (node (ref "P11") (pin "10") (pinfunction "1_10") (pintype "passive"))
      (node (ref "R104") (pin "4") (pinfunction "4_4") (pintype "passive"))
    )
    (net (code "344") (name "T_D11_N") (class "Default")
      (node (ref "P11") (pin "11") (pinfunction "1_11") (pintype "passive"))
      (node (ref "R104") (pin "13") (pinfunction "13_13") (pintype "passive"))
    )
    (net (code "345") (name "T_D11_P") (class "Default")
      (node (ref "P11") (pin "12") (pinfunction "1_12") (pintype "passive"))
      (node (ref "R104") (pin "12") (pinfunction "12_12") (pintype "passive"))
    )
    (net (code "346") (name "T_D12_N") (class "Default")
      (node (ref "P12") (pin "1") (pinfunction "1_1") (pintype "passive"))
      (node (ref "R102") (pin "6") (pinfunction "6_6") (pintype "passive"))
    )
    (net (code "347") (name "T_D12_P") (class "Default")
      (node (ref "P12") (pin "2") (pinfunction "1_2") (pintype "passive"))
      (node (ref "R102") (pin "5") (pinfunction "5_5") (pintype "passive"))
    )
    (net (code "348") (name "T_D13_N") (class "Default")
      (node (ref "P12") (pin "4") (pinfunction "1_4") (pintype "passive"))
      (node (ref "R102") (pin "13") (pinfunction "13_13") (pintype "passive"))
    )
    (net (code "349") (name "T_D13_P") (class "Default")
      (node (ref "P12") (pin "3") (pinfunction "1_3") (pintype "passive"))
      (node (ref "R102") (pin "12") (pinfunction "12_12") (pintype "passive"))
    )
    (net (code "350") (name "T_D14_N") (class "Default")
      (node (ref "P12") (pin "5") (pinfunction "1_5") (pintype "passive"))
      (node (ref "R102") (pin "8") (pinfunction "8_8") (pintype "passive"))
    )
    (net (code "351") (name "T_D14_P") (class "Default")
      (node (ref "P12") (pin "6") (pinfunction "1_6") (pintype "passive"))
      (node (ref "R102") (pin "7") (pinfunction "7_7") (pintype "passive"))
    )
    (net (code "352") (name "T_D15_N") (class "Default")
      (node (ref "P12") (pin "8") (pinfunction "1_8") (pintype "passive"))
      (node (ref "R102") (pin "11") (pinfunction "11_11") (pintype "passive"))
    )
    (net (code "353") (name "T_D15_P") (class "Default")
      (node (ref "P12") (pin "7") (pinfunction "1_7") (pintype "passive"))
      (node (ref "R102") (pin "10") (pinfunction "10_10") (pintype "passive"))
    )
    (net (code "354") (name "T_D16_N") (class "Default")
      (node (ref "P12") (pin "9") (pinfunction "1_9") (pintype "passive"))
      (node (ref "R101") (pin "2") (pinfunction "2_2") (pintype "passive"))
    )
    (net (code "355") (name "T_D16_P") (class "Default")
      (node (ref "P12") (pin "10") (pinfunction "1_10") (pintype "passive"))
      (node (ref "R101") (pin "1") (pinfunction "1_1") (pintype "passive"))
    )
    (net (code "356") (name "T_D17_N") (class "Default")
      (node (ref "P12") (pin "12") (pinfunction "1_12") (pintype "passive"))
      (node (ref "R101") (pin "15") (pinfunction "15_15") (pintype "passive"))
    )
    (net (code "357") (name "T_D17_P") (class "Default")
      (node (ref "P12") (pin "11") (pinfunction "1_11") (pintype "passive"))
      (node (ref "R101") (pin "14") (pinfunction "14_14") (pintype "passive"))
    )
    (net (code "358") (name "T_DEM_N") (class "Default")
      (node (ref "P12") (pin "35") (pinfunction "1_35") (pintype "passive"))
      (node (ref "R100") (pin "6") (pinfunction "6_6") (pintype "passive"))
    )
    (net (code "359") (name "T_DEM_P") (class "Default")
      (node (ref "P12") (pin "36") (pinfunction "1_36") (pintype "passive"))
      (node (ref "R100") (pin "7") (pinfunction "7_7") (pintype "passive"))
    )
    (net (code "360") (name "T_DPA_N") (class "Default")
      (node (ref "P12") (pin "13") (pinfunction "1_13") (pintype "passive"))
      (node (ref "R101") (pin "4") (pinfunction "4_4") (pintype "passive"))
    )
    (net (code "361") (name "T_DPA_P") (class "Default")
      (node (ref "P12") (pin "14") (pinfunction "1_14") (pintype "passive"))
      (node (ref "R101") (pin "3") (pinfunction "3_3") (pintype "passive"))
    )
    (net (code "362") (name "T_DS00_N") (class "Default")
      (node (ref "P12") (pin "28") (pinfunction "1_28") (pintype "passive"))
      (node (ref "R100") (pin "14") (pinfunction "14_14") (pintype "passive"))
    )
    (net (code "363") (name "T_DS00_P") (class "Default")
      (node (ref "P12") (pin "27") (pinfunction "1_27") (pintype "passive"))
      (node (ref "R100") (pin "15") (pinfunction "15_15") (pintype "passive"))
    )
    (net (code "364") (name "T_DS01_N") (class "Default")
      (node (ref "P12") (pin "31") (pinfunction "1_31") (pintype "passive"))
      (node (ref "R100") (pin "13") (pinfunction "13_13") (pintype "passive"))
    )
    (net (code "365") (name "T_DS01_P") (class "Default")
      (node (ref "P12") (pin "32") (pinfunction "1_32") (pintype "passive"))
      (node (ref "R100") (pin "12") (pinfunction "12_12") (pintype "passive"))
    )
    (net (code "366") (name "T_DS02_N") (class "Default")
      (node (ref "P12") (pin "33") (pinfunction "1_33") (pintype "passive"))
      (node (ref "R100") (pin "11") (pinfunction "11_11") (pintype "passive"))
    )
    (net (code "367") (name "T_DS02_P") (class "Default")
      (node (ref "P12") (pin "34") (pinfunction "1_34") (pintype "passive"))
      (node (ref "R100") (pin "10") (pinfunction "10_10") (pintype "passive"))
    )
    (net (code "368") (name "T_EBL_N") (class "Default")
      (node (ref "P11") (pin "29") (pinfunction "1_29") (pintype "passive"))
      (node (ref "R103") (pin "11") (pinfunction "11_11") (pintype "passive"))
    )
    (net (code "369") (name "T_EBL_P") (class "Default")
      (node (ref "P11") (pin "30") (pinfunction "1_30") (pintype "passive"))
      (node (ref "R103") (pin "10") (pinfunction "10_10") (pintype "passive"))
    )
    (net (code "370") (name "T_EXC_N") (class "Default")
      (node (ref "P11") (pin "25") (pinfunction "1_25") (pintype "passive"))
      (node (ref "R103") (pin "13") (pinfunction "13_13") (pintype "passive"))
    )
    (net (code "371") (name "T_EXC_P") (class "Default")
      (node (ref "P11") (pin "26") (pinfunction "1_26") (pintype "passive"))
      (node (ref "R103") (pin "12") (pinfunction "12_12") (pintype "passive"))
    )
    (net (code "372") (name "T_INIT_N") (class "Default")
      (node (ref "P11") (pin "36") (pinfunction "1_36") (pintype "passive"))
      (node (ref "R102") (pin "14") (pinfunction "14_14") (pintype "passive"))
    )
    (net (code "373") (name "T_INIT_P") (class "Default")
      (node (ref "P11") (pin "35") (pinfunction "1_35") (pintype "passive"))
      (node (ref "R102") (pin "15") (pinfunction "15_15") (pintype "passive"))
    )
    (net (code "374") (name "T_OCC_N") (class "Default")
      (node (ref "P12") (pin "25") (pinfunction "1_25") (pintype "passive"))
      (node (ref "R100") (pin "2") (pinfunction "2_2") (pintype "passive"))
    )
    (net (code "375") (name "T_OCC_P") (class "Default")
      (node (ref "P12") (pin "26") (pinfunction "1_26") (pintype "passive"))
      (node (ref "R100") (pin "3") (pinfunction "3_3") (pintype "passive"))
    )
    (net (code "376") (name "T_RS00_N") (class "Default")
      (node (ref "P11") (pin "28") (pinfunction "1_28") (pintype "passive"))
      (node (ref "R103") (pin "6") (pinfunction "6_6") (pintype "passive"))
    )
    (net (code "377") (name "T_RS00_P") (class "Default")
      (node (ref "P11") (pin "27") (pinfunction "1_27") (pintype "passive"))
      (node (ref "R103") (pin "5") (pinfunction "5_5") (pintype "passive"))
    )
    (net (code "378") (name "T_RS01_N") (class "Default")
      (node (ref "P11") (pin "31") (pinfunction "1_31") (pintype "passive"))
      (node (ref "R103") (pin "7") (pinfunction "7_7") (pintype "passive"))
    )
    (net (code "379") (name "T_RS01_P") (class "Default")
      (node (ref "P11") (pin "32") (pinfunction "1_32") (pintype "passive"))
      (node (ref "R103") (pin "8") (pinfunction "8_8") (pintype "passive"))
    )
    (net (code "380") (name "T_RS02_N") (class "Default")
      (node (ref "P11") (pin "33") (pinfunction "1_33") (pintype "passive"))
      (node (ref "R102") (pin "1") (pinfunction "1_1") (pintype "passive"))
    )
    (net (code "381") (name "T_RS02_P") (class "Default")
      (node (ref "P11") (pin "34") (pinfunction "1_34") (pintype "passive"))
      (node (ref "R102") (pin "2") (pinfunction "2_2") (pintype "passive"))
    )
    (net (code "382") (name "T_RS03_N") (class "Default")
      (node (ref "P10") (pin "28") (pinfunction "1_28") (pintype "passive"))
      (node (ref "R106") (pin "7") (pinfunction "7_7") (pintype "passive"))
    )
    (net (code "383") (name "T_RS03_P") (class "Default")
      (node (ref "P10") (pin "27") (pinfunction "1_27") (pintype "passive"))
      (node (ref "R106") (pin "8") (pinfunction "8_8") (pintype "passive"))
    )
    (net (code "384") (name "T_RS04_N") (class "Default")
      (node (ref "P10") (pin "31") (pinfunction "1_31") (pintype "passive"))
      (node (ref "R105") (pin "15") (pinfunction "15_15") (pintype "passive"))
    )
    (net (code "385") (name "T_RS04_P") (class "Default")
      (node (ref "P10") (pin "32") (pinfunction "1_32") (pintype "passive"))
      (node (ref "R105") (pin "14") (pinfunction "14_14") (pintype "passive"))
    )
    (net (code "386") (name "T_RUN_N") (class "Default")
      (node (ref "P10") (pin "37") (pinfunction "1_37") (pintype "passive"))
      (node (ref "R105") (pin "5") (pinfunction "5_5") (pintype "passive"))
    )
    (net (code "387") (name "T_RUN_P") (class "Default")
      (node (ref "P10") (pin "38") (pinfunction "1_38") (pintype "passive"))
      (node (ref "R105") (pin "6") (pinfunction "6_6") (pintype "passive"))
    )
    (net (code "388") (name "T_SCLK_N") (class "Default")
      (node (ref "P10") (pin "25") (pinfunction "1_25") (pintype "passive"))
      (node (ref "R106") (pin "11") (pinfunction "11_11") (pintype "passive"))
    )
    (net (code "389") (name "T_SCLK_P") (class "Default")
      (node (ref "P10") (pin "26") (pinfunction "1_26") (pintype "passive"))
      (node (ref "R106") (pin "10") (pinfunction "10_10") (pintype "passive"))
    )
    (net (code "390") (name "T_SP1_N") (class "Default")
      (node (ref "P11") (pin "37") (pinfunction "1_37") (pintype "passive"))
      (node (ref "R102") (pin "3") (pinfunction "3_3") (pintype "passive"))
    )
    (net (code "391") (name "T_SP1_P") (class "Default")
      (node (ref "P11") (pin "38") (pinfunction "1_38") (pintype "passive"))
      (node (ref "R102") (pin "4") (pinfunction "4_4") (pintype "passive"))
    )
    (net (code "392") (name "T_SP2_N") (class "Default")
      (node (ref "P12") (pin "37") (pinfunction "1_37") (pintype "passive"))
      (node (ref "R100") (pin "8") (pinfunction "8_8") (pintype "passive"))
    )
    (net (code "393") (name "T_SP2_P") (class "Default")
      (node (ref "P12") (pin "38") (pinfunction "1_38") (pintype "passive"))
      (node (ref "R100") (pin "9") (pinfunction "9_9") (pintype "passive"))
    )
    (net (code "394") (name "T_TRA_N") (class "Default")
      (node (ref "P12") (pin "30") (pinfunction "1_30") (pintype "passive"))
      (node (ref "R100") (pin "5") (pinfunction "5_5") (pintype "passive"))
    )
    (net (code "395") (name "T_TRA_P") (class "Default")
      (node (ref "P12") (pin "29") (pinfunction "1_29") (pintype "passive"))
      (node (ref "R100") (pin "4") (pinfunction "4_4") (pintype "passive"))
    )
    (net (code "396") (name "T_WCLK_N") (class "Default")
      (node (ref "P10") (pin "35") (pinfunction "1_35") (pintype "passive"))
      (node (ref "R105") (pin "13") (pinfunction "13_13") (pintype "passive"))
    )
    (net (code "397") (name "T_WCLK_P") (class "Default")
      (node (ref "P10") (pin "36") (pinfunction "1_36") (pintype "passive"))
      (node (ref "R105") (pin "12") (pinfunction "12_12") (pintype "passive"))
    )
    (net (code "398") (name "unconnected-(U9A-2D-Pad9)") (class "Default")
      (node (ref "U9") (pin "9") (pinfunction "2D_9") (pintype "bidirectional"))
    )
    (net (code "399") (name "unconnected-(U9A-2Y-Pad10)") (class "Default")
      (node (ref "U9") (pin "10") (pinfunction "2Y_10") (pintype "bidirectional"))
    )
    (net (code "400") (name "unconnected-(U9A-~{2Z}-Pad11)") (class "Default")
      (node (ref "U9") (pin "11") (pinfunction "~{2Z}_11") (pintype "bidirectional"))
    )
    (net (code "401") (name "unconnected-(U9B-2A-Pad6)") (class "Default")
      (node (ref "U9") (pin "6") (pinfunction "2A_6") (pintype "bidirectional"))
    )
    (net (code "402") (name "unconnected-(U9B-2R-Pad5)") (class "Default")
      (node (ref "U9") (pin "5") (pinfunction "2R_5") (pintype "bidirectional"))
    )
    (net (code "403") (name "unconnected-(U9B-~{2B}-Pad7)") (class "Default")
      (node (ref "U9") (pin "7") (pinfunction "~{2B}_7") (pintype "bidirectional"))
    )
    (net (code "404") (name "unconnected-(U10A-2D-Pad9)") (class "Default")
      (node (ref "U10") (pin "9") (pinfunction "2D_9") (pintype "bidirectional"))
    )
    (net (code "405") (name "unconnected-(U10A-2Y-Pad10)") (class "Default")
      (node (ref "U10") (pin "10") (pinfunction "2Y_10") (pintype "bidirectional"))
    )
    (net (code "406") (name "unconnected-(U10A-~{2Z}-Pad11)") (class "Default")
      (node (ref "U10") (pin "11") (pinfunction "~{2Z}_11") (pintype "bidirectional"))
    )
    (net (code "407") (name "unconnected-(U10B-2A-Pad6)") (class "Default")
      (node (ref "U10") (pin "6") (pinfunction "2A_6") (pintype "bidirectional"))
    )
    (net (code "408") (name "unconnected-(U10B-2R-Pad5)") (class "Default")
      (node (ref "U10") (pin "5") (pinfunction "2R_5") (pintype "bidirectional"))
    )
    (net (code "409") (name "unconnected-(U10B-~{2B}-Pad7)") (class "Default")
      (node (ref "U10") (pin "7") (pinfunction "~{2B}_7") (pintype "bidirectional"))
    )
    (net (code "410") (name "~{IF_CTRL_RCV_EN}") (class "Default")
      (node (ref "R120") (pin "2") (pinfunction "2_2") (pintype "passive"))
      (node (ref "R121") (pin "2") (pinfunction "2_2") (pintype "passive"))
      (node (ref "U13") (pin "4") (pinfunction "~{RE}_4") (pintype "bidirectional"))
      (node (ref "U14") (pin "4") (pinfunction "~{RE}_4") (pintype "bidirectional"))
      (node (ref "U17") (pin "4") (pinfunction "~{RE}_4") (pintype "bidirectional"))
      (node (ref "U20") (pin "4") (pinfunction "~{RE}_4") (pintype "bidirectional"))
      (node (ref "U25") (pin "4") (pinfunction "~{RE}_4") (pintype "bidirectional"))
      (node (ref "U30") (pin "4") (pinfunction "~{RE}_4") (pintype "bidirectional"))
      (node (ref "U4") (pin "4") (pinfunction "~{RE}_4") (pintype "bidirectional"))
    )
  )
)
